# Alt_BRD_PowerModules.net
KiCad netlist of a schematic drawn in Altium Designer
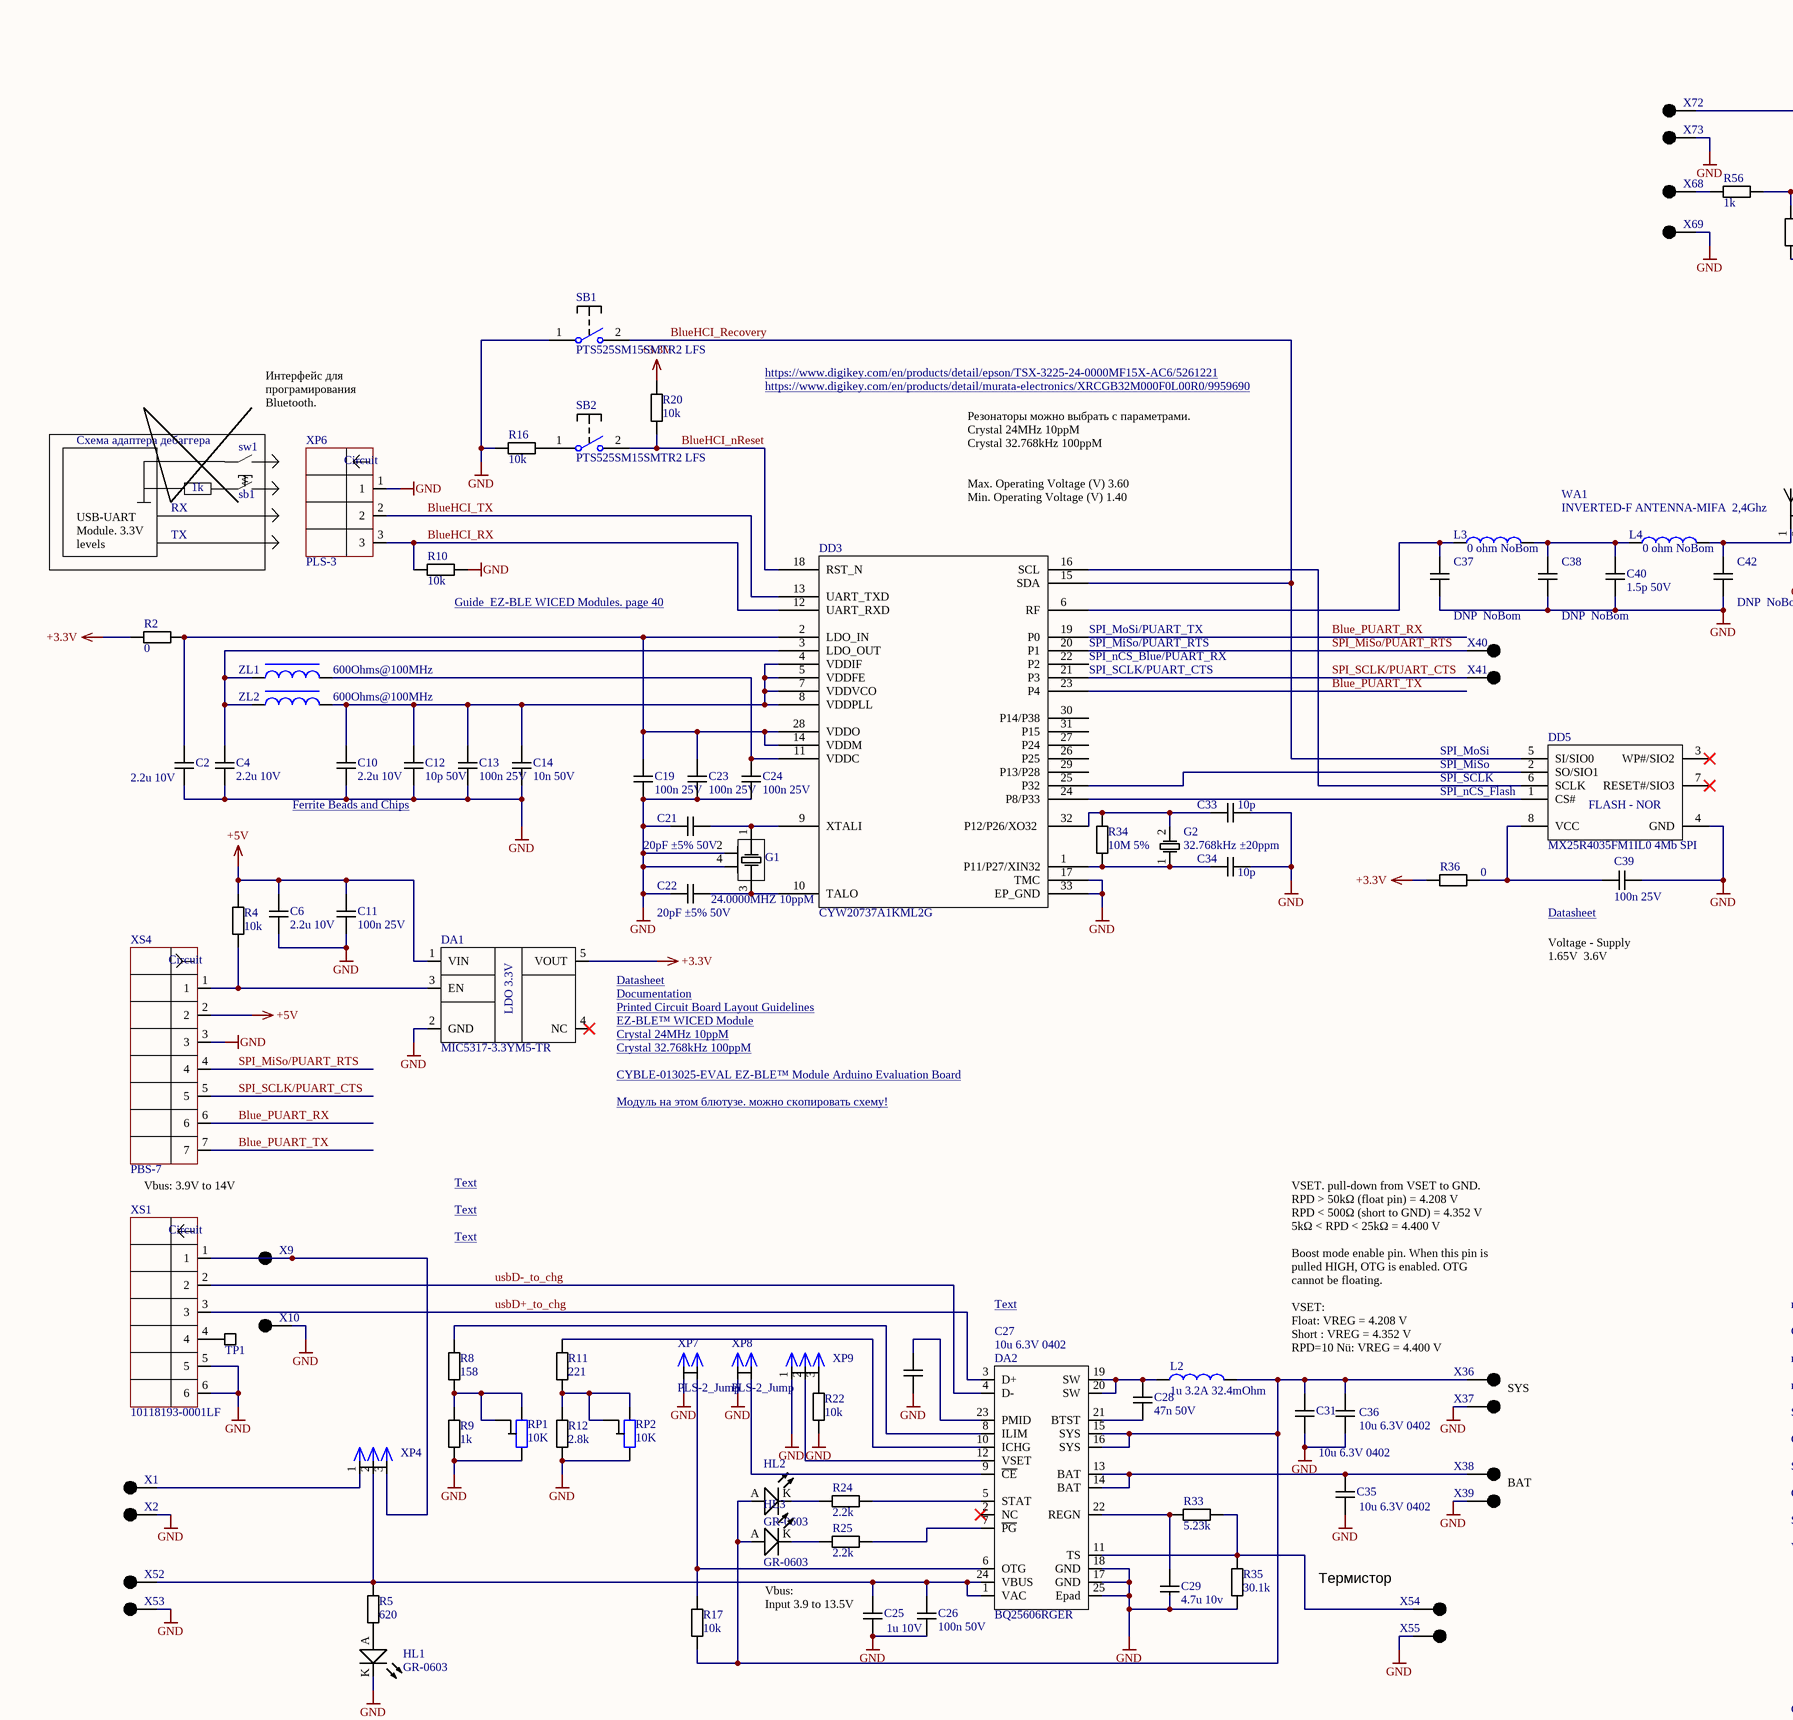
[diagram p0: Alt_BRD_PowerModules.SchDoc, top left]
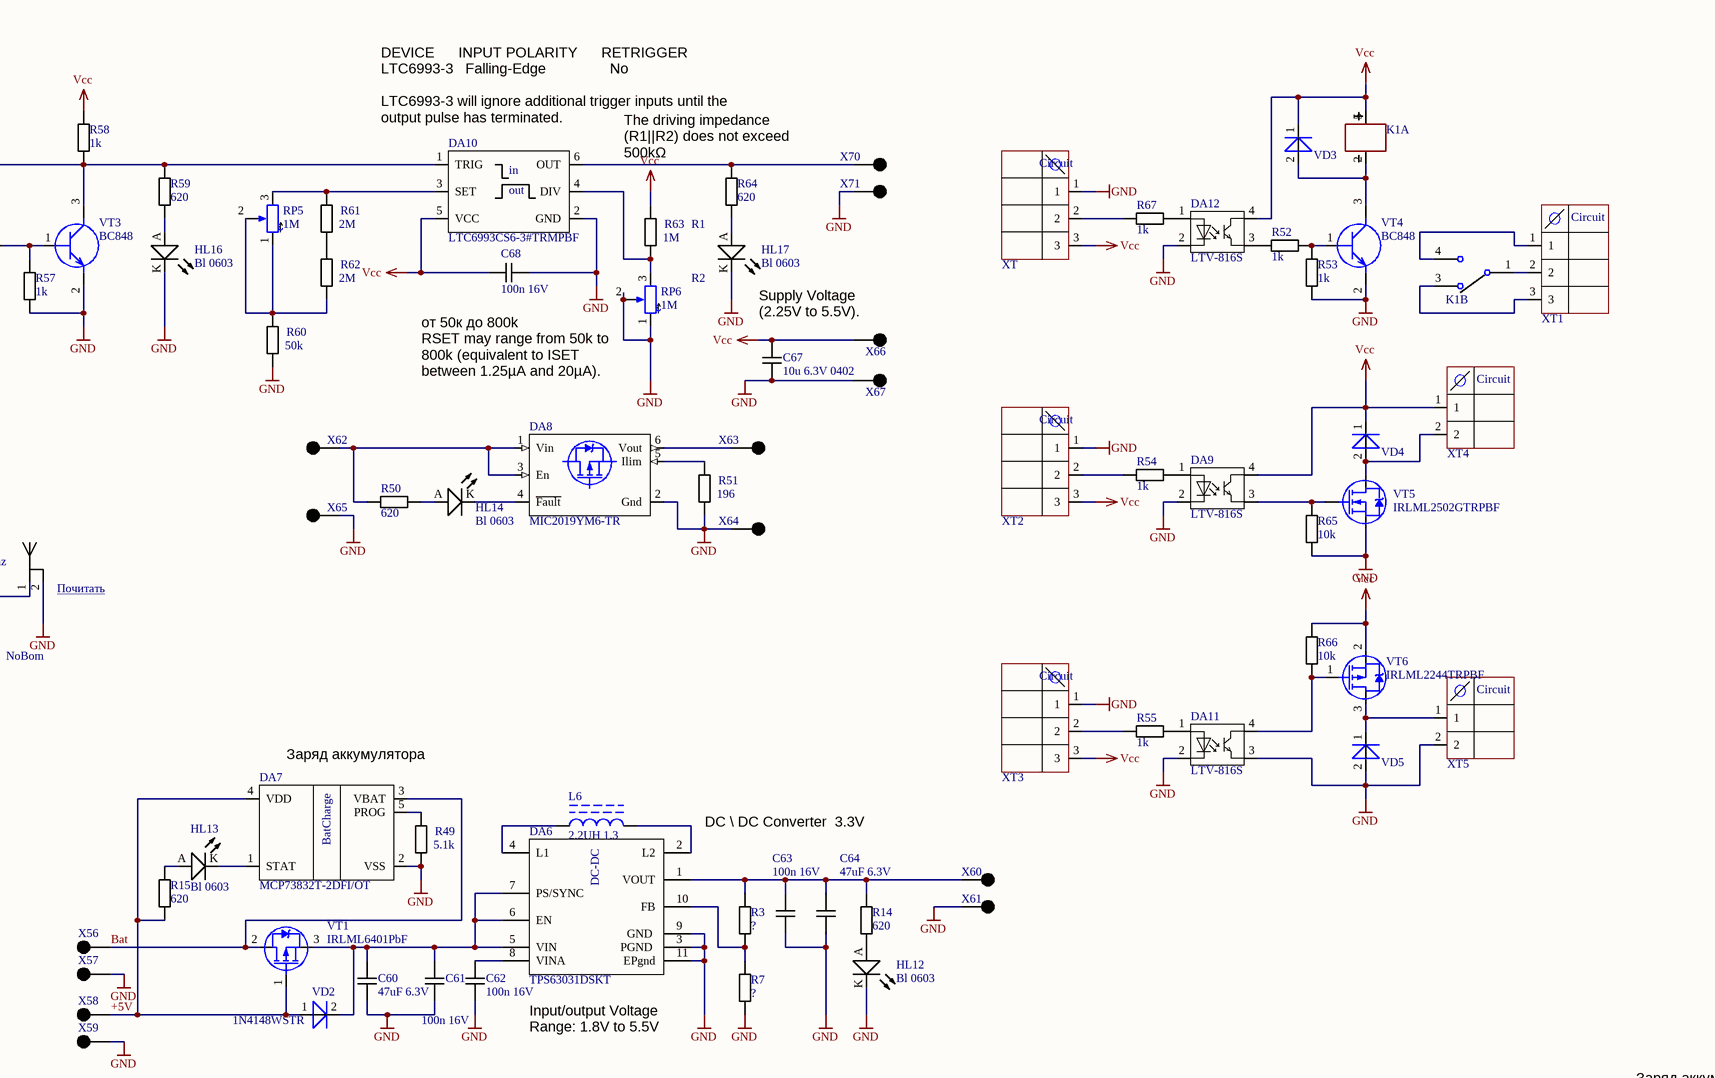
[diagram p1: Alt_BRD_PowerModules.SchDoc, top right]
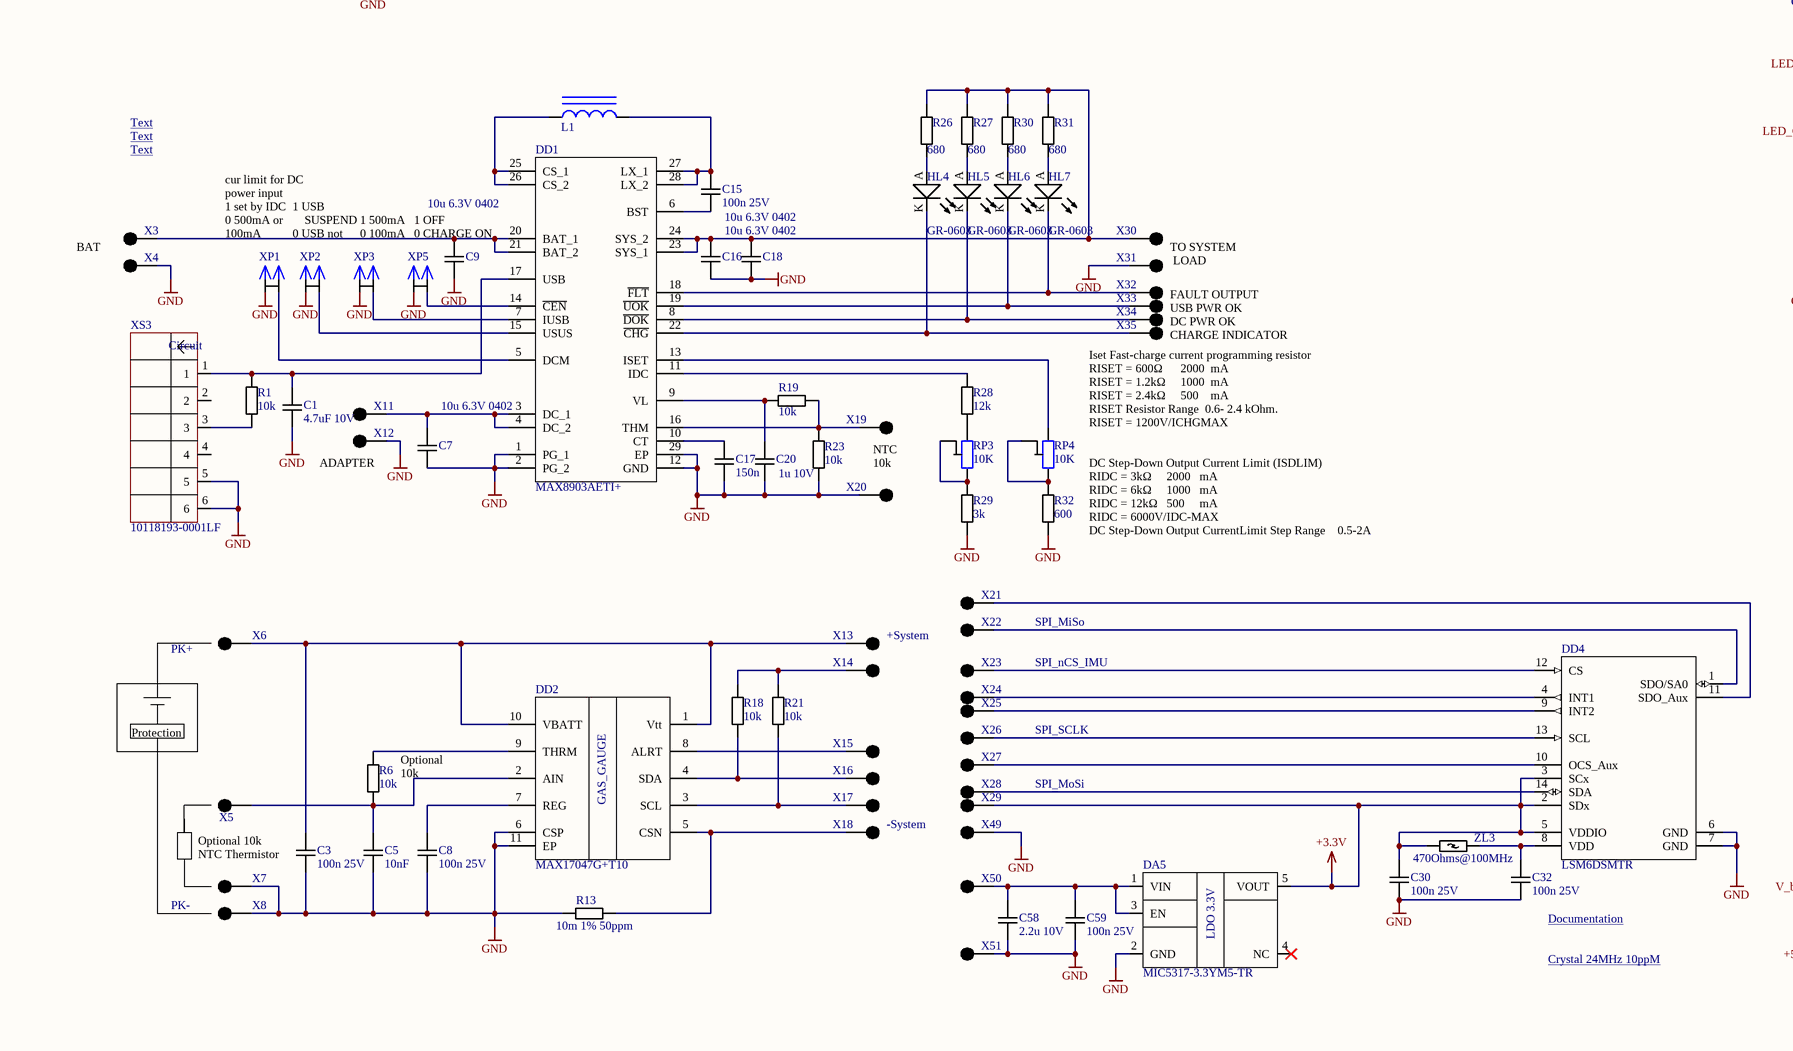
[diagram p2: Alt_BRD_PowerModules.SchDoc, bottom left]
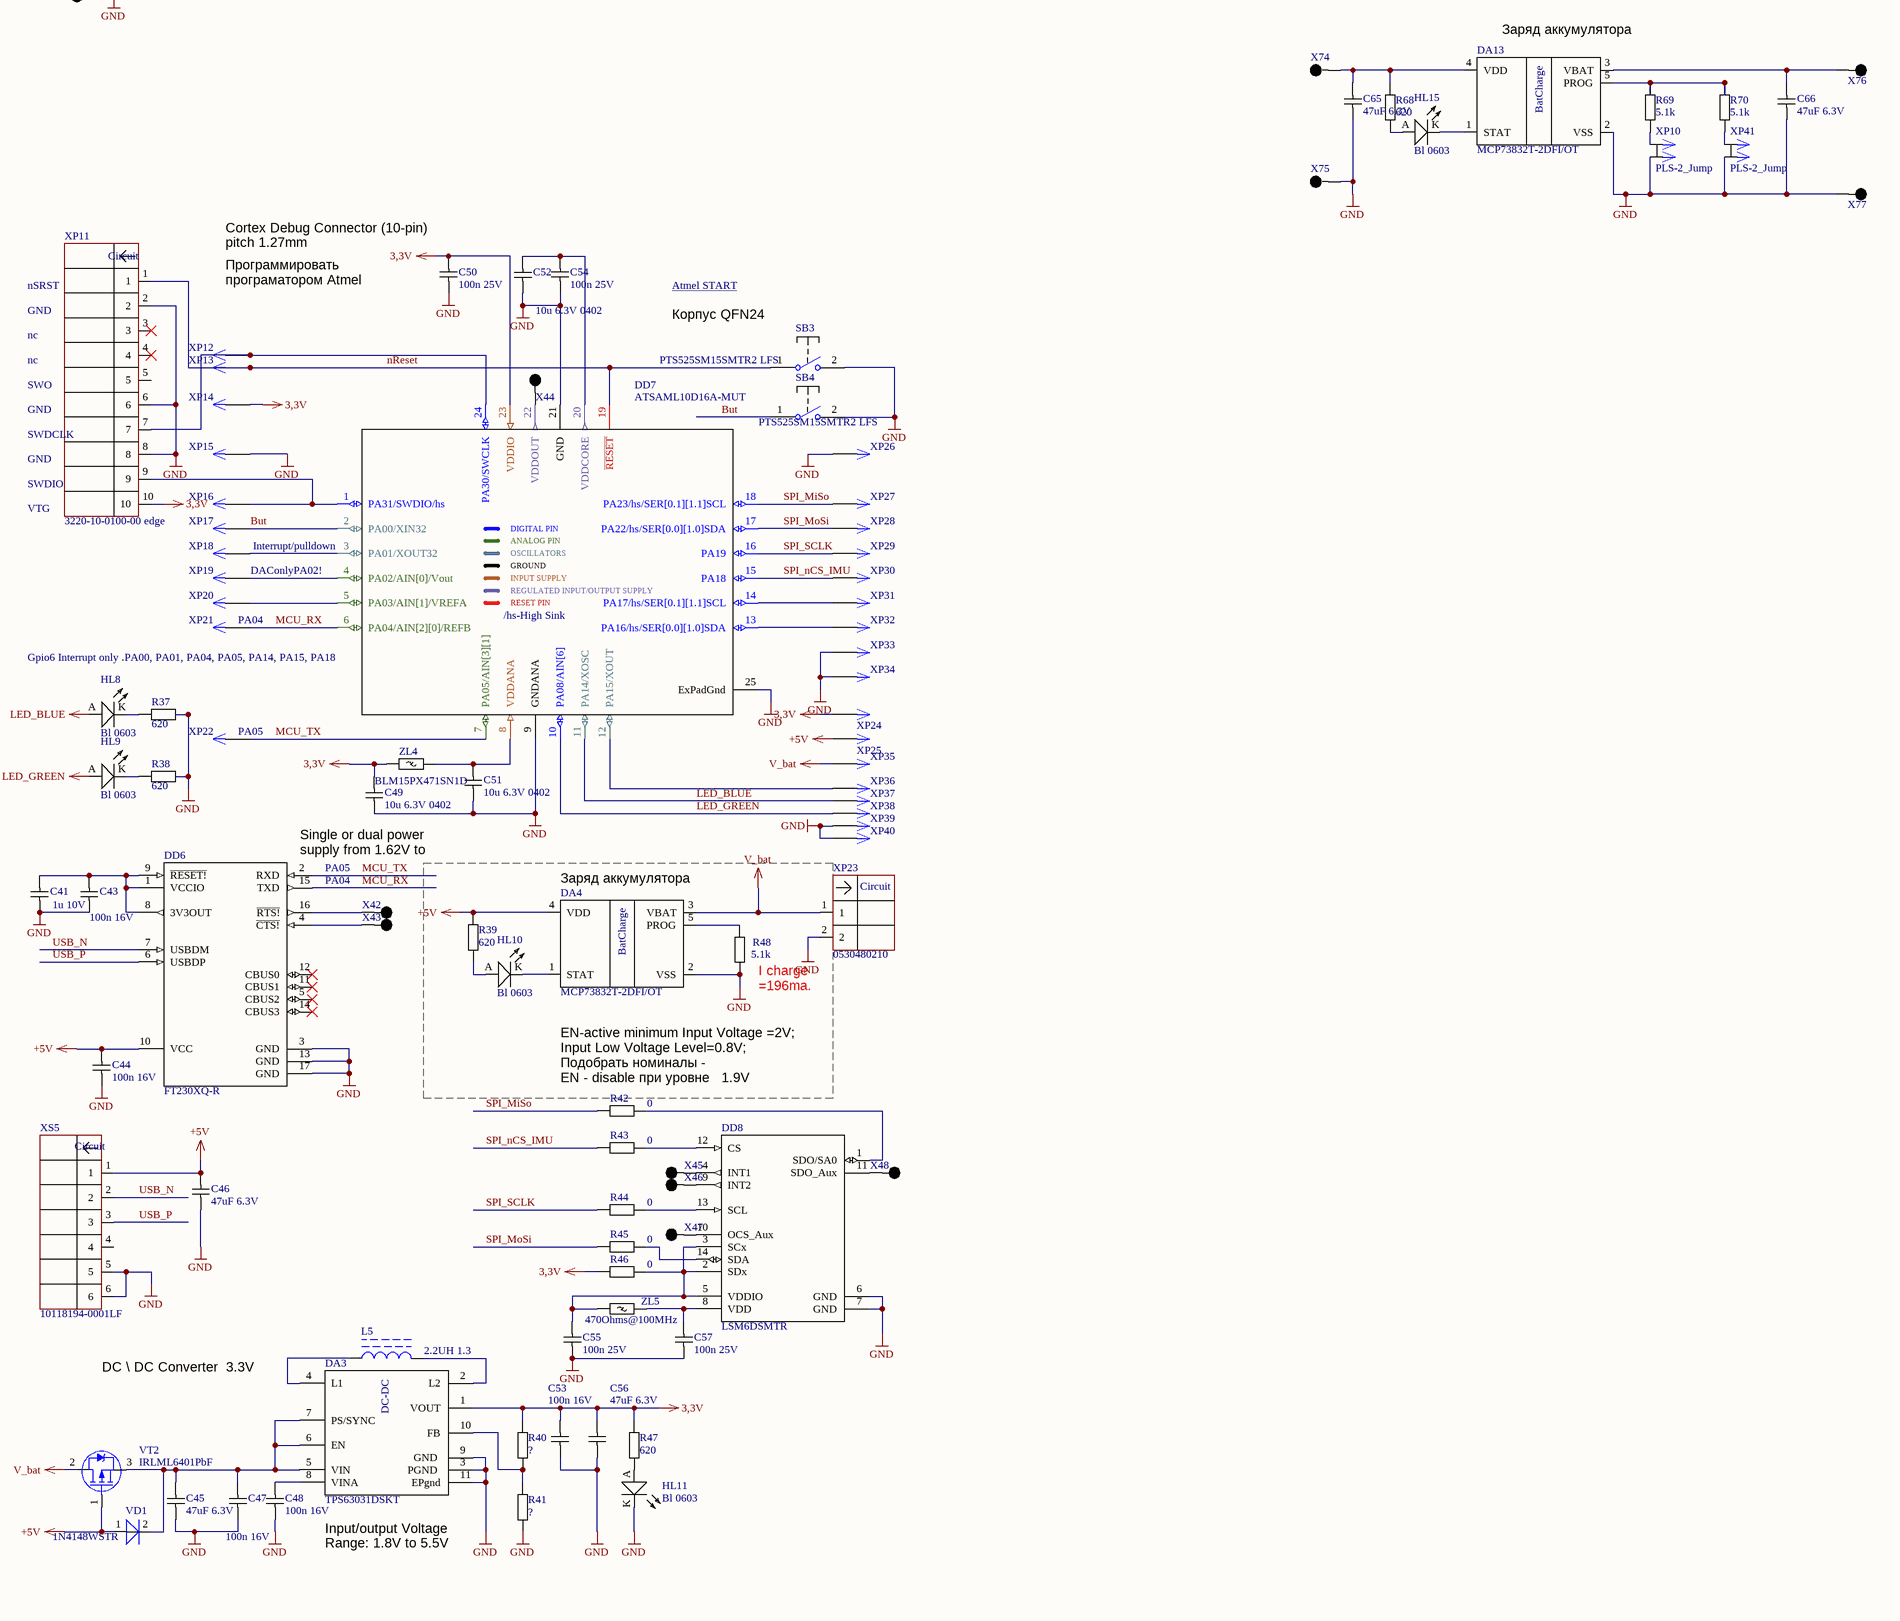
[diagram p3: Alt_BRD_PowerModules.SchDoc, bottom right]

(export (version "E")
  (design (tool "Eeschema 10.0.6"))
  (components
    (comp (ref "C1")
      (value "4.7uF 10V")
      (footprint "CapKemet1005(0402)")
      (description "CAP CER 4.7UF 10V X5R 0402")
      (fields
        (field (name "PART NUMBER") "GRM155R61A475MEAAD")
        (field (name "DIGI-KEY PART NUMBER") "490-14306-1-ND")
      )
      (libsource (lib "SssAccesDatbase") (part "Cap"))
    )
    (comp (ref "C2")
      (value "2.2u 10V")
      (footprint "CapKemet1005(0402)")
      (description "CAP CER 2.2uF 10V X5R 0402")
      (fields
        (field (name "PART NUMBER") "LMK105BJ225MV-F")
        (field (name "DIGI-KEY PART NUMBER") "587-3153-1-ND")
      )
      (libsource (lib "SssAccesDatbase") (part "Cap"))
    )
    (comp (ref "C3")
      (value "100n 25V")
      (footprint "CapKemet1005(0402)")
      (description "0.1µF ±10% 25V Ceramic Capacitor X7R 0402 (1005 Metric)")
      (fields
        (field (name "PART NUMBER") "04023C104KAT2A")
        (field (name "DIGI-KEY PART NUMBER") "478-7868-1-ND")
      )
      (libsource (lib "SssAccesDatbase") (part "Cap"))
    )
    (comp (ref "C4")
      (value "2.2u 10V")
      (footprint "CapKemet1005(0402)")
      (description "CAP CER 2.2uF 10V X5R 0402")
      (fields
        (field (name "PART NUMBER") "LMK105BJ225MV-F")
        (field (name "DIGI-KEY PART NUMBER") "587-3153-1-ND")
      )
      (libsource (lib "SssAccesDatbase") (part "Cap"))
    )
    (comp (ref "C5")
      (value "10nF")
      (footprint "CapKemet1005(0402)")
      (description "10nF 0402 50V X7R  +/-10%")
      (fields
        (field (name "PART NUMBER") "CC0402KRX7R9BB103")
        (field (name "MOUSER PART NUMBER") "603-CC402KRX7R9BB103")
      )
      (libsource (lib "SssAccesDatbase") (part "Cap"))
    )
    (comp (ref "C6")
      (value "2.2u 10V")
      (footprint "CapKemet1005(0402)")
      (description "CAP CER 2.2uF 10V X5R 0402")
      (fields
        (field (name "PART NUMBER") "LMK105BJ225MV-F")
        (field (name "DIGI-KEY PART NUMBER") "587-3153-1-ND")
      )
      (libsource (lib "SssAccesDatbase") (part "Cap"))
    )
    (comp (ref "C7")
      (value "10u 6.3V 0402")
      (footprint "CapKemet1005(0402)")
      (description "CAP CER 10UF 6.3V X5R 0402")
      (fields
        (field (name "PART NUMBER") "CAPC1005(0402)N")
        (field (name "DIGI-KEY PART NUMBER") "490-13211-1-ND")
      )
      (libsource (lib "SssAccesDatbase") (part "Cap"))
    )
    (comp (ref "C8")
      (value "100n 25V")
      (footprint "CapKemet1005(0402)")
      (description "0.1µF ±10% 25V Ceramic Capacitor X7R 0402 (1005 Metric)")
      (fields
        (field (name "PART NUMBER") "04023C104KAT2A")
        (field (name "DIGI-KEY PART NUMBER") "478-7868-1-ND")
      )
      (libsource (lib "SssAccesDatbase") (part "Cap"))
    )
    (comp (ref "C9")
      (value "10u 6.3V 0402")
      (footprint "CapKemet1005(0402)")
      (description "CAP CER 10UF 6.3V X5R 0402")
      (fields
        (field (name "PART NUMBER") "CAPC1005(0402)N")
        (field (name "DIGI-KEY PART NUMBER") "490-13211-1-ND")
      )
      (libsource (lib "SssAccesDatbase") (part "Cap"))
    )
    (comp (ref "C10")
      (value "2.2u 10V")
      (footprint "CapKemet1005(0402)")
      (description "CAP CER 2.2uF 10V X5R 0402")
      (fields
        (field (name "PART NUMBER") "LMK105BJ225MV-F")
        (field (name "DIGI-KEY PART NUMBER") "587-3153-1-ND")
      )
      (libsource (lib "SssAccesDatbase") (part "Cap"))
    )
    (comp (ref "C11")
      (value "100n 25V")
      (footprint "CapKemet1005(0402)")
      (description "CAP CER 0.1UF 25V X7R 0402")
      (fields
        (field (name "PART NUMBER") "CL05B104KA5NNNC")
        (field (name "DIGI-KEY PART NUMBER") "1276-6720-1-ND")
      )
      (libsource (lib "SssAccesDatbase") (part "Cap"))
    )
    (comp (ref "C12")
      (value "10p 50V")
      (footprint "CapKemet1005(0402)")
      (description "CAP CER 10PF 50V C0G/NP0 0402")
      (fields
        (field (name "PART NUMBER") "CL05C100DB5NNNC")
        (field (name "DIGI-KEY PART NUMBER") "1276-1625-1-ND")
      )
      (libsource (lib "SssAccesDatbase") (part "Cap"))
    )
    (comp (ref "C13")
      (value "100n 25V")
      (footprint "CapKemet1005(0402)")
      (description "CAP CER 0.1UF 25V X7R 0402")
      (fields
        (field (name "PART NUMBER") "CL05B104KA5NNNC")
        (field (name "DIGI-KEY PART NUMBER") "1276-6720-1-ND")
      )
      (libsource (lib "SssAccesDatbase") (part "Cap"))
    )
    (comp (ref "C14")
      (value "10n 50V")
      (footprint "CapKemet1005(0402)")
      (description "CAP CER 10000PF 50V X7R 0402")
      (fields
        (field (name "PART NUMBER") "CL05B103KB5NNNC")
        (field (name "DIGI-KEY PART NUMBER") "1276-1028-1-ND")
      )
      (libsource (lib "SssAccesDatbase") (part "Cap"))
    )
    (comp (ref "C15")
      (value "100n 25V")
      (footprint "CapKemet1005(0402)")
      (description "0.1µF ±10% 25V Ceramic Capacitor X7R 0402 (1005 Metric)")
      (fields
        (field (name "PART NUMBER") "04023C104KAT2A")
        (field (name "DIGI-KEY PART NUMBER") "478-7868-1-ND")
      )
      (libsource (lib "SssAccesDatbase") (part "Cap"))
    )
    (comp (ref "C16")
      (value "10u 6.3V 0402")
      (footprint "CapKemet1005(0402)")
      (description "CAP CER 10UF 6.3V X5R 0402")
      (fields
        (field (name "PART NUMBER") "CAPC1005(0402)N")
        (field (name "DIGI-KEY PART NUMBER") "490-13211-1-ND")
      )
      (libsource (lib "SssAccesDatbase") (part "Cap"))
    )
    (comp (ref "C17")
      (value "150n")
      (footprint "CapKemet1005(0402)")
      (fields (field (name "PART NUMBER") "CAPC1005(0402)N"))
      (libsource (lib "SssAccesDatbase") (part "Cap"))
    )
    (comp (ref "C18")
      (value "10u 6.3V 0402")
      (footprint "CapKemet1005(0402)")
      (description "CAP CER 10UF 6.3V X5R 0402")
      (fields
        (field (name "PART NUMBER") "CAPC1005(0402)N")
        (field (name "DIGI-KEY PART NUMBER") "490-13211-1-ND")
      )
      (libsource (lib "SssAccesDatbase") (part "Cap"))
    )
    (comp (ref "C19")
      (value "100n 25V")
      (footprint "CapKemet1005(0402)")
      (description "CAP CER 0.1UF 25V X7R 0402")
      (fields
        (field (name "PART NUMBER") "CL05B104KA5NNNC")
        (field (name "DIGI-KEY PART NUMBER") "1276-6720-1-ND")
      )
      (libsource (lib "SssAccesDatbase") (part "Cap"))
    )
    (comp (ref "C20")
      (value "1u 10V")
      (footprint "CapKemet1005(0402)")
      (description "CAP CER 1UF 10V 10% X6S 0402")
      (fields
        (field (name "PART NUMBER") "CAPC1005(0402)N")
        (field (name "MANUFACTURER PART NUMBER") "LMK105BJ105KPLF")
      )
      (libsource (lib "") (part "Cap_1"))
    )
    (comp (ref "C21")
      (value "20pF ±5% 50V")
      (footprint "CapKemet1005(0402)")
      (description "20pF ±5% 50V Ceramic Capacitor C0G, NP0 0402 (1005 Metric)")
      (fields
        (field (name "PART NUMBER") "CC0402JRNPO9BN200")
        (field (name "DIGI-KEY PART NUMBER") "311-1417-1-ND")
      )
      (libsource (lib "SssAccesDatbase") (part "Cap"))
    )
    (comp (ref "C22")
      (value "20pF ±5% 50V")
      (footprint "CapKemet1005(0402)")
      (description "20pF ±5% 50V Ceramic Capacitor C0G, NP0 0402 (1005 Metric)")
      (fields
        (field (name "PART NUMBER") "CC0402JRNPO9BN200")
        (field (name "DIGI-KEY PART NUMBER") "311-1417-1-ND")
      )
      (libsource (lib "SssAccesDatbase") (part "Cap"))
    )
    (comp (ref "C23")
      (value "100n 25V")
      (footprint "CapKemet1005(0402)")
      (description "CAP CER 0.1UF 25V X7R 0402")
      (fields
        (field (name "PART NUMBER") "CL05B104KA5NNNC")
        (field (name "DIGI-KEY PART NUMBER") "1276-6720-1-ND")
      )
      (libsource (lib "SssAccesDatbase") (part "Cap"))
    )
    (comp (ref "C24")
      (value "100n 25V")
      (footprint "CapKemet1005(0402)")
      (description "CAP CER 0.1UF 25V X7R 0402")
      (fields
        (field (name "PART NUMBER") "CL05B104KA5NNNC")
        (field (name "DIGI-KEY PART NUMBER") "1276-6720-1-ND")
      )
      (libsource (lib "SssAccesDatbase") (part "Cap"))
    )
    (comp (ref "C25")
      (value "1u 10V")
      (footprint "CapKemet1005(0402)")
      (description "CAP CER 1UF 10V 10% X6S 0402")
      (fields
        (field (name "PART NUMBER") "CAPC1005(0402)N")
        (field (name "DIGI-KEY PART NUMBER") "1276-6805-1-ND")
      )
      (libsource (lib "") (part "Cap_1"))
    )
    (comp (ref "C26")
      (value "100n 50V")
      (footprint "CapKemet1005(0402)")
      (description "CAP CER 0.1UF 25V X5R 0402")
      (fields
        (field (name "PART NUMBER") "CAPC1005(0402)N")
        (field (name "DIGI-KEY PART NUMBER") "732-7495-1-ND")
      )
      (libsource (lib "") (part "Cap_1"))
    )
    (comp (ref "C27")
      (value "10u 6.3V 0402")
      (footprint "CapKemet1005(0402)")
      (description "CAP CER 10UF 6.3V X5R 0402")
      (fields
        (field (name "PART NUMBER") "CAPC1005(0402)N")
        (field (name "DIGI-KEY PART NUMBER") "490-13211-1-ND")
      )
      (libsource (lib "SssAccesDatbase") (part "Cap"))
    )
    (comp (ref "C28")
      (value "47n 50V")
      (footprint "CapKemet1005(0402)")
      (description "CAP CER 0.047UF 50V X7R 0402")
      (fields
        (field (name "PART NUMBER") "CAPC1005(0402)N")
        (field (name "DIGI-KEY PART NUMBER") "490-13297-1-ND")
      )
      (libsource (lib "") (part "Cap_1"))
    )
    (comp (ref "C29")
      (value "4.7u 10v")
      (footprint "CapKemet1005(0402)")
      (description "CAP CER 4.7UF ±20% 10V X5R 0402")
      (fields
        (field (name "PART NUMBER") "CAPC1005(0402)N")
        (field (name "DIGI-KEY PART NUMBER") "490-14306-1-ND")
      )
      (libsource (lib "") (part "Cap_1"))
    )
    (comp (ref "C30")
      (value "100n 25V")
      (footprint "CapKemet1005(0402)")
      (description "CAP CER 0.1UF 25V X7R 0402")
      (fields
        (field (name "PART NUMBER") "CL05B104KA5NNNC")
        (field (name "DIGI-KEY PART NUMBER") "1276-6720-1-ND")
      )
      (libsource (lib "SssAccesDatbase") (part "Cap"))
    )
    (comp (ref "C31")
      (value "10u 6.3V 0402")
      (footprint "CapKemet1005(0402)")
      (description "CAP CER 10UF 6.3V X5R 0402")
      (fields
        (field (name "PART NUMBER") "CAPC1005(0402)N")
        (field (name "DIGI-KEY PART NUMBER") "490-13211-1-ND")
      )
      (libsource (lib "SssAccesDatbase") (part "Cap"))
    )
    (comp (ref "C32")
      (value "100n 25V")
      (footprint "CapKemet1005(0402)")
      (description "CAP CER 0.1UF 25V X7R 0402")
      (fields
        (field (name "PART NUMBER") "CL05B104KA5NNNC")
        (field (name "DIGI-KEY PART NUMBER") "1276-6720-1-ND")
      )
      (libsource (lib "SssAccesDatbase") (part "Cap"))
    )
    (comp (ref "C33")
      (value "10p")
      (footprint "CapKemet1005(0402)")
      (description "10pF 0402 50V C0G  +/-0.5pF")
      (fields
        (field (name "PART NUMBER") "CC0402DRNPO9BN100")
        (field (name "MOUSER PART NUMBER") "603-CC402DRNPO9BN100")
      )
      (libsource (lib "SssAccesDatbase") (part "Cap"))
    )
    (comp (ref "C34")
      (value "10p")
      (footprint "CapKemet1005(0402)")
      (description "10pF 0402 50V C0G  +/-0.5pF")
      (fields
        (field (name "PART NUMBER") "CC0402DRNPO9BN100")
        (field (name "MOUSER PART NUMBER") "603-CC402DRNPO9BN100")
      )
      (libsource (lib "SssAccesDatbase") (part "Cap"))
    )
    (comp (ref "C35")
      (value "10u 6.3V 0402")
      (footprint "CapKemet1005(0402)")
      (description "CAP CER 10UF 6.3V X5R 0402")
      (fields
        (field (name "PART NUMBER") "CAPC1005(0402)N")
        (field (name "DIGI-KEY PART NUMBER") "490-13211-1-ND")
      )
      (libsource (lib "SssAccesDatbase") (part "Cap"))
    )
    (comp (ref "C36")
      (value "10u 6.3V 0402")
      (footprint "CapKemet1005(0402)")
      (description "CAP CER 10UF 6.3V X5R 0402")
      (fields
        (field (name "PART NUMBER") "CAPC1005(0402)N")
        (field (name "DIGI-KEY PART NUMBER") "490-13211-1-ND")
      )
      (libsource (lib "SssAccesDatbase") (part "Cap"))
    )
    (comp (ref "C37")
      (value "DNP  NoBom")
      (footprint "CapKemet1005(0402)")
      (description "150pF 0402 50V NP0  +/-5%")
      (fields
        (field (name "PART NUMBER") "GCM1555C1H151JA16D")
        (field (name "MOUSER PART NUMBER") "81-GCM1555C1H151J16D")
      )
      (libsource (lib "SssAccesDatbase") (part "Cap"))
    )
    (comp (ref "C38")
      (value "DNP  NoBom")
      (footprint "CapKemet1005(0402)")
      (description "150pF 0402 50V NP0  +/-5%")
      (fields
        (field (name "PART NUMBER") "GCM1555C1H151JA16D")
        (field (name "MOUSER PART NUMBER") "81-GCM1555C1H151J16D")
      )
      (libsource (lib "SssAccesDatbase") (part "Cap"))
    )
    (comp (ref "C39")
      (value "100n 25V")
      (footprint "CapKemet1005(0402)")
      (description "CAP CER 0.1UF 25V X7R 0402")
      (fields
        (field (name "PART NUMBER") "CL05B104KA5NNNC")
        (field (name "DIGI-KEY PART NUMBER") "1276-6720-1-ND")
      )
      (libsource (lib "SssAccesDatbase") (part "Cap"))
    )
    (comp (ref "C40")
      (value "1.5p 50V")
      (footprint "CapKemet1005(0402)")
      (description "CAP CER 1.5pF 50V COG 0402 ±0.1pF")
      (fields
        (field (name "PART NUMBER") "CL05C1R5BB5NNNC")
        (field (name "DIGI-KEY PART NUMBER") "1276-1656-1-ND")
      )
      (libsource (lib "SssAccesDatbase") (part "Cap"))
    )
    (comp (ref "C41")
      (value "1u 10V")
      (footprint "CapKemet1005(0402)")
      (description "CAP CER 1UF 10V 10% X6S 0402")
      (fields
        (field (name "PART NUMBER") "CAPC1005(0402)N")
        (field (name "MANUFACTURER PART NUMBER") "LMK105BJ105KPLF")
      )
      (libsource (lib "") (part "Cap_1"))
    )
    (comp (ref "C42")
      (value "DNP  NoBom")
      (footprint "CapKemet1005(0402)")
      (description "150pF 0402 50V NP0  +/-5%")
      (fields
        (field (name "PART NUMBER") "GCM1555C1H151JA16D")
        (field (name "MOUSER PART NUMBER") "81-GCM1555C1H151J16D")
      )
      (libsource (lib "SssAccesDatbase") (part "Cap"))
    )
    (comp (ref "C43")
      (value "100n 16V")
      (footprint "CapKemet1005(0402)")
      (description "Cap Cer 0.1uF 16V 1% C0G(NP0) MLCC")
      (fields
        (field (name "PART NUMBER") "CL05F104ZO5NNNC")
        (field (name "DIGI-KEY PART NUMBER") "1276-1004-1-ND")
      )
      (libsource (lib "SssAccesDatbase") (part "Cap"))
    )
    (comp (ref "C44")
      (value "100n 16V")
      (footprint "CapKemet1005(0402)")
      (description "Cap Cer 0.1uF 16V 1% C0G(NP0) MLCC")
      (fields
        (field (name "PART NUMBER") "CL05F104ZO5NNNC")
        (field (name "DIGI-KEY PART NUMBER") "1276-1004-1-ND")
      )
      (libsource (lib "SssAccesDatbase") (part "Cap"))
    )
    (comp (ref "C45")
      (value "47uF 6.3V")
      (footprint "CapKemet1005(0402)")
      (description "CAP CER 47UF 6.3V X5R 0603")
      (fields
        (field (name "PART NUMBER") "GRM188R60J476ME15D")
        (field (name "DIGI-KEY PART NUMBER") "490-13247-1-ND")
      )
      (libsource (lib "SssAccesDatbase") (part "Cap"))
    )
    (comp (ref "C46")
      (value "47uF 6.3V")
      (footprint "CapKemet1005(0402)")
      (description "CAP CER 47UF 6.3V X5R 0603")
      (fields
        (field (name "PART NUMBER") "GRM188R60J476ME15D")
        (field (name "DIGI-KEY PART NUMBER") "490-13247-1-ND")
      )
      (libsource (lib "SssAccesDatbase") (part "Cap"))
    )
    (comp (ref "C47")
      (value "100n 16V")
      (footprint "CapKemet1005(0402)")
      (description "Cap Cer 0.1uF 16V 1% C0G(NP0) MLCC")
      (fields
        (field (name "PART NUMBER") "CL05F104ZO5NNNC")
        (field (name "DIGI-KEY PART NUMBER") "1276-1004-1-ND")
      )
      (libsource (lib "SssAccesDatbase") (part "Cap"))
    )
    (comp (ref "C48")
      (value "100n 16V")
      (footprint "CapKemet1005(0402)")
      (description "Cap Cer 0.1uF 16V 1% C0G(NP0) MLCC")
      (fields
        (field (name "PART NUMBER") "CL05F104ZO5NNNC")
        (field (name "DIGI-KEY PART NUMBER") "1276-1004-1-ND")
      )
      (libsource (lib "SssAccesDatbase") (part "Cap"))
    )
    (comp (ref "C49")
      (value "10u 6.3V 0402")
      (footprint "CapKemet1005(0402)")
      (description "CAP CER 10UF 6.3V X5R 0402")
      (fields
        (field (name "PART NUMBER") "CAPC1608(0603)")
        (field (name "DIGI-KEY PART NUMBER") "GRJ155R60J106ME11D")
      )
      (libsource (lib "SssAccesDatbase") (part "Cap"))
    )
    (comp (ref "C50")
      (value "100n 25V")
      (footprint "CapKemet1005(0402)")
      (description "CAP CER 0.1UF 25V X5R 0402")
      (fields
        (field (name "PART NUMBER") "CAPC1608(0603)")
        (field (name "DIGI-KEY PART NUMBER") "732-7495-1-ND")
      )
      (libsource (lib "") (part "Cap_1"))
    )
    (comp (ref "C51")
      (value "10u 6.3V 0402")
      (footprint "CapKemet1005(0402)")
      (description "CAP CER 10UF 6.3V X5R 0402")
      (fields
        (field (name "PART NUMBER") "CAPC1608(0603)")
        (field (name "DIGI-KEY PART NUMBER") "GRJ155R60J106ME11D")
      )
      (libsource (lib "SssAccesDatbase") (part "Cap"))
    )
    (comp (ref "C52")
      (value "10u 6.3V 0402")
      (footprint "CapKemet1005(0402)")
      (description "CAP CER 10UF 6.3V X5R 0402")
      (fields
        (field (name "PART NUMBER") "CAPC1608(0603)")
        (field (name "DIGI-KEY PART NUMBER") "GRJ155R60J106ME11D")
      )
      (libsource (lib "SssAccesDatbase") (part "Cap"))
    )
    (comp (ref "C53")
      (value "100n 16V")
      (footprint "CapKemet1005(0402)")
      (description "Cap Cer 0.1uF 16V 1% C0G(NP0) MLCC")
      (fields
        (field (name "PART NUMBER") "CL05F104ZO5NNNC")
        (field (name "DIGI-KEY PART NUMBER") "1276-1004-1-ND")
      )
      (libsource (lib "SssAccesDatbase") (part "Cap"))
    )
    (comp (ref "C54")
      (value "100n 25V")
      (footprint "CapKemet1005(0402)")
      (description "CAP CER 0.1UF 25V X5R 0402")
      (fields
        (field (name "PART NUMBER") "CAPC1608(0603)")
        (field (name "DIGI-KEY PART NUMBER") "732-7495-1-ND")
      )
      (libsource (lib "") (part "Cap_1"))
    )
    (comp (ref "C55")
      (value "100n 25V")
      (footprint "CapKemet1005(0402)")
      (description "CAP CER 0.1UF 25V X7R 0402")
      (fields
        (field (name "PART NUMBER") "CL05B104KA5NNNC")
        (field (name "DIGI-KEY PART NUMBER") "1276-6720-1-ND")
      )
      (libsource (lib "SssAccesDatbase") (part "Cap"))
    )
    (comp (ref "C56")
      (value "47uF 6.3V")
      (footprint "CapKemet1005(0402)")
      (description "CAP CER 47UF 6.3V X5R 0603")
      (fields
        (field (name "PART NUMBER") "GRM188R60J476ME15D")
        (field (name "DIGI-KEY PART NUMBER") "490-13247-1-ND")
      )
      (libsource (lib "SssAccesDatbase") (part "Cap"))
    )
    (comp (ref "C57")
      (value "100n 25V")
      (footprint "CapKemet1005(0402)")
      (description "CAP CER 0.1UF 25V X7R 0402")
      (fields
        (field (name "PART NUMBER") "CL05B104KA5NNNC")
        (field (name "DIGI-KEY PART NUMBER") "1276-6720-1-ND")
      )
      (libsource (lib "SssAccesDatbase") (part "Cap"))
    )
    (comp (ref "C58")
      (value "2.2u 10V")
      (footprint "CapKemet1005(0402)")
      (description "CAP CER 2.2uF 10V X5R 0402")
      (fields
        (field (name "PART NUMBER") "LMK105BJ225MV-F")
        (field (name "DIGI-KEY PART NUMBER") "587-3153-1-ND")
      )
      (libsource (lib "SssAccesDatbase") (part "Cap"))
    )
    (comp (ref "C59")
      (value "100n 25V")
      (footprint "CapKemet1005(0402)")
      (description "CAP CER 0.1UF 25V X7R 0402")
      (fields
        (field (name "PART NUMBER") "CL05B104KA5NNNC")
        (field (name "DIGI-KEY PART NUMBER") "1276-6720-1-ND")
      )
      (libsource (lib "SssAccesDatbase") (part "Cap"))
    )
    (comp (ref "C60")
      (value "47uF 6.3V")
      (footprint "CapKemet1005(0402)")
      (description "CAP CER 47UF 6.3V X5R 0603")
      (fields
        (field (name "PART NUMBER") "GRM188R60J476ME15D")
        (field (name "DIGI-KEY PART NUMBER") "490-13247-1-ND")
      )
      (libsource (lib "SssAccesDatbase") (part "Cap"))
    )
    (comp (ref "C61")
      (value "100n 16V")
      (footprint "CapKemet1005(0402)")
      (description "Cap Cer 0.1uF 16V 1% C0G(NP0) MLCC")
      (fields
        (field (name "PART NUMBER") "CL05F104ZO5NNNC")
        (field (name "DIGI-KEY PART NUMBER") "1276-1004-1-ND")
      )
      (libsource (lib "SssAccesDatbase") (part "Cap"))
    )
    (comp (ref "C62")
      (value "100n 16V")
      (footprint "CapKemet1005(0402)")
      (description "Cap Cer 0.1uF 16V 1% C0G(NP0) MLCC")
      (fields
        (field (name "PART NUMBER") "CL05F104ZO5NNNC")
        (field (name "DIGI-KEY PART NUMBER") "1276-1004-1-ND")
      )
      (libsource (lib "SssAccesDatbase") (part "Cap"))
    )
    (comp (ref "C63")
      (value "100n 16V")
      (footprint "CapKemet1005(0402)")
      (description "Cap Cer 0.1uF 16V 1% C0G(NP0) MLCC")
      (fields
        (field (name "PART NUMBER") "CL05F104ZO5NNNC")
        (field (name "DIGI-KEY PART NUMBER") "1276-1004-1-ND")
      )
      (libsource (lib "SssAccesDatbase") (part "Cap"))
    )
    (comp (ref "C64")
      (value "47uF 6.3V")
      (footprint "CapKemet1005(0402)")
      (description "CAP CER 47UF 6.3V X5R 0603")
      (fields
        (field (name "PART NUMBER") "GRM188R60J476ME15D")
        (field (name "DIGI-KEY PART NUMBER") "490-13247-1-ND")
      )
      (libsource (lib "SssAccesDatbase") (part "Cap"))
    )
    (comp (ref "C65")
      (value "47uF 6.3V")
      (footprint "CapKemet1005(0402)")
      (description "CAP CER 47UF 6.3V X5R 0603")
      (fields
        (field (name "PART NUMBER") "GRM188R60J476ME15D")
        (field (name "DIGI-KEY PART NUMBER") "490-13247-1-ND")
      )
      (libsource (lib "SssAccesDatbase") (part "Cap"))
    )
    (comp (ref "C66")
      (value "47uF 6.3V")
      (footprint "CapKemet1005(0402)")
      (description "CAP CER 47UF 6.3V X5R 0603")
      (fields
        (field (name "PART NUMBER") "GRM188R60J476ME15D")
        (field (name "DIGI-KEY PART NUMBER") "490-13247-1-ND")
      )
      (libsource (lib "SssAccesDatbase") (part "Cap"))
    )
    (comp (ref "C67")
      (value "10u 6.3V 0402")
      (footprint "CapKemet1005(0402)")
      (description "CAP CER 10UF 6.3V X5R 0402")
      (fields
        (field (name "PART NUMBER") "CAPC1608(0603)")
        (field (name "DIGI-KEY PART NUMBER") "GRJ155R60J106ME11D")
      )
      (libsource (lib "SssAccesDatbase") (part "Cap"))
    )
    (comp (ref "C68")
      (value "100n 16V")
      (footprint "CapKemet1005(0402)")
      (description "Cap Cer 0.1uF 16V 1% C0G(NP0) MLCC")
      (fields
        (field (name "PART NUMBER") "CL05F104ZO5NNNC")
        (field (name "DIGI-KEY PART NUMBER") "1276-1004-1-ND")
      )
      (libsource (lib "SssAccesDatbase") (part "Cap"))
    )
    (comp (ref "DA1")
      (value "MIC5317-3.3YM5-TR")
      (footprint "SOT-23-OT5_N")
      (description "Linear Voltage Regulator IC 1 Output 150mA SOT-23-5")
      (fields (field (name "DIGI-KEY PART NUMBER") "MIC5317-3.3YM5-CT-ND"))
      (libsource (lib "SssAccesDatbase") (part "MIC5317-3.3YM5-TR"))
    )
    (comp (ref "DA2")
      (value "BQ25606RGER")
      (footprint "VQFN-24")
      (description "IC BATT CHG LI-ION 1 CELL 24VQFN")
      (fields (field (name "DIGI-KEY PART NUMBER") "296-47743-1-ND"))
      (libsource (lib "SssAccesDatbase") (part "BQ25606RGER"))
    )
    (comp (ref "DA3")
      (value "TPS63031DSKT")
      (footprint "WSON-10")
      (description "IC REG BCK BST 3.3V 900MA 10SON")
      (fields (field (name "DIGI-KEY PART NUMBER") "296-23904-1-ND"))
      (libsource (lib "SssAccesDatbase") (part "TPS63031DSKR"))
    )
    (comp (ref "DA4")
      (value "MCP73832T-2DFI/OT")
      (footprint "SOT-23-5")
      (description "IC LI-ION/LI-POLY CTRLR SOT23-5")
      (fields (field (name "DIGI-KEY PART NUMBER") "MCP73832T-2DFI/OTCT-ND"))
      (libsource (lib "SssAccesDatbase") (part "MCP73832T-2DFI/OT"))
    )
    (comp (ref "DA5")
      (value "MIC5317-3.3YM5-TR")
      (footprint "SOT-23-OT5_N")
      (description "Linear Voltage Regulator IC 1 Output 150mA SOT-23-5")
      (fields (field (name "DIGI-KEY PART NUMBER") "MIC5317-3.3YM5-CT-ND"))
      (libsource (lib "SssAccesDatbase") (part "MIC5317-3.3YM5-TR"))
    )
    (comp (ref "DA6")
      (value "TPS63031DSKT")
      (footprint "WSON-10")
      (description "IC REG BCK BST 3.3V 900MA 10SON")
      (fields (field (name "DIGI-KEY PART NUMBER") "296-23904-1-ND"))
      (libsource (lib "SssAccesDatbase") (part "TPS63031DSKR"))
    )
    (comp (ref "DA7")
      (value "MCP73832T-2DFI/OT")
      (footprint "SOT-23-5")
      (description "IC LI-ION/LI-POLY CTRLR SOT23-5")
      (fields (field (name "DIGI-KEY PART NUMBER") "MCP73832T-2DFI/OTCT-ND"))
      (libsource (lib "SssAccesDatbase") (part "MCP73832T-2DFI/OT"))
    )
    (comp (ref "DA8")
      (value "MIC2019YM6-TR")
      (footprint "SOT23-6")
      (description "IC DISTRIBUTION SW ADJ SOT23-6")
      (fields (field (name "DIGI-KEY PART NUMBER") "576-2595-1-ND"))
      (libsource (lib "SssAccesDatbase") (part "MIC2019YM6-TR"))
    )
    (comp (ref "DA9")
      (value "LTV-816S")
      (footprint "LTV-816S")
      (description "OPTOISOLATR 5KV TRANSISTOR 4-SMD")
      (fields (field (name "DIGI-KEY PART NUMBER") "160-1361-5-ND"))
      (libsource (lib "SssAccesDatbase") (part "TCMT1103"))
    )
    (comp (ref "DA10")
      (value "LTC6993CS6-3#TRMPBF")
      (footprint "SOT23-6")
      (description "IC MONO MULTIVIBRATOR TSOT23-6")
      (fields (field (name "DIGI-KEY PART NUMBER") "LTC6993CS6-3#TRMPBFDKR-ND"))
      (libsource (lib "SssAccesDatbase") (part "LTC6993CS6-3#TRMPBF"))
    )
    (comp (ref "DA11")
      (value "LTV-816S")
      (footprint "LTV-816S")
      (description "OPTOISOLATR 5KV TRANSISTOR 4-SMD")
      (fields (field (name "DIGI-KEY PART NUMBER") "160-1361-5-ND"))
      (libsource (lib "SssAccesDatbase") (part "TCMT1103"))
    )
    (comp (ref "DA12")
      (value "LTV-816S")
      (footprint "LTV-816S")
      (description "OPTOISOLATR 5KV TRANSISTOR 4-SMD")
      (fields (field (name "DIGI-KEY PART NUMBER") "160-1361-5-ND"))
      (libsource (lib "SssAccesDatbase") (part "TCMT1103"))
    )
    (comp (ref "DA13")
      (value "MCP73832T-2DFI/OT")
      (footprint "SOT-23-5")
      (description "IC LI-ION/LI-POLY CTRLR SOT23-5")
      (fields (field (name "DIGI-KEY PART NUMBER") "MCP73832T-2DFI/OTCT-ND"))
      (libsource (lib "SssAccesDatbase") (part "MCP73832T-2DFI/OT"))
    )
    (comp (ref "DD1")
      (value "MAX8903AETI+")
      (footprint "QFN40P400X400X80-29N")
      (description "IC BATT CHG LI-ION 1CELL 28TQFN")
      (fields
        (field (name "MOUSER PART NUMBER") "700-MAX8903AETI")
        (field (name "DIGI-KEY PART NUMBER") "MAX8903AETI+-ND")
      )
      (libsource (lib "SssAccesDatbase") (part "MAX8903AETI+"))
    )
    (comp (ref "DD2")
      (value "MAX17047G+T10")
      (footprint "DFN10(3x3)_N")
      (description "IC BATT MONITOR LI-ION 10TDFN")
      (fields (field (name "DIGI-KEY PART NUMBER") "MAX17047G+T10-ND"))
      (libsource (lib "SssAccesDatbase") (part "MAX17047G+T10"))
    )
    (comp (ref "DD3")
      (value "CYW20737A1KML2G")
      (footprint "QFN5X5-32_N")
      (description "IC RF TXRX+MCU BLUETOOTH 32VFQFN")
      (fields (field (name "DIGI-KEY PART NUMBER") "2015-CYW20737A1KML2G-ND"))
      (libsource (lib "SssAccesDatbase") (part "CYW20737A1KML2G"))
    )
    (comp (ref "DD4")
      (value "LSM6DSMTR")
      (footprint "LGA-14L_2P5X3X0P83_STM-M")
      (description "IMU ACCEL/GYRO I2C/SPI 14LGA")
      (fields
        (field (name "DIGI-KEY PART NUMBER") "497-16696-1-ND")
        (field (name "MOUSER PART NUMBER") "511-LSM6DSMTR")
        (field (name "COPYRIGHT") "Copyright (C) 2018 Accelerated Designs. All rights reserved")
      )
      (libsource (lib "SssAccesDatbase") (part "LSM6DSMTR"))
    )
    (comp (ref "DD5")
      (value "MX25R4035FM1IL0 4Mb SPI")
      (footprint "MCHP-SOIC-SN8_M")
      (description "IC FLASH 4M SPI 33MHZ 8SOP")
      (fields (field (name "PART NUMBER") "MX25R4035FM1IL0"))
      (libsource (lib "SssAccesDatbase") (part "MX25R4035FM1IL0"))
    )
    (comp (ref "DD6")
      (value "FT230XQ-R")
      (footprint "QFN-16(4x4)")
      (description "IC USB SERIAL BASIC UART 16QFN")
      (fields (field (name "DIGI-KEY PART NUMBER") "768-1130-1-ND"))
      (libsource (lib "SssAccesDatbase") (part "FT230XQ-R"))
    )
    (comp (ref "DD7")
      (value "ATSAML10D16A-MUT")
      (footprint "VQFN-24")
      (description "IC MCU 32BIT 64KB FLASH 24VQFN,ARM® Cortex®-M23")
      (fields (field (name "DIGI-KEY PART NUMBER") "ATSAML10D16A-MUTCT-ND"))
      (libsource (lib "SssAccesDatbase") (part "ATSAML10D16A-MUT"))
    )
    (comp (ref "DD8")
      (value "LSM6DSMTR")
      (footprint "LGA-14L_2P5X3X0P83_STM-M")
      (description "IMU ACCEL/GYRO I2C/SPI 14LGA")
      (fields
        (field (name "DIGI-KEY PART NUMBER") "497-16696-1-ND")
        (field (name "MOUSER PART NUMBER") "511-LSM6DSMTR")
        (field (name "COPYRIGHT") "Copyright (C) 2018 Accelerated Designs. All rights reserved")
      )
      (libsource (lib "SssAccesDatbase") (part "LSM6DSMTR"))
    )
    (comp (ref "G1")
      (value "24.0000MHZ 10ppM")
      (footprint "TSX-3225")
      (description "24MHz ±10ppm Crystal 9pF 40 Ohms 4-SMD, No Lead")
      (fields
        (field (name "PART NUMBER") "TSX-3225 24.0000MF15X-AC6")
        (field (name "DIGI-KEY PART NUMBER") "SER4180CT-ND")
      )
      (libsource (lib "SssAccesDatbase") (part "CTX957CT"))
    )
    (comp (ref "G2")
      (value "32.768kHz ±20ppm")
      (footprint "VMK3-9005")
      (description "32.768kHz ±20ppm Crystal   2-SMD, No Lead")
      (fields
        (field (name "PART NUMBER") "VMK3-9005-32K7680000")
        (field (name "DIGI-KEY PART NUMBER") "150-VMK3-9005-32K7680000CT-ND")
      )
      (libsource (lib "SssAccesDatbase") (part "Crystal"))
    )
    (comp (ref "HL1")
      (value "GR-0603")
      (footprint "LED-0603-GREEN")
      (description "LED GREEN DIFFUSED 0603 SMD")
      (fields
        (field (name "PART NUMBER") "150060VS55040")
        (field (name "DIGI-KEY PART NUMBER") "732-12017-1-ND")
      )
      (libsource (lib "SssAccesDatbase") (part "LED_AK"))
    )
    (comp (ref "HL2")
      (value "GR-0603")
      (footprint "LED-0603-GREEN")
      (description "LED GREEN DIFFUSED 0603 SMD")
      (fields
        (field (name "PART NUMBER") "150060VS55040")
        (field (name "DIGI-KEY PART NUMBER") "732-12017-1-ND")
      )
      (libsource (lib "SssAccesDatbase") (part "LED_AK"))
    )
    (comp (ref "HL3")
      (value "GR-0603")
      (footprint "LED-0603-GREEN")
      (description "LED GREEN DIFFUSED 0603 SMD")
      (fields
        (field (name "PART NUMBER") "150060VS55040")
        (field (name "DIGI-KEY PART NUMBER") "732-12017-1-ND")
      )
      (libsource (lib "SssAccesDatbase") (part "LED_AK"))
    )
    (comp (ref "HL4")
      (value "GR-0603")
      (footprint "LED-0603-GREEN")
      (description "LED GREEN DIFFUSED 0603 SMD")
      (fields
        (field (name "PART NUMBER") "150060VS55040")
        (field (name "DIGI-KEY PART NUMBER") "732-12017-1-ND")
      )
      (libsource (lib "SssAccesDatbase") (part "LED_AK"))
    )
    (comp (ref "HL5")
      (value "GR-0603")
      (footprint "LED-0603-GREEN")
      (description "LED GREEN DIFFUSED 0603 SMD")
      (fields
        (field (name "PART NUMBER") "150060VS55040")
        (field (name "DIGI-KEY PART NUMBER") "732-12017-1-ND")
      )
      (libsource (lib "SssAccesDatbase") (part "LED_AK"))
    )
    (comp (ref "HL6")
      (value "GR-0603")
      (footprint "LED-0603-GREEN")
      (description "LED GREEN DIFFUSED 0603 SMD")
      (fields
        (field (name "PART NUMBER") "150060VS55040")
        (field (name "DIGI-KEY PART NUMBER") "732-12017-1-ND")
      )
      (libsource (lib "SssAccesDatbase") (part "LED_AK"))
    )
    (comp (ref "HL7")
      (value "GR-0603")
      (footprint "LED-0603-GREEN")
      (description "LED GREEN DIFFUSED 0603 SMD")
      (fields
        (field (name "PART NUMBER") "150060VS55040")
        (field (name "DIGI-KEY PART NUMBER") "732-12017-1-ND")
      )
      (libsource (lib "SssAccesDatbase") (part "LED_AK"))
    )
    (comp (ref "HL8")
      (value "Bl 0603")
      (footprint "LED-0603-BLUE")
      (description "LED BLUE DIFFUSED 0603 SMD")
      (fields
        (field (name "PART NUMBER") "150060BS55040")
        (field (name "DIGI-KEY PART NUMBER") "732-12013-1-ND")
      )
      (libsource (lib "SssAccesDatbase") (part "LED_AK"))
    )
    (comp (ref "HL9")
      (value "Bl 0603")
      (footprint "LED-0603-BLUE")
      (description "LED BLUE DIFFUSED 0603 SMD")
      (fields
        (field (name "PART NUMBER") "150060BS55040")
        (field (name "DIGI-KEY PART NUMBER") "732-12013-1-ND")
      )
      (libsource (lib "SssAccesDatbase") (part "LED_AK"))
    )
    (comp (ref "HL10")
      (value "Bl 0603")
      (footprint "LED-0603-BLUE")
      (description "LED BLUE DIFFUSED 0603 SMD")
      (fields
        (field (name "PART NUMBER") "150060BS55040")
        (field (name "DIGI-KEY PART NUMBER") "732-12013-1-ND")
      )
      (libsource (lib "SssAccesDatbase") (part "LED_AK"))
    )
    (comp (ref "HL11")
      (value "Bl 0603")
      (footprint "LED-0603-BLUE")
      (description "LED BLUE DIFFUSED 0603 SMD")
      (fields
        (field (name "PART NUMBER") "150060BS55040")
        (field (name "DIGI-KEY PART NUMBER") "732-12013-1-ND")
      )
      (libsource (lib "SssAccesDatbase") (part "LED_AK"))
    )
    (comp (ref "HL12")
      (value "Bl 0603")
      (footprint "LED-0603-BLUE")
      (description "LED BLUE DIFFUSED 0603 SMD")
      (fields
        (field (name "PART NUMBER") "150060BS55040")
        (field (name "DIGI-KEY PART NUMBER") "732-12013-1-ND")
      )
      (libsource (lib "SssAccesDatbase") (part "LED_AK"))
    )
    (comp (ref "HL13")
      (value "Bl 0603")
      (footprint "LED-0603-BLUE")
      (description "LED BLUE DIFFUSED 0603 SMD")
      (fields
        (field (name "PART NUMBER") "150060BS55040")
        (field (name "DIGI-KEY PART NUMBER") "732-12013-1-ND")
      )
      (libsource (lib "SssAccesDatbase") (part "LED_AK"))
    )
    (comp (ref "HL14")
      (value "Bl 0603")
      (footprint "LED-0603-BLUE")
      (description "LED BLUE DIFFUSED 0603 SMD")
      (fields
        (field (name "PART NUMBER") "150060BS55040")
        (field (name "DIGI-KEY PART NUMBER") "732-12013-1-ND")
      )
      (libsource (lib "SssAccesDatbase") (part "LED_AK"))
    )
    (comp (ref "HL15")
      (value "Bl 0603")
      (footprint "LED-0603-BLUE")
      (description "LED BLUE DIFFUSED 0603 SMD")
      (fields
        (field (name "PART NUMBER") "150060BS55040")
        (field (name "DIGI-KEY PART NUMBER") "732-12013-1-ND")
      )
      (libsource (lib "SssAccesDatbase") (part "LED_AK"))
    )
    (comp (ref "HL16")
      (value "Bl 0603")
      (footprint "LED-0603-BLUE")
      (description "LED BLUE DIFFUSED 0603 SMD")
      (fields
        (field (name "PART NUMBER") "150060BS55040")
        (field (name "DIGI-KEY PART NUMBER") "732-12013-1-ND")
      )
      (libsource (lib "SssAccesDatbase") (part "LED_AK"))
    )
    (comp (ref "HL17")
      (value "Bl 0603")
      (footprint "LED-0603-BLUE")
      (description "LED BLUE DIFFUSED 0603 SMD")
      (fields
        (field (name "PART NUMBER") "150060BS55040")
        (field (name "DIGI-KEY PART NUMBER") "732-12013-1-ND")
      )
      (libsource (lib "SssAccesDatbase") (part "LED_AK"))
    )
    (comp (ref "K1")
      (value "5V 3A 250VAC")
      (footprint "SRS-05VDC-SL")
      (fields (field (name "PART NUMBER") "SRS-05VDC-SL"))
      (libsource (lib "SssAccesDatbase") (part "HJR-21FF-24VDC-S-Z_1"))
    )
    (comp (ref "L1")
      (value "2.5UH 5A 27 MOHM")
      (footprint "SDE0805A")
      (description "FIXED IND 2.5UH 5A 27 MOHM SMD")
      (fields
        (field (name "PART NUMBER") "SDE0805A-2R5M")
        (field (name "DIGI-KEY PART NUMBER") "SDE0805A-2R5MCT-ND")
        (field (name "PUBLISHER") "Altium Limited")
      )
      (libsource (lib "SssAccesDatbase") (part "Inductor Iron"))
    )
    (comp (ref "L2")
      (value "1u 3.2A 32.4mOhm")
      (footprint "NRS4018")
      (description "FIXED IND 1UH 3.2A 32.4 MOHM SMD")
      (fields
        (field (name "PART NUMBER") "NRS4018T1R0NDGJ")
        (field (name "DIGI-KEY PART NUMBER") "587-2888-1-ND")
      )
      (libsource (lib "SssAccesDatbase") (part "L"))
    )
    (comp (ref "L3")
      (value "0 ohm NoBom")
      (footprint "INDC1608(0603)N")
      (description "Fixed Inductors 270nH 2% -40C +125C")
      (fields
        (field (name "PART NUMBER") "AISC-0603-R27G-T")
        (field (name "MOUSER PART NUMBER") "815-AISC0603R27GT")
      )
      (libsource (lib "SssAccesDatbase") (part "L"))
    )
    (comp (ref "L4")
      (value "0 ohm NoBom")
      (footprint "INDC1608(0603)N")
      (description "Fixed Inductors 270nH 2% -40C +125C")
      (fields
        (field (name "PART NUMBER") "AISC-0603-R27G-T")
        (field (name "MOUSER PART NUMBER") "815-AISC0603R27GT")
      )
      (libsource (lib "SssAccesDatbase") (part "L"))
    )
    (comp (ref "L5")
      (value "2.2UH 1.3")
      (footprint "CDRH2D11")
      (description "FIXED IND 2.2UH 1.3A 120 MOHM")
      (fields
        (field (name "PART NUMBER") "CDRH2D11/HPNP-2R2NC")
        (field (name "DIGI-KEY PART NUMBER") "308-1578-1-ND")
        (field (name "PUBLISHER") "Altium Limited")
      )
      (libsource (lib "SssAccesDatbase") (part "Inductor ferrite"))
    )
    (comp (ref "L6")
      (value "2.2UH 1.3")
      (footprint "CDRH2D11")
      (description "FIXED IND 2.2UH 1.3A 120 MOHM")
      (fields
        (field (name "PART NUMBER") "CDRH2D11/HPNP-2R2NC")
        (field (name "DIGI-KEY PART NUMBER") "308-1578-1-ND")
        (field (name "PUBLISHER") "Altium Limited")
      )
      (libsource (lib "") (part "Inductor ferrite_1"))
    )
    (comp (ref "R1")
      (value "10k")
      (footprint "REZKemet 0402")
      (description "RES 10K OHM 1% 1/16W 0402")
      (fields
        (field (name "PART NUMBER") "RESC1005(0402)")
        (field (name "MANUFACTURER PART NUMBER") "CRCW040210K0FKEDC")
      )
      (libsource (lib "") (part "Resistor general_3"))
    )
    (comp (ref "R2")
      (value "0")
      (footprint "REZKemet 0402")
      (description "RES SMD 0402 0 Ohm")
      (fields
        (field (name "PART NUMBER") "RMCF0402ZT0R00")
        (field (name "MOUSER PART NUMBER") "RMCF0402ZT0R00CT-ND")
      )
      (libsource (lib "") (part "Resistor general_6"))
    )
    (comp (ref "R3")
      (value "?")
      (footprint "REZKemet 0402")
      (fields (field (name "PART NUMBER") "RESC1005(0402)"))
      (libsource (lib "SssAccesDatbase") (part "Resistor general"))
    )
    (comp (ref "R4")
      (value "10k")
      (footprint "REZKemet 0402")
      (description "RES SMD 5.1K OHM 1% 1/10W 0402")
      (fields
        (field (name "PART NUMBER") "RESC1005(0402)")
        (field (name "MANUFACTURER PART NUMBER") "ERJ-2RKF5101X")
      )
      (libsource (lib "") (part "Resistor general_5"))
    )
    (comp (ref "R5")
      (value "620")
      (footprint "REZKemet 0402")
      (description "RES SMD 620 OHM 1% 1/16W 0402")
      (fields
        (field (name "PART NUMBER") "RESC1005(0402)")
        (field (name "DIGI-KEY PART NUMBER") "311-620LRCT-ND")
      )
      (libsource (lib "") (part "Resistor general_1"))
    )
    (comp (ref "R6")
      (value "10k")
      (footprint "REZKemet 0402")
      (description "RES 10K OHM 1% 1/16W 0402")
      (fields
        (field (name "PART NUMBER") "RESC1005(0402)")
        (field (name "MANUFACTURER PART NUMBER") "CRCW040210K0FKEDC")
      )
      (libsource (lib "") (part "Resistor general_4"))
    )
    (comp (ref "R7")
      (value "?")
      (footprint "REZKemet 0402")
      (fields (field (name "PART NUMBER") "RESC1005(0402)"))
      (libsource (lib "SssAccesDatbase") (part "Resistor general"))
    )
    (comp (ref "R8")
      (value "158")
      (footprint "REZKemet 0402")
      (description "RES SMD 158 OHM 1% 1/10W 0402")
      (fields
        (field (name "PART NUMBER") "RESC1005(0402)")
        (field (name "DIGI-KEY PART NUMBER") "P158LCT-ND")
      )
      (libsource (lib "") (part "Resistor general_4"))
    )
    (comp (ref "R9")
      (value "1k")
      (footprint "REZKemet 0402")
      (description "RES SMD 1K OHM 0.5% 1/16W 0402")
      (fields
        (field (name "PART NUMBER") "RESC1005(0402)")
        (field (name "DIGI-KEY PART NUMBER") "RR05P1.0KDCT-ND")
      )
      (libsource (lib "") (part "Resistor general_4"))
    )
    (comp (ref "R10")
      (value "10k")
      (footprint "REZKemet 0402")
      (description "RES SMD 5.1K OHM 1% 1/10W 0402")
      (fields
        (field (name "PART NUMBER") "RESC1005(0402)")
        (field (name "MANUFACTURER PART NUMBER") "ERJ-2RKF5101X")
      )
      (libsource (lib "") (part "Resistor general_3"))
    )
    (comp (ref "R11")
      (value "221")
      (footprint "REZKemet 0402")
      (description "RES 221 OHM 1% 1/16W 0402")
      (fields
        (field (name "PART NUMBER") "RESC1005(0402)")
        (field (name "DIGI-KEY PART NUMBER") "RMCF0402FT221RCT-ND")
      )
      (libsource (lib "") (part "Resistor general_4"))
    )
    (comp (ref "R12")
      (value "2.8k")
      (footprint "REZKemet 0402")
      (description "RES 2.8K OHM 1% 1/10W 0402")
      (fields
        (field (name "PART NUMBER") "RESC1005(0402)")
        (field (name "DIGI-KEY PART NUMBER") "2019-RK73H1ETTP2801FCT-ND")
      )
      (libsource (lib "") (part "Resistor general_4"))
    )
    (comp (ref "R13")
      (value "10m 1% 50ppm")
      (footprint "RESC2012(0805)N")
      (description "RES SMD 0805 10m 1% 50ppm")
      (fields
        (field (name "PART NUMBER") "KRL1220E-M-R010-F-T5")
        (field (name "MOUSER PART NUMBER") "408-1544-1-ND")
      )
      (libsource (lib "") (part "Resistor general_1"))
    )
    (comp (ref "R14")
      (value "620")
      (footprint "REZKemet 0402")
      (fields (field (name "PART NUMBER") "RESC1005(0402)"))
      (libsource (lib "SssAccesDatbase") (part "Resistor general"))
    )
    (comp (ref "R15")
      (value "620")
      (footprint "REZKemet 0402")
      (fields (field (name "PART NUMBER") "RESC1005(0402)"))
      (libsource (lib "") (part "Resistor general_6"))
    )
    (comp (ref "R16")
      (value "10k")
      (footprint "REZKemet 0402")
      (description "RES SMD 5.1K OHM 1% 1/10W 0402")
      (fields
        (field (name "PART NUMBER") "RESC1005(0402)")
        (field (name "MANUFACTURER PART NUMBER") "ERJ-2RKF5101X")
      )
      (libsource (lib "") (part "Resistor general_3"))
    )
    (comp (ref "R17")
      (value "10k")
      (footprint "REZKemet 0402")
      (description "RES 10K OHM 1% 1/16W 0402")
      (fields
        (field (name "PART NUMBER") "RESC1005(0402)")
        (field (name "MANUFACTURER PART NUMBER") "CRCW040210K0FKEDC")
      )
      (libsource (lib "") (part "Resistor general_3"))
    )
    (comp (ref "R18")
      (value "10k")
      (footprint "REZKemet 0402")
      (description "RES 10K OHM 1% 1/16W 0402")
      (fields
        (field (name "PART NUMBER") "RESC1005(0402)")
        (field (name "MANUFACTURER PART NUMBER") "CRCW040210K0FKEDC")
      )
      (libsource (lib "") (part "Resistor general_3"))
    )
    (comp (ref "R19")
      (value "10k")
      (footprint "REZKemet 0402")
      (description "RES 10K OHM 1% 1/16W 0402")
      (fields
        (field (name "PART NUMBER") "RESC1005(0402)")
        (field (name "MANUFACTURER PART NUMBER") "CRCW040210K0FKEDC")
      )
      (libsource (lib "") (part "Resistor general_2"))
    )
    (comp (ref "R20")
      (value "10k")
      (footprint "REZKemet 0402")
      (description "RES SMD 5.1K OHM 1% 1/10W 0402")
      (fields
        (field (name "PART NUMBER") "RESC1005(0402)")
        (field (name "MANUFACTURER PART NUMBER") "ERJ-2RKF5101X")
      )
      (libsource (lib "") (part "Resistor general_5"))
    )
    (comp (ref "R21")
      (value "10k")
      (footprint "REZKemet 0402")
      (description "RES 10K OHM 1% 1/16W 0402")
      (fields
        (field (name "PART NUMBER") "RESC1005(0402)")
        (field (name "MANUFACTURER PART NUMBER") "CRCW040210K0FKEDC")
      )
      (libsource (lib "") (part "Resistor general_3"))
    )
    (comp (ref "R22")
      (value "10k")
      (footprint "REZKemet 0402")
      (description "RES 10K OHM 1% 1/16W 0402")
      (fields
        (field (name "PART NUMBER") "RESC1005(0402)")
        (field (name "MANUFACTURER PART NUMBER") "CRCW040210K0FKEDC")
      )
      (libsource (lib "") (part "Resistor general_3"))
    )
    (comp (ref "R23")
      (value "10k")
      (footprint "REZKemet 0402")
      (description "RES 10K OHM 1% 1/16W 0402")
      (fields
        (field (name "PART NUMBER") "RESC1005(0402)")
        (field (name "MANUFACTURER PART NUMBER") "CRCW040210K0FKEDC")
      )
      (libsource (lib "") (part "Resistor general_3"))
    )
    (comp (ref "R24")
      (value "2.2k")
      (footprint "REZKemet 0402")
      (description "RES SMD 2.2K OHM 1% 1/16W 0402")
      (fields
        (field (name "PART NUMBER") "RESC1005(0402)")
        (field (name "DIGI-KEY PART NUMBER") "311-2.20KLRCT-ND")
      )
      (libsource (lib "") (part "Resistor general_2"))
    )
    (comp (ref "R25")
      (value "2.2k")
      (footprint "REZKemet 0402")
      (description "RES SMD 2.2K OHM 1% 1/16W 0402")
      (fields
        (field (name "PART NUMBER") "RESC1005(0402)")
        (field (name "DIGI-KEY PART NUMBER") "311-2.20KLRCT-ND")
      )
      (libsource (lib "") (part "Resistor general_2"))
    )
    (comp (ref "R26")
      (value "680")
      (footprint "REZKemet 0402")
      (fields (field (name "PART NUMBER") "RESC1005(0402)"))
      (libsource (lib "SssAccesDatbase") (part "Resistor general"))
    )
    (comp (ref "R27")
      (value "680")
      (footprint "REZKemet 0402")
      (fields (field (name "PART NUMBER") "RESC1005(0402)"))
      (libsource (lib "SssAccesDatbase") (part "Resistor general"))
    )
    (comp (ref "R28")
      (value "12k")
      (footprint "REZKemet 0402")
      (fields (field (name "PART NUMBER") "RESC1005(0402)"))
      (libsource (lib "SssAccesDatbase") (part "Resistor general"))
    )
    (comp (ref "R29")
      (value "3k")
      (footprint "REZKemet 0402")
      (fields (field (name "PART NUMBER") "RESC1005(0402)"))
      (libsource (lib "SssAccesDatbase") (part "Resistor general"))
    )
    (comp (ref "R30")
      (value "680")
      (footprint "REZKemet 0402")
      (fields (field (name "PART NUMBER") "RESC1005(0402)"))
      (libsource (lib "SssAccesDatbase") (part "Resistor general"))
    )
    (comp (ref "R31")
      (value "680")
      (footprint "REZKemet 0402")
      (fields (field (name "PART NUMBER") "RESC1005(0402)"))
      (libsource (lib "SssAccesDatbase") (part "Resistor general"))
    )
    (comp (ref "R32")
      (value "600")
      (footprint "REZKemet 0402")
      (fields (field (name "PART NUMBER") "RESC1005(0402)"))
      (libsource (lib "SssAccesDatbase") (part "Resistor general"))
    )
    (comp (ref "R33")
      (value "5.23k")
      (footprint "REZKemet 0402")
      (description "RES 5.23K OHM 1% 1/16W 0402")
      (fields
        (field (name "PART NUMBER") "RESC1005(0402)")
        (field (name "DIGI-KEY PART NUMBER") "RMCF0402FT5K23CT-ND")
      )
      (libsource (lib "") (part "Resistor general_5"))
    )
    (comp (ref "R34")
      (value "10M 5%")
      (footprint "REZKemet 0402")
      (description "RES SMD 0402 10 MOhm 5% 200ppm")
      (fields
        (field (name "PART NUMBER") "RMCF0402JT10M0")
        (field (name "DIGI-KEY PART NUMBER") "RMCF0402JT10M0CT-ND")
      )
      (libsource (lib "SssAccesDatbase") (part "Resistor general"))
    )
    (comp (ref "R35")
      (value "30.1k")
      (footprint "REZKemet 0402")
      (description "RES 30.1K OHM 1% 1/16W 0402")
      (fields
        (field (name "PART NUMBER") "RESC1005(0402)")
        (field (name "DIGI-KEY PART NUMBER") "RMCF0402FT30K1CT-ND")
      )
      (libsource (lib "") (part "Resistor general_3"))
    )
    (comp (ref "R36")
      (value "0")
      (footprint "REZKemet 0402")
      (description "RES SMD 0402 0 Ohm")
      (fields
        (field (name "PART NUMBER") "RMCF0402ZT0R00")
        (field (name "MOUSER PART NUMBER") "RMCF0402ZT0R00CT-ND")
      )
      (libsource (lib "") (part "Resistor general_1"))
    )
    (comp (ref "R37")
      (value "620")
      (footprint "REZKemet 0402")
      (fields (field (name "PART NUMBER") "RESC1005(0402)"))
      (libsource (lib "") (part "Resistor general_1"))
    )
    (comp (ref "R38")
      (value "620")
      (footprint "REZKemet 0402")
      (fields (field (name "PART NUMBER") "RESC1005(0402)"))
      (libsource (lib "") (part "Resistor general_1"))
    )
    (comp (ref "R39")
      (value "620")
      (footprint "REZKemet 0402")
      (fields (field (name "PART NUMBER") "RESC1005(0402)"))
      (libsource (lib "SssAccesDatbase") (part "Resistor general"))
    )
    (comp (ref "R40")
      (value "?")
      (footprint "REZKemet 0402")
      (fields (field (name "PART NUMBER") "RESC1005(0402)"))
      (libsource (lib "SssAccesDatbase") (part "Resistor general"))
    )
    (comp (ref "R41")
      (value "?")
      (footprint "REZKemet 0402")
      (fields (field (name "PART NUMBER") "RESC1005(0402)"))
      (libsource (lib "SssAccesDatbase") (part "Resistor general"))
    )
    (comp (ref "R42")
      (value "0")
      (footprint "REZKemet 0402")
      (description "RES SMD 0402 0 Ohm")
      (fields
        (field (name "PART NUMBER") "RMCF0402ZT0R00")
        (field (name "MOUSER PART NUMBER") "RMCF0402ZT0R00CT-ND")
      )
      (libsource (lib "") (part "Resistor general_1"))
    )
    (comp (ref "R43")
      (value "0")
      (footprint "REZKemet 0402")
      (description "RES SMD 0402 0 Ohm")
      (fields
        (field (name "PART NUMBER") "RMCF0402ZT0R00")
        (field (name "MOUSER PART NUMBER") "RMCF0402ZT0R00CT-ND")
      )
      (libsource (lib "") (part "Resistor general_1"))
    )
    (comp (ref "R44")
      (value "0")
      (footprint "REZKemet 0402")
      (description "RES SMD 0402 0 Ohm")
      (fields
        (field (name "PART NUMBER") "RMCF0402ZT0R00")
        (field (name "MOUSER PART NUMBER") "RMCF0402ZT0R00CT-ND")
      )
      (libsource (lib "") (part "Resistor general_1"))
    )
    (comp (ref "R45")
      (value "0")
      (footprint "REZKemet 0402")
      (description "RES SMD 0402 0 Ohm")
      (fields
        (field (name "PART NUMBER") "RMCF0402ZT0R00")
        (field (name "MOUSER PART NUMBER") "RMCF0402ZT0R00CT-ND")
      )
      (libsource (lib "") (part "Resistor general_1"))
    )
    (comp (ref "R46")
      (value "0")
      (footprint "REZKemet 0402")
      (description "RES SMD 0402 0 Ohm")
      (fields
        (field (name "PART NUMBER") "RMCF0402ZT0R00")
        (field (name "MOUSER PART NUMBER") "RMCF0402ZT0R00CT-ND")
      )
      (libsource (lib "") (part "Resistor general_1"))
    )
    (comp (ref "R47")
      (value "620")
      (footprint "REZKemet 0402")
      (fields (field (name "PART NUMBER") "RESC1005(0402)"))
      (libsource (lib "SssAccesDatbase") (part "Resistor general"))
    )
    (comp (ref "R48")
      (value "5.1k")
      (footprint "REZKemet 0402")
      (description "RES SMD 5.1K OHM 1% 1/10W 0402")
      (fields
        (field (name "PART NUMBER") "RESC1005(0402)")
        (field (name "MANUFACTURER PART NUMBER") "ERJ-2RKF5101X")
      )
      (libsource (lib "") (part "Resistor general_2"))
    )
    (comp (ref "R49")
      (value "5.1k")
      (footprint "REZKemet 0402")
      (description "RES SMD 5.1K OHM 1% 1/10W 0402")
      (fields
        (field (name "PART NUMBER") "RESC1005(0402)")
        (field (name "MANUFACTURER PART NUMBER") "ERJ-2RKF5101X")
      )
      (libsource (lib "") (part "Resistor general_2"))
    )
    (comp (ref "R50")
      (value "620")
      (footprint "REZKemet 0402")
      (fields (field (name "PART NUMBER") "RESC1005(0402)"))
      (libsource (lib "") (part "Resistor general_1"))
    )
    (comp (ref "R51")
      (value "196")
      (footprint "REZKemet 0402")
      (description "RES SMD 5.1K OHM 1% 1/10W 0402")
      (fields
        (field (name "PART NUMBER") "RESC1005(0402)")
        (field (name "MANUFACTURER PART NUMBER") "ERJ-2RKF5101X")
      )
      (libsource (lib "") (part "Resistor general_2"))
    )
    (comp (ref "R52")
      (value "1k")
      (footprint "RESC1608(0603)N")
      (fields (field (name "PART NUMBER") "RESC1608(0603)"))
      (libsource (lib "") (part "Resistor general_1"))
    )
    (comp (ref "R53")
      (value "1k")
      (footprint "RESC1608(0603)N")
      (fields (field (name "PART NUMBER") "RESC1608(0603)"))
      (libsource (lib "SssAccesDatbase") (part "Resistor general"))
    )
    (comp (ref "R54")
      (value "1k")
      (footprint "RESC1608(0603)N")
      (fields (field (name "PART NUMBER") "RESC1608(0603)"))
      (libsource (lib "") (part "Resistor general_1"))
    )
    (comp (ref "R55")
      (value "1k")
      (footprint "RESC1608(0603)N")
      (fields (field (name "PART NUMBER") "RESC1608(0603)"))
      (libsource (lib "") (part "Resistor general_1"))
    )
    (comp (ref "R56")
      (value "1k")
      (footprint "REZKemet 0402")
      (fields (field (name "PART NUMBER") "RESC1005(0402)"))
      (libsource (lib "") (part "Resistor general_7"))
    )
    (comp (ref "R57")
      (value "1k")
      (footprint "REZKemet 0402")
      (fields (field (name "PART NUMBER") "RESC1005(0402)"))
      (libsource (lib "") (part "Resistor general_6"))
    )
    (comp (ref "R58")
      (value "1k")
      (footprint "REZKemet 0402")
      (fields (field (name "PART NUMBER") "RESC1005(0402)"))
      (libsource (lib "") (part "Resistor general_6"))
    )
    (comp (ref "R59")
      (value "620")
      (footprint "REZKemet 0402")
      (fields (field (name "PART NUMBER") "RESC1005(0402)"))
      (libsource (lib "") (part "Resistor general_6"))
    )
    (comp (ref "R60")
      (value "50k")
      (footprint "REZKemet 0402")
      (description "RES SMD 5.1K OHM 1% 1/10W 0402")
      (fields
        (field (name "PART NUMBER") "RESC1005(0402)")
        (field (name "MANUFACTURER PART NUMBER") "ERJ-2RKF5101X")
      )
      (libsource (lib "") (part "Resistor general_2"))
    )
    (comp (ref "R61")
      (value "2M")
      (footprint "REZKemet 0402")
      (description "RES SMD 5.1K OHM 1% 1/10W 0402")
      (fields
        (field (name "PART NUMBER") "RESC1005(0402)")
        (field (name "MANUFACTURER PART NUMBER") "ERJ-2RKF5101X")
      )
      (libsource (lib "") (part "Resistor general_2"))
    )
    (comp (ref "R62")
      (value "2M")
      (footprint "REZKemet 0402")
      (description "RES SMD 5.1K OHM 1% 1/10W 0402")
      (fields
        (field (name "PART NUMBER") "RESC1005(0402)")
        (field (name "MANUFACTURER PART NUMBER") "ERJ-2RKF5101X")
      )
      (libsource (lib "") (part "Resistor general_2"))
    )
    (comp (ref "R63")
      (value "1M")
      (footprint "REZKemet 0402")
      (description "RES SMD 5.1K OHM 1% 1/10W 0402")
      (fields
        (field (name "PART NUMBER") "RESC1005(0402)")
        (field (name "MANUFACTURER PART NUMBER") "ERJ-2RKF5101X")
      )
      (libsource (lib "") (part "Resistor general_2"))
    )
    (comp (ref "R64")
      (value "620")
      (footprint "REZKemet 0402")
      (fields (field (name "PART NUMBER") "RESC1005(0402)"))
      (libsource (lib "") (part "Resistor general_6"))
    )
    (comp (ref "R65")
      (value "10k")
      (footprint "RESC1608(0603)N")
      (fields (field (name "PART NUMBER") "RESC1608(0603)"))
      (libsource (lib "SssAccesDatbase") (part "Resistor general"))
    )
    (comp (ref "R66")
      (value "10k")
      (footprint "RESC1608(0603)N")
      (fields (field (name "PART NUMBER") "RESC1608(0603)"))
      (libsource (lib "SssAccesDatbase") (part "Resistor general"))
    )
    (comp (ref "R67")
      (value "1k")
      (footprint "RESC1608(0603)N")
      (fields (field (name "PART NUMBER") "RESC1608(0603)"))
      (libsource (lib "") (part "Resistor general_1"))
    )
    (comp (ref "R68")
      (value "620")
      (footprint "REZKemet 0402")
      (fields (field (name "PART NUMBER") "RESC1005(0402)"))
      (libsource (lib "SssAccesDatbase") (part "Resistor general"))
    )
    (comp (ref "R69")
      (value "5.1k")
      (footprint "REZKemet 0402")
      (description "RES SMD 5.1K OHM 1% 1/10W 0402")
      (fields
        (field (name "PART NUMBER") "RESC1005(0402)")
        (field (name "MANUFACTURER PART NUMBER") "ERJ-2RKF5101X")
      )
      (libsource (lib "") (part "Resistor general_5"))
    )
    (comp (ref "R70")
      (value "5.1k")
      (footprint "REZKemet 0402")
      (description "RES SMD 5.1K OHM 1% 1/10W 0402")
      (fields
        (field (name "PART NUMBER") "RESC1005(0402)")
        (field (name "MANUFACTURER PART NUMBER") "ERJ-2RKF5101X")
      )
      (libsource (lib "") (part "Resistor general_5"))
    )
    (comp (ref "RP1")
      (value "10K")
      (footprint "3296W_1")
      (description "Trimm Res TH 3/8  10K  0,5W  100ppm Vert Adj")
      (fields
        (field (name "MANUFACTURER PART NUMBER") "3296W-1-103LF")
        (field (name "MOUSER PART NUMBER") "652-3296W-1-103LF")
      )
      (libsource (lib "SssAccesDatbase") (part "Pot_1"))
    )
    (comp (ref "RP2")
      (value "10K")
      (footprint "3296W_1")
      (description "Trimm Res TH 3/8  10K  0,5W  100ppm Vert Adj")
      (fields
        (field (name "MANUFACTURER PART NUMBER") "3296W-1-103LF")
        (field (name "MOUSER PART NUMBER") "652-3296W-1-103LF")
      )
      (libsource (lib "SssAccesDatbase") (part "Pot_1"))
    )
    (comp (ref "RP3")
      (value "10K")
      (footprint "3296W_1")
      (description "Trimm Res TH 3/8  10K  0,5W  100ppm Vert Adj")
      (fields
        (field (name "MANUFACTURER PART NUMBER") "3296W-1-103LF")
        (field (name "MOUSER PART NUMBER") "652-3296W-1-103LF")
      )
      (libsource (lib "SssAccesDatbase") (part "Pot_1"))
    )
    (comp (ref "RP4")
      (value "10K")
      (footprint "3296W_1")
      (description "Trimm Res TH 3/8  10K  0,5W  100ppm Vert Adj")
      (fields
        (field (name "MANUFACTURER PART NUMBER") "3296W-1-103LF")
        (field (name "MOUSER PART NUMBER") "652-3296W-1-103LF")
      )
      (libsource (lib "SssAccesDatbase") (part "Pot_1"))
    )
    (comp (ref "RP5")
      (value "1M")
      (footprint "3296W")
      (fields (field (name "PART NUMBER") "Pot. 3296W") (field (name "MANUFACTURER PART NUMBER") "???"))
      (libsource (lib "SssAccesDatbase") (part "Pot"))
    )
    (comp (ref "RP6")
      (value "1M")
      (footprint "3296W")
      (fields (field (name "PART NUMBER") "Pot. 3296W") (field (name "MANUFACTURER PART NUMBER") "???"))
      (libsource (lib "SssAccesDatbase") (part "Pot"))
    )
    (comp (ref "SB1")
      (value "PTS525SM15SMTR2 LFS")
      (footprint "TACT_SWITCH KPT1187B")
      (description "SWITCH TACTILE SPST-NO 0.02A 15V")
      (fields (field (name "DIGI-KEY PART NUMBER") "CKN9104CT-ND"))
      (libsource (lib "SssAccesDatbase") (part "TACT_SWITCH KPT1187B"))
    )
    (comp (ref "SB2")
      (value "PTS525SM15SMTR2 LFS")
      (footprint "TACT_SWITCH KPT1187B")
      (description "SWITCH TACTILE SPST-NO 0.02A 15V")
      (fields (field (name "DIGI-KEY PART NUMBER") "CKN9104CT-ND"))
      (libsource (lib "SssAccesDatbase") (part "TACT_SWITCH KPT1187B"))
    )
    (comp (ref "SB3")
      (value "PTS525SM15SMTR2 LFS")
      (footprint "TACT_SWITCH KPT1187B")
      (description "SWITCH TACTILE SPST-NO 0.02A 15V")
      (fields (field (name "DIGI-KEY PART NUMBER") "CKN9104CT-ND"))
      (libsource (lib "SssAccesDatbase") (part "TACT_SWITCH KPT1187B"))
    )
    (comp (ref "SB4")
      (value "PTS525SM15SMTR2 LFS")
      (footprint "TACT_SWITCH KPT1187B")
      (description "SWITCH TACTILE SPST-NO 0.02A 15V")
      (fields (field (name "DIGI-KEY PART NUMBER") "CKN9104CT-ND"))
      (libsource (lib "SssAccesDatbase") (part "TACT_SWITCH KPT1187B"))
    )
    (comp (ref "TP1")
      (value "TP(No BOM)")
      (footprint "PLLS1.27-1-R")
      (fields (field (name "PART NUMBER") "TP-PLLS1.27-1-R"))
      (libsource (lib "SssAccesDatbase") (part "TP(No BOM)"))
    )
    (comp (ref "VD1")
      (value "1N4148WSTR")
      (footprint "SOD323")
      (description "DIODE GEN PURP 75V 300MA SOD323")
      (fields
        (field (name "DIGI-KEY PART NUMBER") "1655-1359-1-ND")
        (field (name "MANUFACTURER PART NUMBER") "?")
        (field (name "PUBLISHER") "Altium Limited")
      )
      (libsource (lib "SssAccesDatbase") (part "Diode"))
    )
    (comp (ref "VD2")
      (value "1N4148WSTR")
      (footprint "SOD323")
      (description "DIODE GEN PURP 75V 300MA SOD323")
      (fields
        (field (name "DIGI-KEY PART NUMBER") "1655-1359-1-ND")
        (field (name "MANUFACTURER PART NUMBER") "?")
        (field (name "PUBLISHER") "Altium Limited")
      )
      (libsource (lib "SssAccesDatbase") (part "Diode"))
    )
    (comp (ref "VD3")
      (value "BAT54J")
      (footprint "SOD323")
      (description "Schottky Diode 30V 0,2A  SOD-323-2")
      (fields
        (field (name "MANUFACTURER PART NUMBER") "BAT54J,115")
        (field (name "MOUSER PART NUMBER") "771-BAT54J115")
        (field (name "PUBLISHER") "Altium Limited")
      )
      (libsource (lib "SssAccesDatbase") (part "Diode_C-A"))
    )
    (comp (ref "VD4")
      (value "BAT54J")
      (footprint "SOD323")
      (description "Schottky Diode 30V 0,2A  SOD-323-2")
      (fields
        (field (name "MANUFACTURER PART NUMBER") "BAT54J,115")
        (field (name "MOUSER PART NUMBER") "771-BAT54J115")
        (field (name "PUBLISHER") "Altium Limited")
      )
      (libsource (lib "SssAccesDatbase") (part "Diode_C-A"))
    )
    (comp (ref "VD5")
      (value "BAT54J")
      (footprint "SOD323")
      (description "Schottky Diode 30V 0,2A  SOD-323-2")
      (fields
        (field (name "MANUFACTURER PART NUMBER") "BAT54J,115")
        (field (name "MOUSER PART NUMBER") "771-BAT54J115")
        (field (name "PUBLISHER") "Altium Limited")
      )
      (libsource (lib "SssAccesDatbase") (part "Diode_C-A"))
    )
    (comp (ref "VT1")
      (value "IRLML6401PbF")
      (footprint "SOT23-3N")
      (fields (field (name "DIGI-KEY PART NUMBER") "???"))
      (libsource (lib "SssAccesDatbase") (part "TRANS-P-Channel-GDS"))
    )
    (comp (ref "VT2")
      (value "IRLML6401PbF")
      (footprint "SOT23-3N")
      (fields (field (name "DIGI-KEY PART NUMBER") "???"))
      (libsource (lib "SssAccesDatbase") (part "TRANS-P-Channel-GDS"))
    )
    (comp (ref "VT3")
      (value "BC848")
      (footprint "SOT23-3N")
      (description "TRANS NPN 30V 100MA SC70-3")
      (libsource (lib "SssAccesDatbase") (part "TRANS-NPN-BEC"))
    )
    (comp (ref "VT4")
      (value "BC848")
      (footprint "SOT23-3N")
      (libsource (lib "SssAccesDatbase") (part "TRANS-NPN-BEC"))
    )
    (comp (ref "VT5")
      (value "IRLML2502GTRPBF")
      (footprint "SOT23-3N")
      (description "N-Channel 50V 200mA (Ta) 350mW (Ta) Surface Mount SST3")
      (fields
        (field (name "PART NUMBER") "RUC002N05HZGT116")
        (field (name "DIGI-KEY PART NUMBER") "RUC002N05HZGT116CT-ND")
      )
      (libsource (lib "SssAccesDatbase") (part "TRANS-N-Channel-GSD"))
    )
    (comp (ref "VT6")
      (value "IRLML2244TRPBF")
      (footprint "SOT23-3N")
      (fields (field (name "PART NUMBER") "SI2347DS-T1-GE3"))
      (libsource (lib "SssAccesDatbase") (part "TRANS-P-Channel-GSD"))
    )
    (comp (ref "WA1")
      (value "INVERTED-F ANTENNA-MIFA  2,4Ghz")
      (footprint "INVERTED-F ANTENNA-MIFA")
      (libsource (lib "SssAccesDatbase") (part "WA_2pin_tie"))
    )
    (comp (ref "X1")
      (value "X1-PLS-1")
      (footprint "HoleSolderPLS-1")
      (description "контакт под пайку")
      (libsource (lib "SssAccesDatbase") (part "X1_1"))
    )
    (comp (ref "X2")
      (value "X1-PLS-1")
      (footprint "HoleSolderPLS-1")
      (description "контакт под пайку")
      (libsource (lib "SssAccesDatbase") (part "X1_1"))
    )
    (comp (ref "X3")
      (value "X1-PLS-1")
      (footprint "HoleSolderPLS-1")
      (description "контакт под пайку")
      (libsource (lib "SssAccesDatbase") (part "X1_1"))
    )
    (comp (ref "X4")
      (value "X1-PLS-1")
      (footprint "HoleSolderPLS-1")
      (description "контакт под пайку")
      (libsource (lib "SssAccesDatbase") (part "X1_1"))
    )
    (comp (ref "X5")
      (value "X1-PLS-1")
      (footprint "HoleSolderPLS-1")
      (description "контакт под пайку")
      (libsource (lib "SssAccesDatbase") (part "X1_1"))
    )
    (comp (ref "X6")
      (value "X1-PLS-1")
      (footprint "HoleSolderPLS-1")
      (description "контакт под пайку")
      (libsource (lib "SssAccesDatbase") (part "X1_1"))
    )
    (comp (ref "X7")
      (value "X1-PLS-1")
      (footprint "HoleSolderPLS-1")
      (description "контакт под пайку")
      (libsource (lib "SssAccesDatbase") (part "X1_1"))
    )
    (comp (ref "X8")
      (value "X1-PLS-1")
      (footprint "HoleSolderPLS-1")
      (description "контакт под пайку")
      (libsource (lib "SssAccesDatbase") (part "X1_1"))
    )
    (comp (ref "X9")
      (value "X1-PLS-1")
      (footprint "HoleSolderPLS-1")
      (description "контакт под пайку")
      (libsource (lib "SssAccesDatbase") (part "X1_1"))
    )
    (comp (ref "X10")
      (value "X1-PLS-1")
      (footprint "HoleSolderPLS-1")
      (description "контакт под пайку")
      (libsource (lib "SssAccesDatbase") (part "X1_1"))
    )
    (comp (ref "X11")
      (value "X1-PLS-1")
      (footprint "HoleSolderPLS-1")
      (description "контакт под пайку")
      (libsource (lib "SssAccesDatbase") (part "X1_1"))
    )
    (comp (ref "X12")
      (value "X1-PLS-1")
      (footprint "HoleSolderPLS-1")
      (description "контакт под пайку")
      (libsource (lib "SssAccesDatbase") (part "X1_1"))
    )
    (comp (ref "X13")
      (value "X1-PLS-1")
      (footprint "HoleSolderPLS-1")
      (description "контакт под пайку")
      (libsource (lib "SssAccesDatbase") (part "X1_1"))
    )
    (comp (ref "X14")
      (value "X1-PLS-1")
      (footprint "HoleSolderPLS-1")
      (description "контакт под пайку")
      (libsource (lib "SssAccesDatbase") (part "X1_1"))
    )
    (comp (ref "X15")
      (value "X1-PLS-1")
      (footprint "HoleSolderPLS-1")
      (description "контакт под пайку")
      (libsource (lib "SssAccesDatbase") (part "X1_1"))
    )
    (comp (ref "X16")
      (value "X1-PLS-1")
      (footprint "HoleSolderPLS-1")
      (description "контакт под пайку")
      (libsource (lib "SssAccesDatbase") (part "X1_1"))
    )
    (comp (ref "X17")
      (value "X1-PLS-1")
      (footprint "HoleSolderPLS-1")
      (description "контакт под пайку")
      (libsource (lib "SssAccesDatbase") (part "X1_1"))
    )
    (comp (ref "X18")
      (value "X1-PLS-1")
      (footprint "HoleSolderPLS-1")
      (description "контакт под пайку")
      (libsource (lib "SssAccesDatbase") (part "X1_1"))
    )
    (comp (ref "X19")
      (value "X1-PLS-1")
      (footprint "HoleSolderPLS-1")
      (description "контакт под пайку")
      (libsource (lib "SssAccesDatbase") (part "X1_1"))
    )
    (comp (ref "X20")
      (value "X1-PLS-1")
      (footprint "HoleSolderPLS-1")
      (description "контакт под пайку")
      (libsource (lib "SssAccesDatbase") (part "X1_1"))
    )
    (comp (ref "X21")
      (value "PLLS1.27-1-R")
      (footprint "PLLS1.27-1-R")
      (libsource (lib "SssAccesDatbase") (part "X1_1"))
    )
    (comp (ref "X22")
      (value "PLLS1.27-1-R")
      (footprint "PLLS1.27-1-R")
      (libsource (lib "SssAccesDatbase") (part "X1_1"))
    )
    (comp (ref "X23")
      (value "PLLS1.27-1-R")
      (footprint "PLLS1.27-1-R")
      (libsource (lib "SssAccesDatbase") (part "X1_1"))
    )
    (comp (ref "X24")
      (value "PLLS1.27-1-R")
      (footprint "PLLS1.27-1-R")
      (libsource (lib "SssAccesDatbase") (part "X1_1"))
    )
    (comp (ref "X25")
      (value "PLLS1.27-1-R")
      (footprint "PLLS1.27-1-R")
      (libsource (lib "SssAccesDatbase") (part "X1_1"))
    )
    (comp (ref "X26")
      (value "PLLS1.27-1-R")
      (footprint "PLLS1.27-1-R")
      (libsource (lib "SssAccesDatbase") (part "X1_1"))
    )
    (comp (ref "X27")
      (value "PLLS1.27-1-R")
      (footprint "PLLS1.27-1-R")
      (libsource (lib "SssAccesDatbase") (part "X1_1"))
    )
    (comp (ref "X28")
      (value "PLLS1.27-1-R")
      (footprint "PLLS1.27-1-R")
      (libsource (lib "SssAccesDatbase") (part "X1_1"))
    )
    (comp (ref "X29")
      (value "PLLS1.27-1-R")
      (footprint "PLLS1.27-1-R")
      (libsource (lib "SssAccesDatbase") (part "X1_1"))
    )
    (comp (ref "X30")
      (value "X1-PLS-1")
      (footprint "HoleSolderPLS-1")
      (description "контакт под пайку")
      (libsource (lib "SssAccesDatbase") (part "X1_1"))
    )
    (comp (ref "X31")
      (value "X1-PLS-1")
      (footprint "HoleSolderPLS-1")
      (description "контакт под пайку")
      (libsource (lib "SssAccesDatbase") (part "X1_1"))
    )
    (comp (ref "X32")
      (value "X1-PLS-1")
      (footprint "HoleSolderPLS-1")
      (description "контакт под пайку")
      (libsource (lib "SssAccesDatbase") (part "X1_1"))
    )
    (comp (ref "X33")
      (value "X1-PLS-1")
      (footprint "HoleSolderPLS-1")
      (description "контакт под пайку")
      (libsource (lib "SssAccesDatbase") (part "X1_1"))
    )
    (comp (ref "X34")
      (value "X1-PLS-1")
      (footprint "HoleSolderPLS-1")
      (description "контакт под пайку")
      (libsource (lib "SssAccesDatbase") (part "X1_1"))
    )
    (comp (ref "X35")
      (value "X1-PLS-1")
      (footprint "HoleSolderPLS-1")
      (description "контакт под пайку")
      (libsource (lib "SssAccesDatbase") (part "X1_1"))
    )
    (comp (ref "X36")
      (value "X1-PLS-1")
      (footprint "HoleSolderPLS-1")
      (description "контакт под пайку")
      (libsource (lib "SssAccesDatbase") (part "X1_1"))
    )
    (comp (ref "X37")
      (value "X1-PLS-1")
      (footprint "HoleSolderPLS-1")
      (description "контакт под пайку")
      (libsource (lib "SssAccesDatbase") (part "X1_1"))
    )
    (comp (ref "X38")
      (value "X1-PLS-1")
      (footprint "HoleSolderPLS-1")
      (description "контакт под пайку")
      (libsource (lib "SssAccesDatbase") (part "X1_1"))
    )
    (comp (ref "X39")
      (value "X1-PLS-1")
      (footprint "HoleSolderPLS-1")
      (description "контакт под пайку")
      (libsource (lib "SssAccesDatbase") (part "X1_1"))
    )
    (comp (ref "X40")
      (value "PLLS1.27-1-TOP-R")
      (footprint "PLLS1.27-1-TOP-R")
      (libsource (lib "SssAccesDatbase") (part "X1_1"))
    )
    (comp (ref "X41")
      (value "PLLS1.27-1-TOP-R")
      (footprint "PLLS1.27-1-TOP-R")
      (libsource (lib "SssAccesDatbase") (part "X1_1"))
    )
    (comp (ref "X42")
      (value "PLLS1.27-1-TOP-R")
      (footprint "PLLS1.27-1-TOP-R")
      (libsource (lib "SssAccesDatbase") (part "X1_1"))
    )
    (comp (ref "X43")
      (value "PLLS1.27-1-TOP-R")
      (footprint "PLLS1.27-1-TOP-R")
      (libsource (lib "SssAccesDatbase") (part "X1_1"))
    )
    (comp (ref "X44")
      (value "PLLS1.27-1-TOP-R")
      (footprint "PLLS1.27-1-TOP-R")
      (libsource (lib "SssAccesDatbase") (part "X1_1"))
    )
    (comp (ref "X45")
      (value "PLLS1.27-1-TOP-R")
      (footprint "PLLS1.27-1-TOP-R")
      (libsource (lib "SssAccesDatbase") (part "X1_1"))
    )
    (comp (ref "X46")
      (value "PLLS1.27-1-TOP-R")
      (footprint "PLLS1.27-1-TOP-R")
      (libsource (lib "SssAccesDatbase") (part "X1_1"))
    )
    (comp (ref "X47")
      (value "PLLS1.27-1-TOP-R")
      (footprint "PLLS1.27-1-TOP-R")
      (libsource (lib "SssAccesDatbase") (part "X1_1"))
    )
    (comp (ref "X48")
      (value "PLLS1.27-1-TOP-R")
      (footprint "PLLS1.27-1-TOP-R")
      (libsource (lib "SssAccesDatbase") (part "X1_1"))
    )
    (comp (ref "X49")
      (value "PLLS1.27-1-R")
      (footprint "PLLS1.27-1-R")
      (libsource (lib "SssAccesDatbase") (part "X1_1"))
    )
    (comp (ref "X50")
      (value "PLLS1.27-1-R")
      (footprint "PLLS1.27-1-R")
      (libsource (lib "SssAccesDatbase") (part "X1_1"))
    )
    (comp (ref "X51")
      (value "PLLS1.27-1-R")
      (footprint "PLLS1.27-1-R")
      (libsource (lib "SssAccesDatbase") (part "X1_1"))
    )
    (comp (ref "X52")
      (value "X1-PLS-1")
      (footprint "HoleSolderPLS-1")
      (description "контакт под пайку")
      (libsource (lib "SssAccesDatbase") (part "X1_1"))
    )
    (comp (ref "X53")
      (value "X1-PLS-1")
      (footprint "HoleSolderPLS-1")
      (description "контакт под пайку")
      (libsource (lib "SssAccesDatbase") (part "X1_1"))
    )
    (comp (ref "X54")
      (value "X1-PLS-1")
      (footprint "HoleSolderPLS-1")
      (description "контакт под пайку")
      (libsource (lib "SssAccesDatbase") (part "X1_1"))
    )
    (comp (ref "X55")
      (value "X1-PLS-1")
      (footprint "HoleSolderPLS-1")
      (description "контакт под пайку")
      (libsource (lib "SssAccesDatbase") (part "X1_1"))
    )
    (comp (ref "X56")
      (value "PLLS1.27-1-R")
      (footprint "PLLS1.27-1-R")
      (libsource (lib "SssAccesDatbase") (part "X1_1"))
    )
    (comp (ref "X57")
      (value "PLLS1.27-1-R")
      (footprint "PLLS1.27-1-R")
      (libsource (lib "SssAccesDatbase") (part "X1_1"))
    )
    (comp (ref "X58")
      (value "PLLS1.27-1-R")
      (footprint "PLLS1.27-1-R")
      (libsource (lib "SssAccesDatbase") (part "X1_1"))
    )
    (comp (ref "X59")
      (value "PLLS1.27-1-R")
      (footprint "PLLS1.27-1-R")
      (libsource (lib "SssAccesDatbase") (part "X1_1"))
    )
    (comp (ref "X60")
      (value "PLLS1.27-1-R")
      (footprint "PLLS1.27-1-R")
      (libsource (lib "SssAccesDatbase") (part "X1_1"))
    )
    (comp (ref "X61")
      (value "PLLS1.27-1-R")
      (footprint "PLLS1.27-1-R")
      (libsource (lib "SssAccesDatbase") (part "X1_1"))
    )
    (comp (ref "X62")
      (value "X1-PLS-1")
      (footprint "HoleSolderPLS-1")
      (description "контакт под пайку")
      (libsource (lib "SssAccesDatbase") (part "X1_1"))
    )
    (comp (ref "X63")
      (value "X1-PLS-1")
      (footprint "HoleSolderPLS-1")
      (description "контакт под пайку")
      (libsource (lib "SssAccesDatbase") (part "X1_1"))
    )
    (comp (ref "X64")
      (value "X1-PLS-1")
      (footprint "HoleSolderPLS-1")
      (description "контакт под пайку")
      (libsource (lib "SssAccesDatbase") (part "X1_1"))
    )
    (comp (ref "X65")
      (value "X1-PLS-1")
      (footprint "HoleSolderPLS-1")
      (description "контакт под пайку")
      (libsource (lib "SssAccesDatbase") (part "X1_1"))
    )
    (comp (ref "X66")
      (value "X1-PLS-1")
      (footprint "HoleSolderPLS-1")
      (description "контакт под пайку")
      (libsource (lib "SssAccesDatbase") (part "X1_1"))
    )
    (comp (ref "X67")
      (value "X1-PLS-1")
      (footprint "HoleSolderPLS-1")
      (description "контакт под пайку")
      (libsource (lib "SssAccesDatbase") (part "X1_1"))
    )
    (comp (ref "X68")
      (value "X1-PLS-1")
      (footprint "HoleSolderPLS-1")
      (description "контакт под пайку")
      (libsource (lib "SssAccesDatbase") (part "X1_1"))
    )
    (comp (ref "X69")
      (value "X1-PLS-1")
      (footprint "HoleSolderPLS-1")
      (description "контакт под пайку")
      (libsource (lib "SssAccesDatbase") (part "X1_1"))
    )
    (comp (ref "X70")
      (value "X1-PLS-1")
      (footprint "HoleSolderPLS-1")
      (description "контакт под пайку")
      (libsource (lib "SssAccesDatbase") (part "X1_1"))
    )
    (comp (ref "X71")
      (value "X1-PLS-1")
      (footprint "HoleSolderPLS-1")
      (description "контакт под пайку")
      (libsource (lib "SssAccesDatbase") (part "X1_1"))
    )
    (comp (ref "X72")
      (value "X1-PLS-1")
      (footprint "HoleSolderPLS-1")
      (description "контакт под пайку")
      (libsource (lib "SssAccesDatbase") (part "X1_1"))
    )
    (comp (ref "X73")
      (value "X1-PLS-1")
      (footprint "HoleSolderPLS-1")
      (description "контакт под пайку")
      (libsource (lib "SssAccesDatbase") (part "X1_1"))
    )
    (comp (ref "X74")
      (value "PLLS1.27-1-R")
      (footprint "PLLS1.27-1-R")
      (libsource (lib "SssAccesDatbase") (part "X1_1"))
    )
    (comp (ref "X75")
      (value "PLLS1.27-1-R")
      (footprint "PLLS1.27-1-R")
      (libsource (lib "SssAccesDatbase") (part "X1_1"))
    )
    (comp (ref "X76")
      (value "PLLS1.27-1-R")
      (footprint "PLLS1.27-1-R")
      (libsource (lib "SssAccesDatbase") (part "X1_1"))
    )
    (comp (ref "X77")
      (value "PLLS1.27-1-R")
      (footprint "PLLS1.27-1-R")
      (libsource (lib "SssAccesDatbase") (part "X1_1"))
    )
    (comp (ref "XP1")
      (value "PLS-2_Jump")
      (footprint "PLS-2-3D")
      (description "CONN HEADER VERT 2POS 2.54MM")
      (fields
        (field (name "DIGI-KEY PART NUMBER") "S1011EC-02-ND")
        (field (name "MANUFACTURER PART NUMBER") "PRPC002SAAN-RC")
      )
      (libsource (lib "SssAccesDatbase") (part "XP-2_Jump"))
    )
    (comp (ref "XP2")
      (value "PLS-2_Jump")
      (footprint "PLS-2-3D")
      (description "CONN HEADER VERT 2POS 2.54MM")
      (fields
        (field (name "DIGI-KEY PART NUMBER") "S1011EC-02-ND")
        (field (name "MANUFACTURER PART NUMBER") "PRPC002SAAN-RC")
      )
      (libsource (lib "SssAccesDatbase") (part "XP-2_Jump"))
    )
    (comp (ref "XP3")
      (value "PLS-2_Jump")
      (footprint "PLS-2-3D")
      (description "CONN HEADER VERT 2POS 2.54MM")
      (fields
        (field (name "DIGI-KEY PART NUMBER") "S1011EC-02-ND")
        (field (name "MANUFACTURER PART NUMBER") "PRPC002SAAN-RC")
      )
      (libsource (lib "SssAccesDatbase") (part "XP-2_Jump"))
    )
    (comp (ref "XP4")
      (value "PLS-3")
      (footprint "PLS-3-3D")
      (description "CONN HEADER VERT 3POS 2.54MM")
      (fields (field (name "PART NUMBER") "PR20203VBNN") (field (name "DIGI-KEY PART NUMBER") "1849-1003-ND"))
      (libsource (lib "SssAccesDatbase") (part "XP-3_Jump"))
    )
    (comp (ref "XP5")
      (value "PLS-2_Jump")
      (footprint "PLS-2-3D")
      (description "CONN HEADER VERT 2POS 2.54MM")
      (fields
        (field (name "DIGI-KEY PART NUMBER") "S1011EC-02-ND")
        (field (name "MANUFACTURER PART NUMBER") "PRPC002SAAN-RC")
      )
      (libsource (lib "SssAccesDatbase") (part "XP-2_Jump"))
    )
    (comp (ref "XP6")
      (value "PLS-3")
      (footprint "PLS-3-3D")
      (description "CONN HEADER VERT 3POS 2.54MM")
      (fields
        (field (name "DIGI-KEY PART NUMBER") "1849-1003-ND")
        (field (name "MANUFACTURER PART NUMBER") "PR20203VBNN")
      )
      (libsource (lib "SssAccesDatbase") (part "XP-3"))
    )
    (comp (ref "XP7")
      (value "PLS-2_Jump")
      (footprint "PLS-2-3D")
      (description "CONN HEADER VERT 2POS 2.54MM")
      (fields
        (field (name "DIGI-KEY PART NUMBER") "S1011EC-02-ND")
        (field (name "MANUFACTURER PART NUMBER") "PRPC002SAAN-RC")
      )
      (libsource (lib "SssAccesDatbase") (part "XP-2_Jump"))
    )
    (comp (ref "XP8")
      (value "PLS-2_Jump")
      (footprint "PLS-2-3D")
      (description "CONN HEADER VERT 2POS 2.54MM")
      (fields
        (field (name "DIGI-KEY PART NUMBER") "S1011EC-02-ND")
        (field (name "MANUFACTURER PART NUMBER") "PRPC002SAAN-RC")
      )
      (libsource (lib "SssAccesDatbase") (part "XP-2_Jump"))
    )
    (comp (ref "XP9")
      (value "PLS-3")
      (footprint "PLS-3-3D")
      (description "CONN HEADER VERT 3POS 2.54MM")
      (fields (field (name "PART NUMBER") "PR20203VBNN") (field (name "DIGI-KEY PART NUMBER") "1849-1003-ND"))
      (libsource (lib "SssAccesDatbase") (part "XP-3_Jump"))
    )
    (comp (ref "XP10")
      (value "PLS-2_Jump")
      (footprint "PLS-2-3D")
      (description "CONN HEADER VERT 2POS 2.54MM")
      (fields
        (field (name "DIGI-KEY PART NUMBER") "S1011EC-02-ND")
        (field (name "MANUFACTURER PART NUMBER") "PRPC002SAAN-RC")
      )
      (libsource (lib "SssAccesDatbase") (part "XP-2_Jump"))
    )
    (comp (ref "XP11")
      (value "3220-10-0100-00 edge")
      (footprint "IPS 10(1.27)edge")
      (description "3220-10-0100-00")
      (fields (field (name "DIGI-KEY PART NUMBER") "1175-1627-ND"))
      (libsource (lib "SssAccesDatbase") (part "XP-10"))
    )
    (comp (ref "XP12")
      (value "PLS-1")
      (footprint "PLS-1-3D")
      (description "CONN HEADER VERT 1POS")
      (fields
        (field (name "DIGI-KEY PART NUMBER") "S1011EC-01-ND")
        (field (name "MANUFACTURER PART NUMBER") "PRPC001SAAN-RC")
      )
      (libsource (lib "SssAccesDatbase") (part "XP-1_1"))
    )
    (comp (ref "XP13")
      (value "PLS-1")
      (footprint "PLS-1-3D")
      (description "CONN HEADER VERT 1POS")
      (fields
        (field (name "DIGI-KEY PART NUMBER") "S1011EC-01-ND")
        (field (name "MANUFACTURER PART NUMBER") "PRPC001SAAN-RC")
      )
      (libsource (lib "SssAccesDatbase") (part "XP-1_1"))
    )
    (comp (ref "XP14")
      (value "PLS-1")
      (footprint "PLS-1-3D")
      (description "CONN HEADER VERT 1POS")
      (fields
        (field (name "DIGI-KEY PART NUMBER") "S1011EC-01-ND")
        (field (name "MANUFACTURER PART NUMBER") "PRPC001SAAN-RC")
      )
      (libsource (lib "SssAccesDatbase") (part "XP-1_1"))
    )
    (comp (ref "XP15")
      (value "PLS-1")
      (footprint "PLS-1-3D")
      (description "CONN HEADER VERT 1POS")
      (fields
        (field (name "DIGI-KEY PART NUMBER") "S1011EC-01-ND")
        (field (name "MANUFACTURER PART NUMBER") "PRPC001SAAN-RC")
      )
      (libsource (lib "SssAccesDatbase") (part "XP-1_1"))
    )
    (comp (ref "XP16")
      (value "PLS-1")
      (footprint "PLS-1-3D")
      (description "CONN HEADER VERT 1POS")
      (fields
        (field (name "DIGI-KEY PART NUMBER") "S1011EC-01-ND")
        (field (name "MANUFACTURER PART NUMBER") "PRPC001SAAN-RC")
      )
      (libsource (lib "SssAccesDatbase") (part "XP-1_1"))
    )
    (comp (ref "XP17")
      (value "PLS-1")
      (footprint "PLS-1-3D")
      (description "CONN HEADER VERT 1POS")
      (fields
        (field (name "DIGI-KEY PART NUMBER") "S1011EC-01-ND")
        (field (name "MANUFACTURER PART NUMBER") "PRPC001SAAN-RC")
      )
      (libsource (lib "SssAccesDatbase") (part "XP-1_1"))
    )
    (comp (ref "XP18")
      (value "PLS-1")
      (footprint "PLS-1-3D")
      (description "CONN HEADER VERT 1POS")
      (fields
        (field (name "DIGI-KEY PART NUMBER") "S1011EC-01-ND")
        (field (name "MANUFACTURER PART NUMBER") "PRPC001SAAN-RC")
      )
      (libsource (lib "SssAccesDatbase") (part "XP-1_1"))
    )
    (comp (ref "XP19")
      (value "PLS-1")
      (footprint "PLS-1-3D")
      (description "CONN HEADER VERT 1POS")
      (fields
        (field (name "DIGI-KEY PART NUMBER") "S1011EC-01-ND")
        (field (name "MANUFACTURER PART NUMBER") "PRPC001SAAN-RC")
      )
      (libsource (lib "SssAccesDatbase") (part "XP-1_1"))
    )
    (comp (ref "XP20")
      (value "PLS-1")
      (footprint "PLS-1-3D")
      (description "CONN HEADER VERT 1POS")
      (fields
        (field (name "DIGI-KEY PART NUMBER") "S1011EC-01-ND")
        (field (name "MANUFACTURER PART NUMBER") "PRPC001SAAN-RC")
      )
      (libsource (lib "SssAccesDatbase") (part "XP-1_1"))
    )
    (comp (ref "XP21")
      (value "PLS-1")
      (footprint "PLS-1-3D")
      (description "CONN HEADER VERT 1POS")
      (fields
        (field (name "DIGI-KEY PART NUMBER") "S1011EC-01-ND")
        (field (name "MANUFACTURER PART NUMBER") "PRPC001SAAN-RC")
      )
      (libsource (lib "SssAccesDatbase") (part "XP-1_1"))
    )
    (comp (ref "XP22")
      (value "PLS-1")
      (footprint "PLS-1-3D")
      (description "CONN HEADER VERT 1POS")
      (fields
        (field (name "DIGI-KEY PART NUMBER") "S1011EC-01-ND")
        (field (name "MANUFACTURER PART NUMBER") "PRPC001SAAN-RC")
      )
      (libsource (lib "SssAccesDatbase") (part "XP-1_1"))
    )
    (comp (ref "XP23")
      (value "0530480210")
      (footprint "0530480210")
      (description "CONN HEADER R/A 2POS 1.25MM")
      (fields (field (name "DIGI-KEY PART NUMBER") "WM1742-ND"))
      (libsource (lib "SssAccesDatbase") (part "XP-2"))
    )
    (comp (ref "XP24")
      (value "PLS-1")
      (footprint "PLS-1-3D")
      (description "CONN HEADER VERT 1POS")
      (fields
        (field (name "DIGI-KEY PART NUMBER") "S1011EC-01-ND")
        (field (name "MANUFACTURER PART NUMBER") "PRPC001SAAN-RC")
      )
      (libsource (lib "SssAccesDatbase") (part "XP-1_1"))
    )
    (comp (ref "XP25")
      (value "PLS-1")
      (footprint "PLS-1-3D")
      (description "CONN HEADER VERT 1POS")
      (fields
        (field (name "DIGI-KEY PART NUMBER") "S1011EC-01-ND")
        (field (name "MANUFACTURER PART NUMBER") "PRPC001SAAN-RC")
      )
      (libsource (lib "SssAccesDatbase") (part "XP-1_1"))
    )
    (comp (ref "XP26")
      (value "PLS-1")
      (footprint "PLS-1-3D")
      (description "CONN HEADER VERT 1POS")
      (fields
        (field (name "DIGI-KEY PART NUMBER") "S1011EC-01-ND")
        (field (name "MANUFACTURER PART NUMBER") "PRPC001SAAN-RC")
      )
      (libsource (lib "SssAccesDatbase") (part "XP-1_1"))
    )
    (comp (ref "XP27")
      (value "PLS-1")
      (footprint "PLS-1-3D")
      (description "CONN HEADER VERT 1POS")
      (fields
        (field (name "DIGI-KEY PART NUMBER") "S1011EC-01-ND")
        (field (name "MANUFACTURER PART NUMBER") "PRPC001SAAN-RC")
      )
      (libsource (lib "SssAccesDatbase") (part "XP-1_1"))
    )
    (comp (ref "XP28")
      (value "PLS-1")
      (footprint "PLS-1-3D")
      (description "CONN HEADER VERT 1POS")
      (fields
        (field (name "DIGI-KEY PART NUMBER") "S1011EC-01-ND")
        (field (name "MANUFACTURER PART NUMBER") "PRPC001SAAN-RC")
      )
      (libsource (lib "SssAccesDatbase") (part "XP-1_1"))
    )
    (comp (ref "XP29")
      (value "PLS-1")
      (footprint "PLS-1-3D")
      (description "CONN HEADER VERT 1POS")
      (fields
        (field (name "DIGI-KEY PART NUMBER") "S1011EC-01-ND")
        (field (name "MANUFACTURER PART NUMBER") "PRPC001SAAN-RC")
      )
      (libsource (lib "SssAccesDatbase") (part "XP-1_1"))
    )
    (comp (ref "XP30")
      (value "PLS-1")
      (footprint "PLS-1-3D")
      (description "CONN HEADER VERT 1POS")
      (fields
        (field (name "DIGI-KEY PART NUMBER") "S1011EC-01-ND")
        (field (name "MANUFACTURER PART NUMBER") "PRPC001SAAN-RC")
      )
      (libsource (lib "SssAccesDatbase") (part "XP-1_1"))
    )
    (comp (ref "XP31")
      (value "PLS-1")
      (footprint "PLS-1-3D")
      (description "CONN HEADER VERT 1POS")
      (fields
        (field (name "DIGI-KEY PART NUMBER") "S1011EC-01-ND")
        (field (name "MANUFACTURER PART NUMBER") "PRPC001SAAN-RC")
      )
      (libsource (lib "SssAccesDatbase") (part "XP-1_1"))
    )
    (comp (ref "XP32")
      (value "PLS-1")
      (footprint "PLS-1-3D")
      (description "CONN HEADER VERT 1POS")
      (fields
        (field (name "DIGI-KEY PART NUMBER") "S1011EC-01-ND")
        (field (name "MANUFACTURER PART NUMBER") "PRPC001SAAN-RC")
      )
      (libsource (lib "SssAccesDatbase") (part "XP-1_1"))
    )
    (comp (ref "XP33")
      (value "PLS-1")
      (footprint "PLS-1-3D")
      (description "CONN HEADER VERT 1POS")
      (fields
        (field (name "DIGI-KEY PART NUMBER") "S1011EC-01-ND")
        (field (name "MANUFACTURER PART NUMBER") "PRPC001SAAN-RC")
      )
      (libsource (lib "SssAccesDatbase") (part "XP-1_1"))
    )
    (comp (ref "XP34")
      (value "PLS-1")
      (footprint "PLS-1-3D")
      (description "CONN HEADER VERT 1POS")
      (fields
        (field (name "DIGI-KEY PART NUMBER") "S1011EC-01-ND")
        (field (name "MANUFACTURER PART NUMBER") "PRPC001SAAN-RC")
      )
      (libsource (lib "SssAccesDatbase") (part "XP-1_1"))
    )
    (comp (ref "XP35")
      (value "PLS-1")
      (footprint "PLS-1-3D")
      (description "CONN HEADER VERT 1POS")
      (fields
        (field (name "DIGI-KEY PART NUMBER") "S1011EC-01-ND")
        (field (name "MANUFACTURER PART NUMBER") "PRPC001SAAN-RC")
      )
      (libsource (lib "SssAccesDatbase") (part "XP-1_1"))
    )
    (comp (ref "XP36")
      (value "PLS-1")
      (footprint "PLS-1-3D")
      (description "CONN HEADER VERT 1POS")
      (fields
        (field (name "DIGI-KEY PART NUMBER") "S1011EC-01-ND")
        (field (name "MANUFACTURER PART NUMBER") "PRPC001SAAN-RC")
      )
      (libsource (lib "SssAccesDatbase") (part "XP-1_1"))
    )
    (comp (ref "XP37")
      (value "PLS-1")
      (footprint "PLS-1-3D")
      (description "CONN HEADER VERT 1POS")
      (fields
        (field (name "DIGI-KEY PART NUMBER") "S1011EC-01-ND")
        (field (name "MANUFACTURER PART NUMBER") "PRPC001SAAN-RC")
      )
      (libsource (lib "SssAccesDatbase") (part "XP-1_1"))
    )
    (comp (ref "XP38")
      (value "PLS-1")
      (footprint "PLS-1-3D")
      (description "CONN HEADER VERT 1POS")
      (fields
        (field (name "DIGI-KEY PART NUMBER") "S1011EC-01-ND")
        (field (name "MANUFACTURER PART NUMBER") "PRPC001SAAN-RC")
      )
      (libsource (lib "SssAccesDatbase") (part "XP-1_1"))
    )
    (comp (ref "XP39")
      (value "PLS-1")
      (footprint "PLS-1-3D")
      (description "CONN HEADER VERT 1POS")
      (fields
        (field (name "DIGI-KEY PART NUMBER") "S1011EC-01-ND")
        (field (name "MANUFACTURER PART NUMBER") "PRPC001SAAN-RC")
      )
      (libsource (lib "SssAccesDatbase") (part "XP-1_1"))
    )
    (comp (ref "XP40")
      (value "PLS-1")
      (footprint "PLS-1-3D")
      (description "CONN HEADER VERT 1POS")
      (fields
        (field (name "DIGI-KEY PART NUMBER") "S1011EC-01-ND")
        (field (name "MANUFACTURER PART NUMBER") "PRPC001SAAN-RC")
      )
      (libsource (lib "SssAccesDatbase") (part "XP-1_1"))
    )
    (comp (ref "XP41")
      (value "PLS-2_Jump")
      (footprint "PLS-2-3D")
      (description "CONN HEADER VERT 2POS 2.54MM")
      (fields
        (field (name "DIGI-KEY PART NUMBER") "S1011EC-02-ND")
        (field (name "MANUFACTURER PART NUMBER") "PRPC002SAAN-RC")
      )
      (libsource (lib "SssAccesDatbase") (part "XP-2_Jump"))
    )
    (comp (ref "XS1")
      (value "10118193-0001LF")
      (footprint "10118193-0001LF")
      (description "CONN RCPT USB2.0 MICRO B SMD R/A")
      (fields (field (name "DIGI-KEY PART NUMBER") "609-4616-1-ND"))
      (libsource (lib "SssAccesDatbase") (part "Micro USB"))
    )
    (comp (ref "XS3")
      (value "10118193-0001LF")
      (footprint "10118193-0001LF")
      (description "CONN RCPT USB2.0 MICRO B SMD R/A")
      (fields (field (name "DIGI-KEY PART NUMBER") "609-4616-1-ND"))
      (libsource (lib "SssAccesDatbase") (part "Micro USB"))
    )
    (comp (ref "XS4")
      (value "PBS-7")
      (footprint "PBS-7-3D")
      (libsource (lib "SssAccesDatbase") (part "XS-7"))
    )
    (comp (ref "XS5")
      (value "10118194-0001LF")
      (footprint "MICRO_USB _B")
      (description "USB Connectors 5P MICRO USB TYPE B RCPT W/ REAR PEGS")
      (fields
        (field (name "DIGI-KEY PART NUMBER") "609-4618-1-ND")
        (field (name "MOUSER PART NUMBER") "649-10118194-0001LF")
      )
      (libsource (lib "SssAccesDatbase") (part "Micro USB"))
    )
    (comp (ref "XT")
      (value "3pin 3,5mm")
      (footprint "1984620")
      (description "TERM BLK 3POS SIDE ENT 3.5MM PCB")
      (fields (field (name "PART NUMBER") "1984620") (field (name "DIGI-KEY PART NUMBER") "277-1722-ND"))
      (libsource (lib "") (part "XT-3_1"))
    )
    (comp (ref "XT1")
      (value "3pin 3,5mm")
      (footprint "1984620")
      (description "TERM BLK 3POS SIDE ENT 3.5MM PCB")
      (fields (field (name "PART NUMBER") "1984620") (field (name "DIGI-KEY PART NUMBER") "277-1722-ND"))
      (libsource (lib "SssAccesDatbase") (part "XT-3"))
    )
    (comp (ref "XT2")
      (value "3pin 3,5mm")
      (footprint "1984620")
      (description "TERM BLK 3POS SIDE ENT 3.5MM PCB")
      (fields (field (name "PART NUMBER") "1984620") (field (name "DIGI-KEY PART NUMBER") "277-1722-ND"))
      (libsource (lib "") (part "XT-3_1"))
    )
    (comp (ref "XT3")
      (value "3pin 3,5mm")
      (footprint "1984620")
      (description "TERM BLK 3POS SIDE ENT 3.5MM PCB")
      (fields (field (name "PART NUMBER") "1984620") (field (name "DIGI-KEY PART NUMBER") "277-1722-ND"))
      (libsource (lib "") (part "XT-3_1"))
    )
    (comp (ref "XT4")
      (value "2pos5mm")
      (footprint "691137710002")
      (description "TERM BLK 2POS SIDE ENTRY 5MM PCB")
      (fields
        (field (name "PART NUMBER") "691137710002")
        (field (name "DIGI-KEY PART NUMBER") "732-10955-ND")
      )
      (libsource (lib "SssAccesDatbase") (part "XT-2"))
    )
    (comp (ref "XT5")
      (value "2pos5mm")
      (footprint "691137710002")
      (description "TERM BLK 2POS SIDE ENTRY 5MM PCB")
      (fields
        (field (name "PART NUMBER") "691137710002")
        (field (name "DIGI-KEY PART NUMBER") "732-10955-ND")
      )
      (libsource (lib "SssAccesDatbase") (part "XT-2"))
    )
    (comp (ref "ZL1")
      (value "600Ohms@100MHz")
      (footprint "Ferrite1005(0402)")
      (description "FERRITE BEAD 600 OHM 0402 1LN")
      (fields
        (field (name "PART NUMBER") "MMZ1005S601CT000")
        (field (name "DIGI-KEY PART NUMBER") "445-2162-1-ND")
      )
      (libsource (lib "") (part "ZL_1"))
    )
    (comp (ref "ZL2")
      (value "600Ohms@100MHz")
      (footprint "Ferrite1005(0402)")
      (description "FERRITE BEAD 600 OHM 0402 1LN")
      (fields
        (field (name "PART NUMBER") "MMZ1005S601CT000")
        (field (name "DIGI-KEY PART NUMBER") "445-2162-1-ND")
      )
      (libsource (lib "") (part "ZL_1"))
    )
    (comp (ref "ZL3")
      (value "470Ohms@100MHz")
      (footprint "Ferrite1005(0402)")
      (description "FERRITE BEAD 470 OHM 0402 1LN")
      (fields
        (field (name "PART NUMBER") "Ferrite1005(0402)")
        (field (name "MANUFACTURER PART NUMBER") "BLM15PX471SN1D")
      )
      (libsource (lib "SssAccesDatbase") (part "ZL"))
    )
    (comp (ref "ZL4")
      (value "BLM15PX471SN1D")
      (footprint "Ferrite1005(0402)")
      (description "FERRITE BEAD 470 OHM 0402 1LN")
      (fields
        (field (name "PART NUMBER") "Ferrite1005(0402)")
        (field (name "DIGI-KEY PART NUMBER") "490-10662-1-ND")
      )
      (libsource (lib "SssAccesDatbase") (part "ZL"))
    )
    (comp (ref "ZL5")
      (value "470Ohms@100MHz")
      (footprint "Ferrite1005(0402)")
      (description "FERRITE BEAD 470 OHM 0402 1LN")
      (fields
        (field (name "PART NUMBER") "Ferrite1005(0402)")
        (field (name "MANUFACTURER PART NUMBER") "BLM15PX471SN1D")
      )
      (libsource (lib "SssAccesDatbase") (part "ZL"))
    )
  )
  (nets
    (net (code "1") (name "+3.3V") (class "Default")
      (node (ref "C30") (pin "1") (pinfunction "1_1") (pintype "passive"))
      (node (ref "DA1") (pin "5") (pinfunction "VOUT_5") (pintype "passive"))
      (node (ref "DA5") (pin "5") (pinfunction "VOUT_5") (pintype "passive"))
      (node (ref "DD4") (pin "2") (pinfunction "SDx_2") (pintype "passive"))
      (node (ref "DD4") (pin "3") (pinfunction "SCx_3") (pintype "passive"))
      (node (ref "DD4") (pin "5") (pinfunction "VDDIO_5") (pintype "power_in"))
      (node (ref "R2") (pin "2") (pinfunction "2_2") (pintype "passive"))
      (node (ref "R20") (pin "2") (pinfunction "2_2") (pintype "passive"))
      (node (ref "R36") (pin "1") (pinfunction "1_1") (pintype "passive"))
      (node (ref "X29") (pin "1") (pinfunction "1_1") (pintype "passive"))
      (node (ref "ZL3") (pin "1") (pinfunction "1_1") (pintype "passive"))
    )
    (net (code "2") (name "+5V") (class "Default")
      (node (ref "C11") (pin "2") (pinfunction "2_2") (pintype "passive"))
      (node (ref "C44") (pin "2") (pinfunction "2_2") (pintype "passive"))
      (node (ref "C46") (pin "2") (pinfunction "2_2") (pintype "passive"))
      (node (ref "C6") (pin "2") (pinfunction "2_2") (pintype "passive"))
      (node (ref "DA1") (pin "1") (pinfunction "VIN_1") (pintype "passive"))
      (node (ref "DA4") (pin "4") (pinfunction "VDD_4") (pintype "passive"))
      (node (ref "DA7") (pin "4") (pinfunction "VDD_4") (pintype "passive"))
      (node (ref "DD6") (pin "10") (pinfunction "VCC_10") (pintype "power_in"))
      (node (ref "R15") (pin "2") (pinfunction "2_2") (pintype "passive"))
      (node (ref "R39") (pin "2") (pinfunction "2_2") (pintype "passive"))
      (node (ref "R4") (pin "2") (pinfunction "2_2") (pintype "passive"))
      (node (ref "VD1") (pin "1") (pintype "passive"))
      (node (ref "VD2") (pin "1") (pintype "passive"))
      (node (ref "VT1") (pin "1") (pinfunction "G_1") (pintype "passive"))
      (node (ref "VT2") (pin "1") (pinfunction "G_1") (pintype "passive"))
      (node (ref "X58") (pin "1") (pinfunction "1_1") (pintype "passive"))
      (node (ref "XP25") (pin "1") (pinfunction "1_1") (pintype "passive"))
      (node (ref "XS4") (pin "2") (pinfunction "2_2") (pintype "passive"))
      (node (ref "XS5") (pin "1") (pinfunction "1_1") (pintype "passive"))
    )
    (net (code "3") (name "/Bat") (class "Default")
      (node (ref "DA7") (pin "3") (pinfunction "VBAT_3") (pintype "passive"))
      (node (ref "VT1") (pin "2") (pinfunction "D_2") (pintype "passive"))
      (node (ref "X56") (pin "1") (pinfunction "1_1") (pintype "passive"))
    )
    (net (code "4") (name "/BlueHCI_RX") (class "Default")
      (node (ref "DD3") (pin "12") (pinfunction "UART_RXD_12") (pintype "passive"))
      (node (ref "R10") (pin "2") (pinfunction "2_2") (pintype "passive"))
      (node (ref "XP6") (pin "3") (pinfunction "3_3") (pintype "passive"))
    )
    (net (code "5") (name "/BlueHCI_Recovery") (class "Default")
      (node (ref "DD3") (pin "15") (pinfunction "SDA_15") (pintype "passive"))
      (node (ref "DD5") (pin "5") (pinfunction "SI/SIO0_5") (pintype "passive"))
      (node (ref "SB1") (pin "2") (pinfunction "NO_2") (pintype "passive"))
    )
    (net (code "6") (name "/BlueHCI_TX") (class "Default")
      (node (ref "DD3") (pin "13") (pinfunction "UART_TXD_13") (pintype "passive"))
      (node (ref "XP6") (pin "2") (pinfunction "2_2") (pintype "passive"))
    )
    (net (code "7") (name "/BlueHCI_nReset") (class "Default")
      (node (ref "DD3") (pin "18") (pinfunction "RST_N_18") (pintype "passive"))
      (node (ref "R20") (pin "1") (pinfunction "1_1") (pintype "passive"))
      (node (ref "SB2") (pin "2") (pinfunction "NO_2") (pintype "passive"))
    )
    (net (code "8") (name "/Blue_PUART_RX") (class "Default")
      (node (ref "DD3") (pin "19") (pinfunction "P0_19") (pintype "passive"))
      (node (ref "XS4") (pin "6") (pinfunction "6_6") (pintype "passive"))
    )
    (net (code "9") (name "/Blue_PUART_TX") (class "Default")
      (node (ref "DD3") (pin "23") (pinfunction "P4_23") (pintype "passive"))
      (node (ref "XS4") (pin "7") (pinfunction "7_7") (pintype "passive"))
    )
    (net (code "10") (name "/But") (class "Default")
      (node (ref "DD7") (pin "2") (pinfunction "PA00/XIN32_2") (pintype "bidirectional"))
      (node (ref "SB4") (pin "1") (pinfunction "COMMON_1") (pintype "passive"))
      (node (ref "XP17") (pin "1") (pinfunction "1_1") (pintype "passive"))
    )
    (net (code "11") (name "/MCU_RX") (class "Default")
      (node (ref "DD6") (pin "15") (pinfunction "TXD_15") (pintype "output"))
      (node (ref "DD7") (pin "6") (pinfunction "PA04/AIN[2][0]/REFB_6") (pintype "bidirectional"))
      (node (ref "XP21") (pin "1") (pinfunction "1_1") (pintype "passive"))
    )
    (net (code "12") (name "/MCU_TX") (class "Default")
      (node (ref "DD6") (pin "2") (pinfunction "RXD_2") (pintype "input"))
      (node (ref "DD7") (pin "7") (pinfunction "PA05/AIN[3][1]_7") (pintype "bidirectional"))
      (node (ref "XP22") (pin "1") (pinfunction "1_1") (pintype "passive"))
    )
    (net (code "13") (name "/SPI_MiSo") (class "Default")
      (node (ref "DD7") (pin "18") (pinfunction "PA23/hs/SER[0.1][1.1]SCL_18") (pintype "bidirectional"))
      (node (ref "R42") (pin "1") (pinfunction "1_1") (pintype "passive"))
      (node (ref "XP27") (pin "1") (pinfunction "1_1") (pintype "passive"))
    )
    (net (code "14") (name "/SPI_MiSo{slash}PUART_RTS") (class "Default")
      (node (ref "DD3") (pin "20") (pinfunction "P1_20") (pintype "passive"))
      (node (ref "X40") (pin "1") (pinfunction "1_1") (pintype "passive"))
      (node (ref "XS4") (pin "4") (pinfunction "4_4") (pintype "passive"))
    )
    (net (code "15") (name "/SPI_MoSi") (class "Default")
      (node (ref "DD7") (pin "17") (pinfunction "PA22/hs/SER[0.0][1.0]SDA_17") (pintype "bidirectional"))
      (node (ref "R45") (pin "1") (pinfunction "1_1") (pintype "passive"))
      (node (ref "XP28") (pin "1") (pinfunction "1_1") (pintype "passive"))
    )
    (net (code "16") (name "/SPI_SCLK") (class "Default")
      (node (ref "DD7") (pin "16") (pinfunction "PA19_16") (pintype "bidirectional"))
      (node (ref "R44") (pin "1") (pinfunction "1_1") (pintype "passive"))
      (node (ref "XP29") (pin "1") (pinfunction "1_1") (pintype "passive"))
    )
    (net (code "17") (name "/SPI_SCLK{slash}PUART_CTS") (class "Default")
      (node (ref "DD3") (pin "21") (pinfunction "P3_21") (pintype "passive"))
      (node (ref "X41") (pin "1") (pinfunction "1_1") (pintype "passive"))
      (node (ref "XS4") (pin "5") (pinfunction "5_5") (pintype "passive"))
    )
    (net (code "18") (name "/SPI_nCS_IMU") (class "Default")
      (node (ref "DD7") (pin "15") (pinfunction "PA18_15") (pintype "bidirectional"))
      (node (ref "R43") (pin "1") (pinfunction "1_1") (pintype "passive"))
      (node (ref "XP30") (pin "1") (pinfunction "1_1") (pintype "passive"))
    )
    (net (code "19") (name "/USB_N") (class "Default")
      (node (ref "DD6") (pin "7") (pinfunction "USBDM_7") (pintype "input"))
      (node (ref "XS5") (pin "2") (pinfunction "2_2") (pintype "passive"))
    )
    (net (code "20") (name "/USB_P") (class "Default")
      (node (ref "DD6") (pin "6") (pinfunction "USBDP_6") (pintype "input"))
      (node (ref "XS5") (pin "3") (pinfunction "3_3") (pintype "passive"))
    )
    (net (code "21") (name "/nReset") (class "Default")
      (node (ref "DD7") (pin "19") (pinfunction "~{RESET}_19") (pintype "passive"))
      (node (ref "SB3") (pin "1") (pinfunction "COMMON_1") (pintype "passive"))
      (node (ref "XP11") (pin "1") (pinfunction "1_1") (pintype "passive"))
      (node (ref "XP13") (pin "1") (pinfunction "1_1") (pintype "passive"))
    )
    (net (code "22") (name "/usbD+_to_chg") (class "Default")
      (node (ref "DA2") (pin "3") (pinfunction "D+_3") (pintype "passive"))
      (node (ref "XS1") (pin "3") (pinfunction "3_3") (pintype "passive"))
    )
    (net (code "23") (name "/usbD-_to_chg") (class "Default")
      (node (ref "DA2") (pin "4") (pinfunction "D-_4") (pintype "passive"))
      (node (ref "XS1") (pin "2") (pinfunction "2_2") (pintype "passive"))
    )
    (net (code "24") (name "3,3V") (class "Default")
      (node (ref "C49") (pin "2") (pinfunction "2_2") (pintype "passive"))
      (node (ref "C50") (pin "1") (pinfunction "1_1") (pintype "passive"))
      (node (ref "C53") (pin "2") (pinfunction "2_2") (pintype "passive"))
      (node (ref "C56") (pin "2") (pinfunction "2_2") (pintype "passive"))
      (node (ref "DA3") (pin "1") (pinfunction "VOUT_1") (pintype "passive"))
      (node (ref "DD7") (pin "23") (pinfunction "VDDIO_23") (pintype "input"))
      (node (ref "R40") (pin "2") (pinfunction "2_2") (pintype "passive"))
      (node (ref "R46") (pin "1") (pinfunction "1_1") (pintype "passive"))
      (node (ref "R47") (pin "2") (pinfunction "2_2") (pintype "passive"))
      (node (ref "XP11") (pin "10") (pinfunction "10_10") (pintype "passive"))
      (node (ref "XP14") (pin "1") (pinfunction "1_1") (pintype "passive"))
      (node (ref "XP24") (pin "1") (pinfunction "1_1") (pintype "passive"))
      (node (ref "ZL4") (pin "1") (pinfunction "1_1") (pintype "passive"))
    )
    (net (code "25") (name "GND") (class "Default")
      (node (ref "C1") (pin "1") (pinfunction "1_1") (pintype "passive"))
      (node (ref "C10") (pin "1") (pinfunction "1_1") (pintype "passive"))
      (node (ref "C11") (pin "1") (pinfunction "1_1") (pintype "passive"))
      (node (ref "C12") (pin "1") (pinfunction "1_1") (pintype "passive"))
      (node (ref "C13") (pin "1") (pinfunction "1_1") (pintype "passive"))
      (node (ref "C14") (pin "1") (pinfunction "1_1") (pintype "passive"))
      (node (ref "C16") (pin "1") (pinfunction "1_1") (pintype "passive"))
      (node (ref "C17") (pin "1") (pinfunction "1_1") (pintype "passive"))
      (node (ref "C18") (pin "1") (pinfunction "1_1") (pintype "passive"))
      (node (ref "C19") (pin "1") (pinfunction "1_1") (pintype "passive"))
      (node (ref "C2") (pin "1") (pinfunction "1_1") (pintype "passive"))
      (node (ref "C20") (pin "1") (pinfunction "1_1") (pintype "passive"))
      (node (ref "C21") (pin "1") (pinfunction "1_1") (pintype "passive"))
      (node (ref "C22") (pin "1") (pinfunction "1_1") (pintype "passive"))
      (node (ref "C23") (pin "1") (pinfunction "1_1") (pintype "passive"))
      (node (ref "C24") (pin "1") (pinfunction "1_1") (pintype "passive"))
      (node (ref "C25") (pin "1") (pinfunction "1_1") (pintype "passive"))
      (node (ref "C26") (pin "2") (pinfunction "2_2") (pintype "passive"))
      (node (ref "C27") (pin "1") (pinfunction "1_1") (pintype "passive"))
      (node (ref "C29") (pin "1") (pinfunction "1_1") (pintype "passive"))
      (node (ref "C3") (pin "1") (pinfunction "1_1") (pintype "passive"))
      (node (ref "C30") (pin "2") (pinfunction "2_2") (pintype "passive"))
      (node (ref "C31") (pin "1") (pinfunction "1_1") (pintype "passive"))
      (node (ref "C32") (pin "2") (pinfunction "2_2") (pintype "passive"))
      (node (ref "C33") (pin "1") (pinfunction "1_1") (pintype "passive"))
      (node (ref "C34") (pin "1") (pinfunction "1_1") (pintype "passive"))
      (node (ref "C35") (pin "1") (pinfunction "1_1") (pintype "passive"))
      (node (ref "C36") (pin "1") (pinfunction "1_1") (pintype "passive"))
      (node (ref "C37") (pin "1") (pinfunction "1_1") (pintype "passive"))
      (node (ref "C38") (pin "1") (pinfunction "1_1") (pintype "passive"))
      (node (ref "C39") (pin "1") (pinfunction "1_1") (pintype "passive"))
      (node (ref "C4") (pin "1") (pinfunction "1_1") (pintype "passive"))
      (node (ref "C40") (pin "1") (pinfunction "1_1") (pintype "passive"))
      (node (ref "C41") (pin "1") (pinfunction "1_1") (pintype "passive"))
      (node (ref "C42") (pin "1") (pinfunction "1_1") (pintype "passive"))
      (node (ref "C43") (pin "1") (pinfunction "1_1") (pintype "passive"))
      (node (ref "C44") (pin "1") (pinfunction "1_1") (pintype "passive"))
      (node (ref "C45") (pin "1") (pinfunction "1_1") (pintype "passive"))
      (node (ref "C46") (pin "1") (pinfunction "1_1") (pintype "passive"))
      (node (ref "C47") (pin "1") (pinfunction "1_1") (pintype "passive"))
      (node (ref "C48") (pin "1") (pinfunction "1_1") (pintype "passive"))
      (node (ref "C49") (pin "1") (pinfunction "1_1") (pintype "passive"))
      (node (ref "C5") (pin "1") (pinfunction "1_1") (pintype "passive"))
      (node (ref "C50") (pin "2") (pinfunction "2_2") (pintype "passive"))
      (node (ref "C51") (pin "1") (pinfunction "1_1") (pintype "passive"))
      (node (ref "C52") (pin "1") (pinfunction "1_1") (pintype "passive"))
      (node (ref "C53") (pin "1") (pinfunction "1_1") (pintype "passive"))
      (node (ref "C54") (pin "2") (pinfunction "2_2") (pintype "passive"))
      (node (ref "C55") (pin "2") (pinfunction "2_2") (pintype "passive"))
      (node (ref "C56") (pin "1") (pinfunction "1_1") (pintype "passive"))
      (node (ref "C57") (pin "2") (pinfunction "2_2") (pintype "passive"))
      (node (ref "C58") (pin "1") (pinfunction "1_1") (pintype "passive"))
      (node (ref "C59") (pin "1") (pinfunction "1_1") (pintype "passive"))
      (node (ref "C6") (pin "1") (pinfunction "1_1") (pintype "passive"))
      (node (ref "C60") (pin "1") (pinfunction "1_1") (pintype "passive"))
      (node (ref "C61") (pin "1") (pinfunction "1_1") (pintype "passive"))
      (node (ref "C62") (pin "1") (pinfunction "1_1") (pintype "passive"))
      (node (ref "C63") (pin "1") (pinfunction "1_1") (pintype "passive"))
      (node (ref "C64") (pin "1") (pinfunction "1_1") (pintype "passive"))
      (node (ref "C65") (pin "1") (pinfunction "1_1") (pintype "passive"))
      (node (ref "C66") (pin "1") (pinfunction "1_1") (pintype "passive"))
      (node (ref "C67") (pin "1") (pinfunction "1_1") (pintype "passive"))
      (node (ref "C68") (pin "1") (pinfunction "1_1") (pintype "passive"))
      (node (ref "C7") (pin "1") (pinfunction "1_1") (pintype "passive"))
      (node (ref "C8") (pin "1") (pinfunction "1_1") (pintype "passive"))
      (node (ref "C9") (pin "1") (pinfunction "1_1") (pintype "passive"))
      (node (ref "DA1") (pin "2") (pinfunction "GND_2") (pintype "passive"))
      (node (ref "DA10") (pin "2") (pinfunction "GND_2") (pintype "passive"))
      (node (ref "DA11") (pin "2") (pinfunction "2_2") (pintype "passive"))
      (node (ref "DA11") (pin "3") (pinfunction "3_3") (pintype "passive"))
      (node (ref "DA12") (pin "2") (pinfunction "2_2") (pintype "passive"))
      (node (ref "DA13") (pin "2") (pinfunction "VSS_2") (pintype "passive"))
      (node (ref "DA2") (pin "17") (pinfunction "GND_17") (pintype "passive"))
      (node (ref "DA2") (pin "18") (pinfunction "GND_18") (pintype "passive"))
      (node (ref "DA2") (pin "25") (pinfunction "Epad_25") (pintype "passive"))
      (node (ref "DA3") (pin "11") (pinfunction "EPgnd_11") (pintype "passive"))
      (node (ref "DA3") (pin "3") (pinfunction "PGND_3") (pintype "passive"))
      (node (ref "DA3") (pin "9") (pinfunction "GND_9") (pintype "passive"))
      (node (ref "DA4") (pin "2") (pinfunction "VSS_2") (pintype "passive"))
      (node (ref "DA5") (pin "2") (pinfunction "GND_2") (pintype "passive"))
      (node (ref "DA6") (pin "11") (pinfunction "EPgnd_11") (pintype "passive"))
      (node (ref "DA6") (pin "3") (pinfunction "PGND_3") (pintype "passive"))
      (node (ref "DA6") (pin "9") (pinfunction "GND_9") (pintype "passive"))
      (node (ref "DA7") (pin "2") (pinfunction "VSS_2") (pintype "passive"))
      (node (ref "DA8") (pin "2") (pinfunction "Gnd_2") (pintype "power_in"))
      (node (ref "DA9") (pin "2") (pinfunction "2_2") (pintype "passive"))
      (node (ref "DD1") (pin "1") (pinfunction "PG_1_1") (pintype "passive"))
      (node (ref "DD1") (pin "12") (pinfunction "GND_12") (pintype "passive"))
      (node (ref "DD1") (pin "2") (pinfunction "PG_2_2") (pintype "passive"))
      (node (ref "DD1") (pin "29") (pinfunction "EP_29") (pintype "passive"))
      (node (ref "DD2") (pin "11") (pinfunction "EP_11") (pintype "passive"))
      (node (ref "DD2") (pin "6") (pinfunction "CSP_6") (pintype "passive"))
      (node (ref "DD3") (pin "17") (pinfunction "TMC_17") (pintype "passive"))
      (node (ref "DD3") (pin "33") (pinfunction "EP_GND_33") (pintype "passive"))
      (node (ref "DD4") (pin "6") (pinfunction "GND_6") (pintype "passive"))
      (node (ref "DD4") (pin "7") (pinfunction "GND_7") (pintype "passive"))
      (node (ref "DD5") (pin "4") (pinfunction "GND_4") (pintype "passive"))
      (node (ref "DD6") (pin "13") (pinfunction "GND_13") (pintype "power_in"))
      (node (ref "DD6") (pin "17") (pinfunction "GND_17") (pintype "power_in"))
      (node (ref "DD6") (pin "3") (pinfunction "GND_3") (pintype "power_in"))
      (node (ref "DD7") (pin "21") (pinfunction "GND_21") (pintype "passive"))
      (node (ref "DD7") (pin "25") (pinfunction "ExPadGnd_25") (pintype "passive"))
      (node (ref "DD7") (pin "9") (pinfunction "GNDANA_9") (pintype "passive"))
      (node (ref "DD8") (pin "6") (pinfunction "GND_6") (pintype "passive"))
      (node (ref "DD8") (pin "7") (pinfunction "GND_7") (pintype "passive"))
      (node (ref "G1") (pin "2") (pinfunction "2_2") (pintype "passive"))
      (node (ref "G1") (pin "4") (pinfunction "4_4") (pintype "passive"))
      (node (ref "HL1") (pin "K") (pinfunction "K_K") (pintype "passive"))
      (node (ref "HL11") (pin "K") (pinfunction "K_K") (pintype "passive"))
      (node (ref "HL12") (pin "K") (pinfunction "K_K") (pintype "passive"))
      (node (ref "HL16") (pin "K") (pinfunction "K_K") (pintype "passive"))
      (node (ref "HL17") (pin "K") (pinfunction "K_K") (pintype "passive"))
      (node (ref "R10") (pin "1") (pinfunction "1_1") (pintype "passive"))
      (node (ref "R12") (pin "1") (pinfunction "1_1") (pintype "passive"))
      (node (ref "R13") (pin "1") (pinfunction "1_1") (pintype "passive"))
      (node (ref "R16") (pin "2") (pinfunction "2_2") (pintype "passive"))
      (node (ref "R22") (pin "2") (pinfunction "2_2") (pintype "passive"))
      (node (ref "R23") (pin "2") (pinfunction "2_2") (pintype "passive"))
      (node (ref "R29") (pin "1") (pinfunction "1_1") (pintype "passive"))
      (node (ref "R32") (pin "1") (pinfunction "1_1") (pintype "passive"))
      (node (ref "R35") (pin "2") (pinfunction "2_2") (pintype "passive"))
      (node (ref "R37") (pin "2") (pinfunction "2_2") (pintype "passive"))
      (node (ref "R38") (pin "2") (pinfunction "2_2") (pintype "passive"))
      (node (ref "R41") (pin "1") (pinfunction "1_1") (pintype "passive"))
      (node (ref "R48") (pin "2") (pinfunction "2_2") (pintype "passive"))
      (node (ref "R49") (pin "2") (pinfunction "2_2") (pintype "passive"))
      (node (ref "R51") (pin "2") (pinfunction "2_2") (pintype "passive"))
      (node (ref "R53") (pin "1") (pinfunction "1_1") (pintype "passive"))
      (node (ref "R57") (pin "2") (pinfunction "2_2") (pintype "passive"))
      (node (ref "R60") (pin "2") (pinfunction "2_2") (pintype "passive"))
      (node (ref "R65") (pin "1") (pinfunction "1_1") (pintype "passive"))
      (node (ref "R7") (pin "1") (pinfunction "1_1") (pintype "passive"))
      (node (ref "R9") (pin "1") (pinfunction "1_1") (pintype "passive"))
      (node (ref "RP1") (pin "3") (pinfunction "TAP_3") (pintype "passive"))
      (node (ref "RP2") (pin "3") (pinfunction "TAP_3") (pintype "passive"))
      (node (ref "RP6") (pin "1") (pinfunction "TOP_1") (pintype "passive"))
      (node (ref "RP6") (pin "2") (pinfunction "BOT_2") (pintype "passive"))
      (node (ref "SB1") (pin "1") (pinfunction "COMMON_1") (pintype "passive"))
      (node (ref "SB3") (pin "2") (pinfunction "NO_2") (pintype "passive"))
      (node (ref "SB4") (pin "2") (pinfunction "NO_2") (pintype "passive"))
      (node (ref "VD5") (pin "2") (pinfunction "A_2") (pintype "passive"))
      (node (ref "VT3") (pin "2") (pinfunction "E_2") (pintype "passive"))
      (node (ref "VT4") (pin "2") (pinfunction "E_2") (pintype "passive"))
      (node (ref "VT5") (pin "2") (pinfunction "S_2") (pintype "passive"))
      (node (ref "WA1") (pin "2") (pinfunction "2_2") (pintype "passive"))
      (node (ref "X10") (pin "1") (pinfunction "1_1") (pintype "passive"))
      (node (ref "X12") (pin "1") (pinfunction "1_1") (pintype "passive"))
      (node (ref "X2") (pin "1") (pinfunction "1_1") (pintype "passive"))
      (node (ref "X20") (pin "1") (pinfunction "1_1") (pintype "passive"))
      (node (ref "X31") (pin "1") (pinfunction "1_1") (pintype "passive"))
      (node (ref "X37") (pin "1") (pinfunction "1_1") (pintype "passive"))
      (node (ref "X39") (pin "1") (pinfunction "1_1") (pintype "passive"))
      (node (ref "X4") (pin "1") (pinfunction "1_1") (pintype "passive"))
      (node (ref "X49") (pin "1") (pinfunction "1_1") (pintype "passive"))
      (node (ref "X51") (pin "1") (pinfunction "1_1") (pintype "passive"))
      (node (ref "X53") (pin "1") (pinfunction "1_1") (pintype "passive"))
      (node (ref "X55") (pin "1") (pinfunction "1_1") (pintype "passive"))
      (node (ref "X57") (pin "1") (pinfunction "1_1") (pintype "passive"))
      (node (ref "X59") (pin "1") (pinfunction "1_1") (pintype "passive"))
      (node (ref "X61") (pin "1") (pinfunction "1_1") (pintype "passive"))
      (node (ref "X64") (pin "1") (pinfunction "1_1") (pintype "passive"))
      (node (ref "X65") (pin "1") (pinfunction "1_1") (pintype "passive"))
      (node (ref "X67") (pin "1") (pinfunction "1_1") (pintype "passive"))
      (node (ref "X69") (pin "1") (pinfunction "1_1") (pintype "passive"))
      (node (ref "X7") (pin "1") (pinfunction "1_1") (pintype "passive"))
      (node (ref "X71") (pin "1") (pinfunction "1_1") (pintype "passive"))
      (node (ref "X73") (pin "1") (pinfunction "1_1") (pintype "passive"))
      (node (ref "X75") (pin "1") (pinfunction "1_1") (pintype "passive"))
      (node (ref "X77") (pin "1") (pinfunction "1_1") (pintype "passive"))
      (node (ref "X8") (pin "1") (pinfunction "1_1") (pintype "passive"))
      (node (ref "XP1") (pin "1") (pinfunction "1_1") (pintype "passive"))
      (node (ref "XP10") (pin "2") (pinfunction "2_2") (pintype "passive"))
      (node (ref "XP11") (pin "2") (pinfunction "2_2") (pintype "passive"))
      (node (ref "XP11") (pin "6") (pinfunction "6_6") (pintype "passive"))
      (node (ref "XP11") (pin "8") (pinfunction "8_8") (pintype "passive"))
      (node (ref "XP15") (pin "1") (pinfunction "1_1") (pintype "passive"))
      (node (ref "XP2") (pin "1") (pinfunction "1_1") (pintype "passive"))
      (node (ref "XP23") (pin "2") (pinfunction "2_2") (pintype "passive"))
      (node (ref "XP26") (pin "1") (pinfunction "1_1") (pintype "passive"))
      (node (ref "XP3") (pin "1") (pinfunction "1_1") (pintype "passive"))
      (node (ref "XP33") (pin "1") (pinfunction "1_1") (pintype "passive"))
      (node (ref "XP34") (pin "1") (pinfunction "1_1") (pintype "passive"))
      (node (ref "XP39") (pin "1") (pinfunction "1_1") (pintype "passive"))
      (node (ref "XP40") (pin "1") (pinfunction "1_1") (pintype "passive"))
      (node (ref "XP41") (pin "2") (pinfunction "2_2") (pintype "passive"))
      (node (ref "XP5") (pin "1") (pinfunction "1_1") (pintype "passive"))
      (node (ref "XP6") (pin "1") (pinfunction "1_1") (pintype "passive"))
      (node (ref "XP7") (pin "1") (pinfunction "1_1") (pintype "passive"))
      (node (ref "XP8") (pin "1") (pinfunction "1_1") (pintype "passive"))
      (node (ref "XP9") (pin "1") (pinfunction "1_1") (pintype "passive"))
      (node (ref "XS1") (pin "5") (pinfunction "5_5") (pintype "passive"))
      (node (ref "XS1") (pin "6") (pinfunction "6_6") (pintype "passive"))
      (node (ref "XS3") (pin "5") (pinfunction "5_5") (pintype "passive"))
      (node (ref "XS3") (pin "6") (pinfunction "6_6") (pintype "passive"))
      (node (ref "XS4") (pin "3") (pinfunction "3_3") (pintype "passive"))
      (node (ref "XS5") (pin "5") (pinfunction "5_5") (pintype "passive"))
      (node (ref "XS5") (pin "6") (pinfunction "6_6") (pintype "passive"))
      (node (ref "XT") (pin "1") (pinfunction "1_1") (pintype "passive"))
      (node (ref "XT2") (pin "1") (pinfunction "1_1") (pintype "passive"))
      (node (ref "XT3") (pin "1") (pinfunction "1_1") (pintype "passive"))
      (node (ref "XT5") (pin "2") (pinfunction "2_2") (pintype "passive"))
    )
    (net (code "26") (name "LED_BLUE") (class "Default")
      (node (ref "DD7") (pin "11") (pinfunction "PA14/XOSC_11") (pintype "bidirectional"))
      (node (ref "HL8") (pin "A") (pinfunction "A_A") (pintype "passive"))
      (node (ref "XP37") (pin "1") (pinfunction "1_1") (pintype "passive"))
    )
    (net (code "27") (name "LED_GREEN") (class "Default")
      (node (ref "DD7") (pin "10") (pinfunction "PA08/AIN[6]_10") (pintype "bidirectional"))
      (node (ref "HL9") (pin "A") (pinfunction "A_A") (pintype "passive"))
      (node (ref "XP38") (pin "1") (pinfunction "1_1") (pintype "passive"))
    )
    (net (code "28") (name "Net-(C28-Pad1)") (class "Default")
      (node (ref "C28") (pin "1") (pinfunction "1_1") (pintype "passive"))
      (node (ref "DA2") (pin "19") (pinfunction "SW_19") (pintype "passive"))
      (node (ref "DA2") (pin "20") (pinfunction "SW_20") (pintype "passive"))
      (node (ref "L2") (pin "1") (pinfunction "1_1") (pintype "passive"))
    )
    (net (code "29") (name "Net-(C31-Pad2)") (class "Default")
      (node (ref "C31") (pin "2") (pinfunction "2_2") (pintype "passive"))
      (node (ref "C36") (pin "2") (pinfunction "2_2") (pintype "passive"))
      (node (ref "DA2") (pin "15") (pinfunction "SYS_15") (pintype "passive"))
      (node (ref "DA2") (pin "16") (pinfunction "SYS_16") (pintype "passive"))
      (node (ref "HL2") (pin "A") (pinfunction "A_A") (pintype "passive"))
      (node (ref "HL3") (pin "A") (pinfunction "A_A") (pintype "passive"))
      (node (ref "L2") (pin "2") (pinfunction "2_2") (pintype "passive"))
      (node (ref "R17") (pin "2") (pinfunction "2_2") (pintype "passive"))
      (node (ref "X36") (pin "1") (pinfunction "1_1") (pintype "passive"))
    )
    (net (code "30") (name "Net-(C35-Pad2)") (class "Default")
      (node (ref "C35") (pin "2") (pinfunction "2_2") (pintype "passive"))
      (node (ref "DA2") (pin "13") (pinfunction "BAT_13") (pintype "passive"))
      (node (ref "DA2") (pin "14") (pinfunction "BAT_14") (pintype "passive"))
      (node (ref "X38") (pin "1") (pinfunction "1_1") (pintype "passive"))
    )
    (net (code "31") (name "Net-(C38-Pad2)") (class "Default")
      (node (ref "C38") (pin "2") (pinfunction "2_2") (pintype "passive"))
      (node (ref "C40") (pin "2") (pinfunction "2_2") (pintype "passive"))
      (node (ref "L3") (pin "2") (pinfunction "2_2") (pintype "passive"))
      (node (ref "L4") (pin "1") (pinfunction "1_1") (pintype "passive"))
    )
    (net (code "32") (name "Net-(C42-Pad2)") (class "Default")
      (node (ref "C42") (pin "2") (pinfunction "2_2") (pintype "passive"))
      (node (ref "L4") (pin "2") (pinfunction "2_2") (pintype "passive"))
      (node (ref "WA1") (pin "1") (pinfunction "1_1") (pintype "passive"))
    )
    (net (code "33") (name "Net-(DA1-EN)") (class "Default")
      (node (ref "DA1") (pin "3") (pinfunction "EN_3") (pintype "passive"))
      (node (ref "R4") (pin "1") (pinfunction "1_1") (pintype "passive"))
      (node (ref "XS4") (pin "1") (pinfunction "1_1") (pintype "passive"))
    )
    (net (code "34") (name "Net-(DA2-BTST)") (class "Default")
      (node (ref "C28") (pin "2") (pinfunction "2_2") (pintype "passive"))
      (node (ref "DA2") (pin "21") (pinfunction "BTST_21") (pintype "passive"))
    )
    (net (code "35") (name "Net-(DA2-ICHG)") (class "Default")
      (node (ref "DA2") (pin "10") (pinfunction "ICHG_10") (pintype "passive"))
      (node (ref "R11") (pin "2") (pinfunction "2_2") (pintype "passive"))
    )
    (net (code "36") (name "Net-(DA2-ILIM)") (class "Default")
      (node (ref "DA2") (pin "8") (pinfunction "ILIM_8") (pintype "passive"))
      (node (ref "R8") (pin "2") (pinfunction "2_2") (pintype "passive"))
    )
    (net (code "37") (name "Net-(DA2-OTG)") (class "Default")
      (node (ref "DA2") (pin "6") (pinfunction "OTG_6") (pintype "passive"))
      (node (ref "R17") (pin "1") (pinfunction "1_1") (pintype "passive"))
      (node (ref "XP7") (pin "2") (pinfunction "2_2") (pintype "passive"))
    )
    (net (code "38") (name "Net-(DA2-PMID)") (class "Default")
      (node (ref "C27") (pin "2") (pinfunction "2_2") (pintype "passive"))
      (node (ref "DA2") (pin "23") (pinfunction "PMID_23") (pintype "passive"))
    )
    (net (code "39") (name "Net-(DA2-REGN)") (class "Default")
      (node (ref "C29") (pin "2") (pinfunction "2_2") (pintype "passive"))
      (node (ref "DA2") (pin "22") (pinfunction "REGN_22") (pintype "passive"))
      (node (ref "R33") (pin "1") (pinfunction "1_1") (pintype "passive"))
    )
    (net (code "40") (name "Net-(DA2-STAT)") (class "Default")
      (node (ref "DA2") (pin "5") (pinfunction "STAT_5") (pintype "passive"))
      (node (ref "R24") (pin "1") (pinfunction "1_1") (pintype "passive"))
    )
    (net (code "41") (name "Net-(DA2-TS)") (class "Default")
      (node (ref "DA2") (pin "11") (pinfunction "TS_11") (pintype "passive"))
      (node (ref "R33") (pin "2") (pinfunction "2_2") (pintype "passive"))
      (node (ref "R35") (pin "1") (pinfunction "1_1") (pintype "passive"))
      (node (ref "X54") (pin "1") (pinfunction "1_1") (pintype "passive"))
    )
    (net (code "42") (name "Net-(DA2-VAC)") (class "Default")
      (node (ref "C25") (pin "2") (pinfunction "2_2") (pintype "passive"))
      (node (ref "C26") (pin "1") (pinfunction "1_1") (pintype "passive"))
      (node (ref "DA2") (pin "1") (pinfunction "VAC_1") (pintype "passive"))
      (node (ref "DA2") (pin "24") (pinfunction "VBUS_24") (pintype "passive"))
      (node (ref "R5") (pin "2") (pinfunction "2_2") (pintype "passive"))
      (node (ref "X52") (pin "1") (pinfunction "1_1") (pintype "passive"))
      (node (ref "XP4") (pin "2") (pinfunction "2_2") (pintype "passive"))
    )
    (net (code "43") (name "Net-(DA2-VSET)") (class "Default")
      (node (ref "DA2") (pin "12") (pinfunction "VSET_12") (pintype "passive"))
      (node (ref "XP9") (pin "2") (pinfunction "2_2") (pintype "passive"))
    )
    (net (code "44") (name "Net-(DA2-~{CE})") (class "Default")
      (node (ref "DA2") (pin "9") (pinfunction "~{CE}_9") (pintype "passive"))
      (node (ref "XP8") (pin "2") (pinfunction "2_2") (pintype "passive"))
    )
    (net (code "45") (name "Net-(DA2-~{PG})") (class "Default")
      (node (ref "DA2") (pin "7") (pinfunction "~{PG}_7") (pintype "passive"))
      (node (ref "R25") (pin "1") (pinfunction "1_1") (pintype "passive"))
    )
    (net (code "46") (name "Net-(DA3-EN)") (class "Default")
      (node (ref "C45") (pin "2") (pinfunction "2_2") (pintype "passive"))
      (node (ref "C47") (pin "2") (pinfunction "2_2") (pintype "passive"))
      (node (ref "DA3") (pin "5") (pinfunction "VIN_5") (pintype "passive"))
      (node (ref "DA3") (pin "6") (pinfunction "EN_6") (pintype "passive"))
      (node (ref "DA3") (pin "7") (pinfunction "PS/SYNC_7") (pintype "passive"))
      (node (ref "VD1") (pin "2") (pintype "passive"))
      (node (ref "VT2") (pin "3") (pinfunction "S_3") (pintype "passive"))
    )
    (net (code "47") (name "Net-(DA3-FB)") (class "Default")
      (node (ref "DA3") (pin "10") (pinfunction "FB_10") (pintype "passive"))
      (node (ref "R40") (pin "1") (pinfunction "1_1") (pintype "passive"))
      (node (ref "R41") (pin "2") (pinfunction "2_2") (pintype "passive"))
    )
    (net (code "48") (name "Net-(DA3-L1)") (class "Default")
      (node (ref "DA3") (pin "4") (pinfunction "L1_4") (pintype "passive"))
      (node (ref "L5") (pin "1") (pinfunction "1_1") (pintype "passive"))
    )
    (net (code "49") (name "Net-(DA3-L2)") (class "Default")
      (node (ref "DA3") (pin "2") (pinfunction "L2_2") (pintype "passive"))
      (node (ref "L5") (pin "2") (pinfunction "2_2") (pintype "passive"))
    )
    (net (code "50") (name "Net-(DA3-VINA)") (class "Default")
      (node (ref "C48") (pin "2") (pinfunction "2_2") (pintype "passive"))
      (node (ref "DA3") (pin "8") (pinfunction "VINA_8") (pintype "passive"))
    )
    (net (code "51") (name "Net-(DA4-PROG)") (class "Default")
      (node (ref "DA4") (pin "5") (pinfunction "PROG_5") (pintype "passive"))
      (node (ref "R48") (pin "1") (pinfunction "1_1") (pintype "passive"))
    )
    (net (code "52") (name "Net-(DA4-STAT)") (class "Default")
      (node (ref "DA4") (pin "1") (pinfunction "STAT_1") (pintype "passive"))
      (node (ref "HL10") (pin "K") (pinfunction "K_K") (pintype "passive"))
    )
    (net (code "53") (name "Net-(DA5-EN)") (class "Default")
      (node (ref "C58") (pin "2") (pinfunction "2_2") (pintype "passive"))
      (node (ref "C59") (pin "2") (pinfunction "2_2") (pintype "passive"))
      (node (ref "DA5") (pin "1") (pinfunction "VIN_1") (pintype "passive"))
      (node (ref "DA5") (pin "3") (pinfunction "EN_3") (pintype "passive"))
      (node (ref "X50") (pin "1") (pinfunction "1_1") (pintype "passive"))
    )
    (net (code "54") (name "Net-(DA6-EN)") (class "Default")
      (node (ref "C60") (pin "2") (pinfunction "2_2") (pintype "passive"))
      (node (ref "C61") (pin "2") (pinfunction "2_2") (pintype "passive"))
      (node (ref "DA6") (pin "5") (pinfunction "VIN_5") (pintype "passive"))
      (node (ref "DA6") (pin "6") (pinfunction "EN_6") (pintype "passive"))
      (node (ref "DA6") (pin "7") (pinfunction "PS/SYNC_7") (pintype "passive"))
      (node (ref "VD2") (pin "2") (pintype "passive"))
      (node (ref "VT1") (pin "3") (pinfunction "S_3") (pintype "passive"))
    )
    (net (code "55") (name "Net-(DA6-FB)") (class "Default")
      (node (ref "DA6") (pin "10") (pinfunction "FB_10") (pintype "passive"))
      (node (ref "R3") (pin "1") (pinfunction "1_1") (pintype "passive"))
      (node (ref "R7") (pin "2") (pinfunction "2_2") (pintype "passive"))
    )
    (net (code "56") (name "Net-(DA6-L1)") (class "Default")
      (node (ref "DA6") (pin "4") (pinfunction "L1_4") (pintype "passive"))
      (node (ref "L6") (pin "2") (pinfunction "2_2") (pintype "passive"))
    )
    (net (code "57") (name "Net-(DA6-L2)") (class "Default")
      (node (ref "DA6") (pin "2") (pinfunction "L2_2") (pintype "passive"))
      (node (ref "L6") (pin "1") (pinfunction "1_1") (pintype "passive"))
    )
    (net (code "58") (name "Net-(DA6-VINA)") (class "Default")
      (node (ref "C62") (pin "2") (pinfunction "2_2") (pintype "passive"))
      (node (ref "DA6") (pin "8") (pinfunction "VINA_8") (pintype "passive"))
    )
    (net (code "59") (name "Net-(DA6-VOUT)") (class "Default")
      (node (ref "C63") (pin "2") (pinfunction "2_2") (pintype "passive"))
      (node (ref "C64") (pin "2") (pinfunction "2_2") (pintype "passive"))
      (node (ref "DA6") (pin "1") (pinfunction "VOUT_1") (pintype "passive"))
      (node (ref "R14") (pin "2") (pinfunction "2_2") (pintype "passive"))
      (node (ref "R3") (pin "2") (pinfunction "2_2") (pintype "passive"))
      (node (ref "X60") (pin "1") (pinfunction "1_1") (pintype "passive"))
    )
    (net (code "60") (name "Net-(DA7-PROG)") (class "Default")
      (node (ref "DA7") (pin "5") (pinfunction "PROG_5") (pintype "passive"))
      (node (ref "R49") (pin "1") (pinfunction "1_1") (pintype "passive"))
    )
    (net (code "61") (name "Net-(DA7-STAT)") (class "Default")
      (node (ref "DA7") (pin "1") (pinfunction "STAT_1") (pintype "passive"))
      (node (ref "HL13") (pin "K") (pinfunction "K_K") (pintype "passive"))
    )
    (net (code "62") (name "Net-(DA8-En)") (class "Default")
      (node (ref "DA8") (pin "1") (pinfunction "Vin_1") (pintype "input"))
      (node (ref "DA8") (pin "3") (pinfunction "En_3") (pintype "input"))
      (node (ref "R50") (pin "1") (pinfunction "1_1") (pintype "passive"))
      (node (ref "X62") (pin "1") (pinfunction "1_1") (pintype "passive"))
    )
    (net (code "63") (name "Net-(DA8-Ilim)") (class "Default")
      (node (ref "DA8") (pin "5") (pinfunction "Ilim_5") (pintype "input"))
      (node (ref "R51") (pin "1") (pinfunction "1_1") (pintype "passive"))
    )
    (net (code "64") (name "Net-(DA8-Vout)") (class "Default")
      (node (ref "DA8") (pin "6") (pinfunction "Vout_6") (pintype "output"))
      (node (ref "X63") (pin "1") (pinfunction "1_1") (pintype "passive"))
    )
    (net (code "65") (name "Net-(DA8-~{Fault})") (class "Default")
      (node (ref "DA8") (pin "4") (pinfunction "~{Fault}_4") (pintype "open_collector"))
      (node (ref "HL14") (pin "K") (pinfunction "K_K") (pintype "passive"))
    )
    (net (code "66") (name "Net-(DA9-Pad1)") (class "Default")
      (node (ref "DA9") (pin "1") (pinfunction "1_1") (pintype "passive"))
      (node (ref "R54") (pin "2") (pinfunction "2_2") (pintype "passive"))
    )
    (net (code "67") (name "Net-(DA10-DIV)") (class "Default")
      (node (ref "DA10") (pin "4") (pinfunction "DIV_4") (pintype "passive"))
      (node (ref "R63") (pin "2") (pinfunction "2_2") (pintype "passive"))
      (node (ref "RP6") (pin "3") (pinfunction "TAP_3") (pintype "passive"))
    )
    (net (code "68") (name "Net-(DA10-OUT)") (class "Default")
      (node (ref "DA10") (pin "6") (pinfunction "OUT_6") (pintype "passive"))
      (node (ref "R64") (pin "1") (pinfunction "1_1") (pintype "passive"))
      (node (ref "X70") (pin "1") (pinfunction "1_1") (pintype "passive"))
    )
    (net (code "69") (name "Net-(DA10-SET)") (class "Default")
      (node (ref "DA10") (pin "3") (pinfunction "SET_3") (pintype "passive"))
      (node (ref "R61") (pin "1") (pinfunction "1_1") (pintype "passive"))
      (node (ref "RP5") (pin "3") (pinfunction "TAP_3") (pintype "passive"))
    )
    (net (code "70") (name "Net-(DA10-TRIG)") (class "Default")
      (node (ref "DA10") (pin "1") (pinfunction "TRIG_1") (pintype "passive"))
      (node (ref "R58") (pin "2") (pinfunction "2_2") (pintype "passive"))
      (node (ref "R59") (pin "1") (pinfunction "1_1") (pintype "passive"))
      (node (ref "VT3") (pin "3") (pinfunction "C_3") (pintype "passive"))
      (node (ref "X72") (pin "1") (pinfunction "1_1") (pintype "passive"))
    )
    (net (code "71") (name "Net-(DA11-Pad1)") (class "Default")
      (node (ref "DA11") (pin "1") (pinfunction "1_1") (pintype "passive"))
      (node (ref "R55") (pin "2") (pinfunction "2_2") (pintype "passive"))
    )
    (net (code "72") (name "Net-(DA12-Pad1)") (class "Default")
      (node (ref "DA12") (pin "1") (pinfunction "1_1") (pintype "passive"))
      (node (ref "R67") (pin "2") (pinfunction "2_2") (pintype "passive"))
    )
    (net (code "73") (name "Net-(DA12-Pad3)") (class "Default")
      (node (ref "DA12") (pin "3") (pinfunction "3_3") (pintype "passive"))
      (node (ref "R52") (pin "1") (pinfunction "1_1") (pintype "passive"))
    )
    (net (code "74") (name "Net-(DA13-PROG)") (class "Default")
      (node (ref "DA13") (pin "5") (pinfunction "PROG_5") (pintype "passive"))
      (node (ref "R69") (pin "2") (pinfunction "2_2") (pintype "passive"))
      (node (ref "R70") (pin "2") (pinfunction "2_2") (pintype "passive"))
    )
    (net (code "75") (name "Net-(DA13-STAT)") (class "Default")
      (node (ref "DA13") (pin "1") (pinfunction "STAT_1") (pintype "passive"))
      (node (ref "HL15") (pin "K") (pinfunction "K_K") (pintype "passive"))
    )
    (net (code "76") (name "Net-(DA13-VBAT)") (class "Default")
      (node (ref "C66") (pin "2") (pinfunction "2_2") (pintype "passive"))
      (node (ref "DA13") (pin "3") (pinfunction "VBAT_3") (pintype "passive"))
      (node (ref "X76") (pin "1") (pinfunction "1_1") (pintype "passive"))
    )
    (net (code "77") (name "Net-(DA13-VDD)") (class "Default")
      (node (ref "C65") (pin "2") (pinfunction "2_2") (pintype "passive"))
      (node (ref "DA13") (pin "4") (pinfunction "VDD_4") (pintype "passive"))
      (node (ref "R68") (pin "2") (pinfunction "2_2") (pintype "passive"))
      (node (ref "X74") (pin "1") (pinfunction "1_1") (pintype "passive"))
    )
    (net (code "78") (name "Net-(DD1-BAT_1)") (class "Default")
      (node (ref "C9") (pin "2") (pinfunction "2_2") (pintype "passive"))
      (node (ref "DD1") (pin "20") (pinfunction "BAT_1_20") (pintype "passive"))
      (node (ref "DD1") (pin "21") (pinfunction "BAT_2_21") (pintype "passive"))
      (node (ref "X3") (pin "1") (pinfunction "1_1") (pintype "passive"))
    )
    (net (code "79") (name "Net-(DD1-BST)") (class "Default")
      (node (ref "C15") (pin "1") (pinfunction "1_1") (pintype "passive"))
      (node (ref "DD1") (pin "6") (pinfunction "BST_6") (pintype "passive"))
    )
    (net (code "80") (name "Net-(DD1-CS_1)") (class "Default")
      (node (ref "DD1") (pin "25") (pinfunction "CS_1_25") (pintype "passive"))
      (node (ref "DD1") (pin "26") (pinfunction "CS_2_26") (pintype "passive"))
      (node (ref "L1") (pin "1") (pinfunction "1_1") (pintype "passive"))
    )
    (net (code "81") (name "Net-(DD1-CT)") (class "Default")
      (node (ref "C17") (pin "2") (pinfunction "2_2") (pintype "passive"))
      (node (ref "DD1") (pin "10") (pinfunction "CT_10") (pintype "passive"))
    )
    (net (code "82") (name "Net-(DD1-DCM)") (class "Default")
      (node (ref "DD1") (pin "5") (pinfunction "DCM_5") (pintype "passive"))
      (node (ref "XP1") (pin "2") (pinfunction "2_2") (pintype "passive"))
    )
    (net (code "83") (name "Net-(DD1-DC_1)") (class "Default")
      (node (ref "C7") (pin "2") (pinfunction "2_2") (pintype "passive"))
      (node (ref "DD1") (pin "3") (pinfunction "DC_1_3") (pintype "passive"))
      (node (ref "DD1") (pin "4") (pinfunction "DC_2_4") (pintype "passive"))
      (node (ref "X11") (pin "1") (pinfunction "1_1") (pintype "passive"))
    )
    (net (code "84") (name "Net-(DD1-IDC)") (class "Default")
      (node (ref "DD1") (pin "11") (pinfunction "IDC_11") (pintype "passive"))
      (node (ref "R28") (pin "2") (pinfunction "2_2") (pintype "passive"))
    )
    (net (code "85") (name "Net-(DD1-ISET)") (class "Default")
      (node (ref "DD1") (pin "13") (pinfunction "ISET_13") (pintype "passive"))
      (node (ref "RP4") (pin "1") (pinfunction "TOP_1") (pintype "passive"))
    )
    (net (code "86") (name "Net-(DD1-IUSB)") (class "Default")
      (node (ref "DD1") (pin "7") (pinfunction "IUSB_7") (pintype "passive"))
      (node (ref "XP3") (pin "2") (pinfunction "2_2") (pintype "passive"))
    )
    (net (code "87") (name "Net-(DD1-LX_1)") (class "Default")
      (node (ref "C15") (pin "2") (pinfunction "2_2") (pintype "passive"))
      (node (ref "DD1") (pin "27") (pinfunction "LX_1_27") (pintype "passive"))
      (node (ref "DD1") (pin "28") (pinfunction "LX_2_28") (pintype "passive"))
      (node (ref "L1") (pin "2") (pinfunction "2_2") (pintype "passive"))
    )
    (net (code "88") (name "Net-(DD1-SYS_1)") (class "Default")
      (node (ref "C16") (pin "2") (pinfunction "2_2") (pintype "passive"))
      (node (ref "C18") (pin "2") (pinfunction "2_2") (pintype "passive"))
      (node (ref "DD1") (pin "23") (pinfunction "SYS_1_23") (pintype "passive"))
      (node (ref "DD1") (pin "24") (pinfunction "SYS_2_24") (pintype "passive"))
      (node (ref "R26") (pin "2") (pinfunction "2_2") (pintype "passive"))
      (node (ref "R27") (pin "2") (pinfunction "2_2") (pintype "passive"))
      (node (ref "R30") (pin "2") (pinfunction "2_2") (pintype "passive"))
      (node (ref "R31") (pin "2") (pinfunction "2_2") (pintype "passive"))
      (node (ref "X30") (pin "1") (pinfunction "1_1") (pintype "passive"))
    )
    (net (code "89") (name "Net-(DD1-THM)") (class "Default")
      (node (ref "DD1") (pin "16") (pinfunction "THM_16") (pintype "passive"))
      (node (ref "R19") (pin "1") (pinfunction "1_1") (pintype "passive"))
      (node (ref "R23") (pin "1") (pinfunction "1_1") (pintype "passive"))
      (node (ref "X19") (pin "1") (pinfunction "1_1") (pintype "passive"))
    )
    (net (code "90") (name "Net-(DD1-USB)") (class "Default")
      (node (ref "C1") (pin "2") (pinfunction "2_2") (pintype "passive"))
      (node (ref "DD1") (pin "17") (pinfunction "USB_17") (pintype "passive"))
      (node (ref "R1") (pin "1") (pinfunction "1_1") (pintype "passive"))
      (node (ref "XS3") (pin "1") (pinfunction "1_1") (pintype "passive"))
    )
    (net (code "91") (name "Net-(DD1-USUS)") (class "Default")
      (node (ref "DD1") (pin "15") (pinfunction "USUS_15") (pintype "passive"))
      (node (ref "XP2") (pin "2") (pinfunction "2_2") (pintype "passive"))
    )
    (net (code "92") (name "Net-(DD1-VL)") (class "Default")
      (node (ref "C20") (pin "2") (pinfunction "2_2") (pintype "passive"))
      (node (ref "DD1") (pin "9") (pinfunction "VL_9") (pintype "passive"))
      (node (ref "R19") (pin "2") (pinfunction "2_2") (pintype "passive"))
    )
    (net (code "93") (name "Net-(DD1-~{CEN})") (class "Default")
      (node (ref "DD1") (pin "14") (pinfunction "~{CEN}_14") (pintype "passive"))
      (node (ref "XP5") (pin "2") (pinfunction "2_2") (pintype "passive"))
    )
    (net (code "94") (name "Net-(DD1-~{CHG})") (class "Default")
      (node (ref "DD1") (pin "22") (pinfunction "~{CHG}_22") (pintype "passive"))
      (node (ref "HL4") (pin "K") (pinfunction "K_K") (pintype "passive"))
      (node (ref "X35") (pin "1") (pinfunction "1_1") (pintype "passive"))
    )
    (net (code "95") (name "Net-(DD1-~{DOK})") (class "Default")
      (node (ref "DD1") (pin "8") (pinfunction "~{DOK}_8") (pintype "passive"))
      (node (ref "HL5") (pin "K") (pinfunction "K_K") (pintype "passive"))
      (node (ref "X34") (pin "1") (pinfunction "1_1") (pintype "passive"))
    )
    (net (code "96") (name "Net-(DD1-~{FLT})") (class "Default")
      (node (ref "DD1") (pin "18") (pinfunction "~{FLT}_18") (pintype "passive"))
      (node (ref "HL7") (pin "K") (pinfunction "K_K") (pintype "passive"))
      (node (ref "X32") (pin "1") (pinfunction "1_1") (pintype "passive"))
    )
    (net (code "97") (name "Net-(DD1-~{UOK})") (class "Default")
      (node (ref "DD1") (pin "19") (pinfunction "~{UOK}_19") (pintype "passive"))
      (node (ref "HL6") (pin "K") (pinfunction "K_K") (pintype "passive"))
      (node (ref "X33") (pin "1") (pinfunction "1_1") (pintype "passive"))
    )
    (net (code "98") (name "Net-(DD2-AIN)") (class "Default")
      (node (ref "C5") (pin "2") (pinfunction "2_2") (pintype "passive"))
      (node (ref "DD2") (pin "2") (pinfunction "AIN_2") (pintype "passive"))
      (node (ref "R6") (pin "1") (pinfunction "1_1") (pintype "passive"))
      (node (ref "X5") (pin "1") (pinfunction "1_1") (pintype "passive"))
    )
    (net (code "99") (name "Net-(DD2-ALRT)") (class "Default")
      (node (ref "DD2") (pin "8") (pinfunction "ALRT_8") (pintype "passive"))
      (node (ref "X15") (pin "1") (pinfunction "1_1") (pintype "passive"))
    )
    (net (code "100") (name "Net-(DD2-CSN)") (class "Default")
      (node (ref "DD2") (pin "5") (pinfunction "CSN_5") (pintype "passive"))
      (node (ref "R13") (pin "2") (pinfunction "2_2") (pintype "passive"))
      (node (ref "X18") (pin "1") (pinfunction "1_1") (pintype "passive"))
    )
    (net (code "101") (name "Net-(DD2-REG)") (class "Default")
      (node (ref "C8") (pin "2") (pinfunction "2_2") (pintype "passive"))
      (node (ref "DD2") (pin "7") (pinfunction "REG_7") (pintype "passive"))
    )
    (net (code "102") (name "Net-(DD2-SCL)") (class "Default")
      (node (ref "DD2") (pin "3") (pinfunction "SCL_3") (pintype "passive"))
      (node (ref "R21") (pin "2") (pinfunction "2_2") (pintype "passive"))
      (node (ref "X17") (pin "1") (pinfunction "1_1") (pintype "passive"))
    )
    (net (code "103") (name "Net-(DD2-SDA)") (class "Default")
      (node (ref "DD2") (pin "4") (pinfunction "SDA_4") (pintype "passive"))
      (node (ref "R18") (pin "2") (pinfunction "2_2") (pintype "passive"))
      (node (ref "X16") (pin "1") (pinfunction "1_1") (pintype "passive"))
    )
    (net (code "104") (name "Net-(DD2-THRM)") (class "Default")
      (node (ref "DD2") (pin "9") (pinfunction "THRM_9") (pintype "passive"))
      (node (ref "R6") (pin "2") (pinfunction "2_2") (pintype "passive"))
    )
    (net (code "105") (name "Net-(DD2-VBATT)") (class "Default")
      (node (ref "C3") (pin "2") (pinfunction "2_2") (pintype "passive"))
      (node (ref "DD2") (pin "1") (pinfunction "Vtt_1") (pintype "passive"))
      (node (ref "DD2") (pin "10") (pinfunction "VBATT_10") (pintype "passive"))
      (node (ref "X13") (pin "1") (pinfunction "1_1") (pintype "passive"))
      (node (ref "X6") (pin "1") (pinfunction "1_1") (pintype "passive"))
    )
    (net (code "106") (name "Net-(DD3-LDO_IN)") (class "Default")
      (node (ref "C19") (pin "2") (pinfunction "2_2") (pintype "passive"))
      (node (ref "C2") (pin "2") (pinfunction "2_2") (pintype "passive"))
      (node (ref "C23") (pin "2") (pinfunction "2_2") (pintype "passive"))
      (node (ref "DD3") (pin "14") (pinfunction "VDDM_14") (pintype "passive"))
      (node (ref "DD3") (pin "2") (pinfunction "LDO_IN_2") (pintype "passive"))
      (node (ref "DD3") (pin "28") (pinfunction "VDDO_28") (pintype "passive"))
      (node (ref "R2") (pin "1") (pinfunction "1_1") (pintype "passive"))
    )
    (net (code "107") (name "Net-(DD3-LDO_OUT)") (class "Default")
      (node (ref "C4") (pin "2") (pinfunction "2_2") (pintype "passive"))
      (node (ref "DD3") (pin "3") (pinfunction "LDO_OUT_3") (pintype "passive"))
      (node (ref "ZL1") (pin "1") (pinfunction "1_1") (pintype "passive"))
      (node (ref "ZL2") (pin "1") (pinfunction "1_1") (pintype "passive"))
    )
    (net (code "108") (name "Net-(DD3-P8{slash}P33)") (class "Default")
      (node (ref "DD3") (pin "24") (pinfunction "P8/P33_24") (pintype "passive"))
      (node (ref "DD5") (pin "1") (pinfunction "CS#_1") (pintype "passive"))
    )
    (net (code "109") (name "Net-(DD3-P11{slash}P27{slash}XIN32)") (class "Default")
      (node (ref "C34") (pin "2") (pinfunction "2_2") (pintype "passive"))
      (node (ref "DD3") (pin "1") (pinfunction "P11/P27/XIN32_1") (pintype "passive"))
      (node (ref "G2") (pin "1") (pinfunction "1_1") (pintype "passive"))
      (node (ref "R34") (pin "1") (pinfunction "1_1") (pintype "passive"))
    )
    (net (code "110") (name "Net-(DD3-P12{slash}P26{slash}XO32)") (class "Default")
      (node (ref "C33") (pin "2") (pinfunction "2_2") (pintype "passive"))
      (node (ref "DD3") (pin "32") (pinfunction "P12/P26/XO32_32") (pintype "passive"))
      (node (ref "G2") (pin "2") (pinfunction "2_2") (pintype "passive"))
      (node (ref "R34") (pin "2") (pinfunction "2_2") (pintype "passive"))
    )
    (net (code "111") (name "Net-(DD3-P32)") (class "Default")
      (node (ref "DD3") (pin "25") (pinfunction "P32_25") (pintype "passive"))
      (node (ref "DD5") (pin "2") (pinfunction "SO/SIO1_2") (pintype "passive"))
    )
    (net (code "112") (name "Net-(DD3-RF)") (class "Default")
      (node (ref "C37") (pin "2") (pinfunction "2_2") (pintype "passive"))
      (node (ref "DD3") (pin "6") (pinfunction "RF_6") (pintype "passive"))
      (node (ref "L3") (pin "1") (pinfunction "1_1") (pintype "passive"))
    )
    (net (code "113") (name "Net-(DD3-SCL)") (class "Default")
      (node (ref "DD3") (pin "16") (pinfunction "SCL_16") (pintype "passive"))
      (node (ref "DD5") (pin "6") (pinfunction "SCLK_6") (pintype "passive"))
    )
    (net (code "114") (name "Net-(DD3-TALO)") (class "Default")
      (node (ref "C22") (pin "2") (pinfunction "2_2") (pintype "passive"))
      (node (ref "DD3") (pin "10") (pinfunction "TALO_10") (pintype "passive"))
      (node (ref "G1") (pin "3") (pinfunction "3_3") (pintype "passive"))
    )
    (net (code "115") (name "Net-(DD3-VDDC)") (class "Default")
      (node (ref "C24") (pin "2") (pinfunction "2_2") (pintype "passive"))
      (node (ref "DD3") (pin "11") (pinfunction "VDDC_11") (pintype "passive"))
      (node (ref "ZL1") (pin "2") (pinfunction "2_2") (pintype "passive"))
    )
    (net (code "116") (name "Net-(DD3-VDDFE)") (class "Default")
      (node (ref "C10") (pin "2") (pinfunction "2_2") (pintype "passive"))
      (node (ref "C12") (pin "2") (pinfunction "2_2") (pintype "passive"))
      (node (ref "C13") (pin "2") (pinfunction "2_2") (pintype "passive"))
      (node (ref "C14") (pin "2") (pinfunction "2_2") (pintype "passive"))
      (node (ref "DD3") (pin "4") (pinfunction "VDDIF_4") (pintype "passive"))
      (node (ref "DD3") (pin "5") (pinfunction "VDDFE_5") (pintype "passive"))
      (node (ref "DD3") (pin "7") (pinfunction "VDDVCO_7") (pintype "passive"))
      (node (ref "DD3") (pin "8") (pinfunction "VDDPLL_8") (pintype "passive"))
      (node (ref "ZL2") (pin "2") (pinfunction "2_2") (pintype "passive"))
    )
    (net (code "117") (name "Net-(DD3-XTALI)") (class "Default")
      (node (ref "C21") (pin "2") (pinfunction "2_2") (pintype "passive"))
      (node (ref "DD3") (pin "9") (pinfunction "XTALI_9") (pintype "passive"))
      (node (ref "G1") (pin "1") (pinfunction "1_1") (pintype "passive"))
    )
    (net (code "118") (name "Net-(DD4-CS)") (class "Default")
      (node (ref "DD4") (pin "12") (pinfunction "CS_12") (pintype "input"))
      (node (ref "X23") (pin "1") (pinfunction "1_1") (pintype "passive"))
    )
    (net (code "119") (name "Net-(DD4-INT1)") (class "Default")
      (node (ref "DD4") (pin "4") (pinfunction "INT1_4") (pintype "output"))
      (node (ref "X24") (pin "1") (pinfunction "1_1") (pintype "passive"))
    )
    (net (code "120") (name "Net-(DD4-INT2)") (class "Default")
      (node (ref "DD4") (pin "9") (pinfunction "INT2_9") (pintype "output"))
      (node (ref "X25") (pin "1") (pinfunction "1_1") (pintype "passive"))
    )
    (net (code "121") (name "Net-(DD4-OCS_Aux)") (class "Default")
      (node (ref "DD4") (pin "10") (pinfunction "OCS_Aux_10") (pintype "passive"))
      (node (ref "X27") (pin "1") (pinfunction "1_1") (pintype "passive"))
    )
    (net (code "122") (name "Net-(DD4-SCL)") (class "Default")
      (node (ref "DD4") (pin "13") (pinfunction "SCL_13") (pintype "input"))
      (node (ref "X26") (pin "1") (pinfunction "1_1") (pintype "passive"))
    )
    (net (code "123") (name "Net-(DD4-SDA)") (class "Default")
      (node (ref "DD4") (pin "14") (pinfunction "SDA_14") (pintype "bidirectional"))
      (node (ref "X28") (pin "1") (pinfunction "1_1") (pintype "passive"))
    )
    (net (code "124") (name "Net-(DD4-SDO_Aux)") (class "Default")
      (node (ref "DD4") (pin "11") (pinfunction "SDO_Aux_11") (pintype "passive"))
      (node (ref "X21") (pin "1") (pinfunction "1_1") (pintype "passive"))
    )
    (net (code "125") (name "Net-(DD4-SDO{slash}SA0)") (class "Default")
      (node (ref "DD4") (pin "1") (pinfunction "SDO/SA0_1") (pintype "bidirectional"))
      (node (ref "X22") (pin "1") (pinfunction "1_1") (pintype "passive"))
    )
    (net (code "126") (name "Net-(DD4-VDD)") (class "Default")
      (node (ref "C32") (pin "1") (pinfunction "1_1") (pintype "passive"))
      (node (ref "DD4") (pin "8") (pinfunction "VDD_8") (pintype "power_in"))
      (node (ref "ZL3") (pin "2") (pinfunction "2_2") (pintype "passive"))
    )
    (net (code "127") (name "Net-(DD5-VCC)") (class "Default")
      (node (ref "C39") (pin "2") (pinfunction "2_2") (pintype "passive"))
      (node (ref "DD5") (pin "8") (pinfunction "VCC_8") (pintype "passive"))
      (node (ref "R36") (pin "2") (pinfunction "2_2") (pintype "passive"))
    )
    (net (code "128") (name "Net-(DD6-3V3OUT)") (class "Default")
      (node (ref "C41") (pin "2") (pinfunction "2_2") (pintype "passive"))
      (node (ref "C43") (pin "2") (pinfunction "2_2") (pintype "passive"))
      (node (ref "DD6") (pin "1") (pinfunction "VCCIO_1") (pintype "power_in"))
      (node (ref "DD6") (pin "8") (pinfunction "3V3OUT_8") (pintype "output"))
      (node (ref "DD6") (pin "9") (pinfunction "~{RESET!}_9") (pintype "input"))
    )
    (net (code "129") (name "Net-(DD6-~{CTS!})") (class "Default")
      (node (ref "DD6") (pin "4") (pinfunction "~{CTS!}_4") (pintype "input"))
      (node (ref "X43") (pin "1") (pinfunction "1_1") (pintype "passive"))
    )
    (net (code "130") (name "Net-(DD6-~{RTS!})") (class "Default")
      (node (ref "DD6") (pin "16") (pinfunction "~{RTS!}_16") (pintype "output"))
      (node (ref "X42") (pin "1") (pinfunction "1_1") (pintype "passive"))
    )
    (net (code "131") (name "Net-(DD7-PA01{slash}XOUT32)") (class "Default")
      (node (ref "DD7") (pin "3") (pinfunction "PA01/XOUT32_3") (pintype "bidirectional"))
      (node (ref "XP18") (pin "1") (pinfunction "1_1") (pintype "passive"))
    )
    (net (code "132") (name "Net-(DD7-PA02{slash}AIN[0]{slash}Vout)") (class "Default")
      (node (ref "DD7") (pin "4") (pinfunction "PA02/AIN[0]/Vout_4") (pintype "bidirectional"))
      (node (ref "XP19") (pin "1") (pinfunction "1_1") (pintype "passive"))
    )
    (net (code "133") (name "Net-(DD7-PA03{slash}AIN[1]{slash}VREFA)") (class "Default")
      (node (ref "DD7") (pin "5") (pinfunction "PA03/AIN[1]/VREFA_5") (pintype "bidirectional"))
      (node (ref "XP20") (pin "1") (pinfunction "1_1") (pintype "passive"))
    )
    (net (code "134") (name "Net-(DD7-PA15{slash}XOUT)") (class "Default")
      (node (ref "DD7") (pin "12") (pinfunction "PA15/XOUT_12") (pintype "bidirectional"))
      (node (ref "XP36") (pin "1") (pinfunction "1_1") (pintype "passive"))
    )
    (net (code "135") (name "Net-(DD7-PA16{slash}hs{slash}SER[0.0][1.0]SDA)") (class "Default")
      (node (ref "DD7") (pin "13") (pinfunction "PA16/hs/SER[0.0][1.0]SDA_13") (pintype "bidirectional"))
      (node (ref "XP32") (pin "1") (pinfunction "1_1") (pintype "passive"))
    )
    (net (code "136") (name "Net-(DD7-PA17{slash}hs{slash}SER[0.1][1.1]SCL)") (class "Default")
      (node (ref "DD7") (pin "14") (pinfunction "PA17/hs/SER[0.1][1.1]SCL_14") (pintype "bidirectional"))
      (node (ref "XP31") (pin "1") (pinfunction "1_1") (pintype "passive"))
    )
    (net (code "137") (name "Net-(DD7-PA30{slash}SWCLK)") (class "Default")
      (node (ref "DD7") (pin "24") (pinfunction "PA30/SWCLK_24") (pintype "bidirectional"))
      (node (ref "XP11") (pin "7") (pinfunction "7_7") (pintype "passive"))
      (node (ref "XP12") (pin "1") (pinfunction "1_1") (pintype "passive"))
    )
    (net (code "138") (name "Net-(DD7-PA31{slash}SWDIO{slash}hs)") (class "Default")
      (node (ref "DD7") (pin "1") (pinfunction "PA31/SWDIO/hs_1") (pintype "bidirectional"))
      (node (ref "XP11") (pin "9") (pinfunction "9_9") (pintype "passive"))
      (node (ref "XP16") (pin "1") (pinfunction "1_1") (pintype "passive"))
    )
    (net (code "139") (name "Net-(DD7-VDDANA)") (class "Default")
      (node (ref "C51") (pin "2") (pinfunction "2_2") (pintype "passive"))
      (node (ref "DD7") (pin "8") (pinfunction "VDDANA_8") (pintype "input"))
      (node (ref "ZL4") (pin "2") (pinfunction "2_2") (pintype "passive"))
    )
    (net (code "140") (name "Net-(DD7-VDDCORE)") (class "Default")
      (node (ref "C52") (pin "2") (pinfunction "2_2") (pintype "passive"))
      (node (ref "C54") (pin "1") (pinfunction "1_1") (pintype "passive"))
      (node (ref "DD7") (pin "20") (pinfunction "VDDCORE_20") (pintype "output"))
    )
    (net (code "141") (name "Net-(DD7-VDDOUT)") (class "Default")
      (node (ref "DD7") (pin "22") (pinfunction "VDDOUT_22") (pintype "output"))
      (node (ref "X44") (pin "1") (pinfunction "1_1") (pintype "passive"))
    )
    (net (code "142") (name "Net-(DD8-CS)") (class "Default")
      (node (ref "DD8") (pin "12") (pinfunction "CS_12") (pintype "input"))
      (node (ref "R43") (pin "2") (pinfunction "2_2") (pintype "passive"))
    )
    (net (code "143") (name "Net-(DD8-INT1)") (class "Default")
      (node (ref "DD8") (pin "4") (pinfunction "INT1_4") (pintype "output"))
      (node (ref "X45") (pin "1") (pinfunction "1_1") (pintype "passive"))
    )
    (net (code "144") (name "Net-(DD8-INT2)") (class "Default")
      (node (ref "DD8") (pin "9") (pinfunction "INT2_9") (pintype "output"))
      (node (ref "X46") (pin "1") (pinfunction "1_1") (pintype "passive"))
    )
    (net (code "145") (name "Net-(DD8-OCS_Aux)") (class "Default")
      (node (ref "DD8") (pin "10") (pinfunction "OCS_Aux_10") (pintype "passive"))
      (node (ref "X47") (pin "1") (pinfunction "1_1") (pintype "passive"))
    )
    (net (code "146") (name "Net-(DD8-SCL)") (class "Default")
      (node (ref "DD8") (pin "13") (pinfunction "SCL_13") (pintype "input"))
      (node (ref "R44") (pin "2") (pinfunction "2_2") (pintype "passive"))
    )
    (net (code "147") (name "Net-(DD8-SCx)") (class "Default")
      (node (ref "C55") (pin "1") (pinfunction "1_1") (pintype "passive"))
      (node (ref "DD8") (pin "2") (pinfunction "SDx_2") (pintype "passive"))
      (node (ref "DD8") (pin "3") (pinfunction "SCx_3") (pintype "passive"))
      (node (ref "DD8") (pin "5") (pinfunction "VDDIO_5") (pintype "power_in"))
      (node (ref "R46") (pin "2") (pinfunction "2_2") (pintype "passive"))
      (node (ref "ZL5") (pin "1") (pinfunction "1_1") (pintype "passive"))
    )
    (net (code "148") (name "Net-(DD8-SDA)") (class "Default")
      (node (ref "DD8") (pin "14") (pinfunction "SDA_14") (pintype "bidirectional"))
      (node (ref "R45") (pin "2") (pinfunction "2_2") (pintype "passive"))
    )
    (net (code "149") (name "Net-(DD8-SDO_Aux)") (class "Default")
      (node (ref "DD8") (pin "11") (pinfunction "SDO_Aux_11") (pintype "passive"))
      (node (ref "X48") (pin "1") (pinfunction "1_1") (pintype "passive"))
    )
    (net (code "150") (name "Net-(DD8-SDO{slash}SA0)") (class "Default")
      (node (ref "DD8") (pin "1") (pinfunction "SDO/SA0_1") (pintype "bidirectional"))
      (node (ref "R42") (pin "2") (pinfunction "2_2") (pintype "passive"))
    )
    (net (code "151") (name "Net-(DD8-VDD)") (class "Default")
      (node (ref "C57") (pin "1") (pinfunction "1_1") (pintype "passive"))
      (node (ref "DD8") (pin "8") (pinfunction "VDD_8") (pintype "power_in"))
      (node (ref "ZL5") (pin "2") (pinfunction "2_2") (pintype "passive"))
    )
    (net (code "152") (name "Net-(HL1-PadA)") (class "Default")
      (node (ref "HL1") (pin "A") (pinfunction "A_A") (pintype "passive"))
      (node (ref "R5") (pin "1") (pinfunction "1_1") (pintype "passive"))
    )
    (net (code "153") (name "Net-(HL2-PadK)") (class "Default")
      (node (ref "HL2") (pin "K") (pinfunction "K_K") (pintype "passive"))
      (node (ref "R24") (pin "2") (pinfunction "2_2") (pintype "passive"))
    )
    (net (code "154") (name "Net-(HL3-PadK)") (class "Default")
      (node (ref "HL3") (pin "K") (pinfunction "K_K") (pintype "passive"))
      (node (ref "R25") (pin "2") (pinfunction "2_2") (pintype "passive"))
    )
    (net (code "155") (name "Net-(HL4-PadA)") (class "Default")
      (node (ref "HL4") (pin "A") (pinfunction "A_A") (pintype "passive"))
      (node (ref "R26") (pin "1") (pinfunction "1_1") (pintype "passive"))
    )
    (net (code "156") (name "Net-(HL5-PadA)") (class "Default")
      (node (ref "HL5") (pin "A") (pinfunction "A_A") (pintype "passive"))
      (node (ref "R27") (pin "1") (pinfunction "1_1") (pintype "passive"))
    )
    (net (code "157") (name "Net-(HL6-PadA)") (class "Default")
      (node (ref "HL6") (pin "A") (pinfunction "A_A") (pintype "passive"))
      (node (ref "R30") (pin "1") (pinfunction "1_1") (pintype "passive"))
    )
    (net (code "158") (name "Net-(HL7-PadA)") (class "Default")
      (node (ref "HL7") (pin "A") (pinfunction "A_A") (pintype "passive"))
      (node (ref "R31") (pin "1") (pinfunction "1_1") (pintype "passive"))
    )
    (net (code "159") (name "Net-(HL8-PadK)") (class "Default")
      (node (ref "HL8") (pin "K") (pinfunction "K_K") (pintype "passive"))
      (node (ref "R37") (pin "1") (pinfunction "1_1") (pintype "passive"))
    )
    (net (code "160") (name "Net-(HL9-PadK)") (class "Default")
      (node (ref "HL9") (pin "K") (pinfunction "K_K") (pintype "passive"))
      (node (ref "R38") (pin "1") (pinfunction "1_1") (pintype "passive"))
    )
    (net (code "161") (name "Net-(HL10-PadA)") (class "Default")
      (node (ref "HL10") (pin "A") (pinfunction "A_A") (pintype "passive"))
      (node (ref "R39") (pin "1") (pinfunction "1_1") (pintype "passive"))
    )
    (net (code "162") (name "Net-(HL11-PadA)") (class "Default")
      (node (ref "HL11") (pin "A") (pinfunction "A_A") (pintype "passive"))
      (node (ref "R47") (pin "1") (pinfunction "1_1") (pintype "passive"))
    )
    (net (code "163") (name "Net-(HL12-PadA)") (class "Default")
      (node (ref "HL12") (pin "A") (pinfunction "A_A") (pintype "passive"))
      (node (ref "R14") (pin "1") (pinfunction "1_1") (pintype "passive"))
    )
    (net (code "164") (name "Net-(HL13-PadA)") (class "Default")
      (node (ref "HL13") (pin "A") (pinfunction "A_A") (pintype "passive"))
      (node (ref "R15") (pin "1") (pinfunction "1_1") (pintype "passive"))
    )
    (net (code "165") (name "Net-(HL14-PadA)") (class "Default")
      (node (ref "HL14") (pin "A") (pinfunction "A_A") (pintype "passive"))
      (node (ref "R50") (pin "2") (pinfunction "2_2") (pintype "passive"))
    )
    (net (code "166") (name "Net-(HL15-PadA)") (class "Default")
      (node (ref "HL15") (pin "A") (pinfunction "A_A") (pintype "passive"))
      (node (ref "R68") (pin "1") (pinfunction "1_1") (pintype "passive"))
    )
    (net (code "167") (name "Net-(HL16-PadA)") (class "Default")
      (node (ref "HL16") (pin "A") (pinfunction "A_A") (pintype "passive"))
      (node (ref "R59") (pin "2") (pinfunction "2_2") (pintype "passive"))
    )
    (net (code "168") (name "Net-(HL17-PadA)") (class "Default")
      (node (ref "HL17") (pin "A") (pinfunction "A_A") (pintype "passive"))
      (node (ref "R64") (pin "2") (pinfunction "2_2") (pintype "passive"))
    )
    (net (code "169") (name "Net-(K1-Pad1)") (class "Default")
      (node (ref "K1") (pin "1") (pinfunction "1_1") (pintype "passive"))
      (node (ref "XT1") (pin "2") (pinfunction "2_2") (pintype "passive"))
    )
    (net (code "170") (name "Net-(K1-Pad3)") (class "Default")
      (node (ref "K1") (pin "3") (pinfunction "3_3") (pintype "passive"))
      (node (ref "XT1") (pin "3") (pinfunction "3_3") (pintype "passive"))
    )
    (net (code "171") (name "Net-(K1-Pad4)") (class "Default")
      (node (ref "K1") (pin "4") (pinfunction "4_4") (pintype "passive"))
      (node (ref "XT1") (pin "1") (pinfunction "1_1") (pintype "passive"))
    )
    (net (code "172") (name "Net-(R1-Pad2)") (class "Default")
      (node (ref "R1") (pin "2") (pinfunction "2_2") (pintype "passive"))
      (node (ref "XS3") (pin "3") (pinfunction "3_3") (pintype "passive"))
    )
    (net (code "173") (name "Net-(R18-Pad1)") (class "Default")
      (node (ref "R18") (pin "1") (pinfunction "1_1") (pintype "passive"))
      (node (ref "R21") (pin "1") (pinfunction "1_1") (pintype "passive"))
      (node (ref "X14") (pin "1") (pinfunction "1_1") (pintype "passive"))
    )
    (net (code "174") (name "Net-(R22-Pad1)") (class "Default")
      (node (ref "R22") (pin "1") (pinfunction "1_1") (pintype "passive"))
      (node (ref "XP9") (pin "3") (pinfunction "3_3") (pintype "passive"))
    )
    (net (code "175") (name "Net-(R54-Pad1)") (class "Default")
      (node (ref "R54") (pin "1") (pinfunction "1_1") (pintype "passive"))
      (node (ref "XT2") (pin "2") (pinfunction "2_2") (pintype "passive"))
    )
    (net (code "176") (name "Net-(R55-Pad1)") (class "Default")
      (node (ref "R55") (pin "1") (pinfunction "1_1") (pintype "passive"))
      (node (ref "XT3") (pin "2") (pinfunction "2_2") (pintype "passive"))
    )
    (net (code "177") (name "Net-(R56-Pad2)") (class "Default")
      (node (ref "R56") (pin "2") (pinfunction "2_2") (pintype "passive"))
      (node (ref "X68") (pin "1") (pinfunction "1_1") (pintype "passive"))
    )
    (net (code "178") (name "Net-(R61-Pad2)") (class "Default")
      (node (ref "R61") (pin "2") (pinfunction "2_2") (pintype "passive"))
      (node (ref "R62") (pin "1") (pinfunction "1_1") (pintype "passive"))
    )
    (net (code "179") (name "Net-(R67-Pad1)") (class "Default")
      (node (ref "R67") (pin "1") (pinfunction "1_1") (pintype "passive"))
      (node (ref "XT") (pin "2") (pinfunction "2_2") (pintype "passive"))
    )
    (net (code "180") (name "Net-(R69-Pad1)") (class "Default")
      (node (ref "R69") (pin "1") (pinfunction "1_1") (pintype "passive"))
      (node (ref "XP10") (pin "1") (pinfunction "1_1") (pintype "passive"))
    )
    (net (code "181") (name "Net-(R70-Pad1)") (class "Default")
      (node (ref "R70") (pin "1") (pinfunction "1_1") (pintype "passive"))
      (node (ref "XP41") (pin "1") (pinfunction "1_1") (pintype "passive"))
    )
    (net (code "182") (name "Net-(RP1-BOT)") (class "Default")
      (node (ref "R8") (pin "1") (pinfunction "1_1") (pintype "passive"))
      (node (ref "R9") (pin "2") (pinfunction "2_2") (pintype "passive"))
      (node (ref "RP1") (pin "1") (pinfunction "TOP_1") (pintype "passive"))
      (node (ref "RP1") (pin "2") (pinfunction "BOT_2") (pintype "passive"))
    )
    (net (code "183") (name "Net-(RP2-BOT)") (class "Default")
      (node (ref "R11") (pin "1") (pinfunction "1_1") (pintype "passive"))
      (node (ref "R12") (pin "2") (pinfunction "2_2") (pintype "passive"))
      (node (ref "RP2") (pin "1") (pinfunction "TOP_1") (pintype "passive"))
      (node (ref "RP2") (pin "2") (pinfunction "BOT_2") (pintype "passive"))
    )
    (net (code "184") (name "Net-(RP3-BOT)") (class "Default")
      (node (ref "R29") (pin "2") (pinfunction "2_2") (pintype "passive"))
      (node (ref "RP3") (pin "2") (pinfunction "BOT_2") (pintype "passive"))
      (node (ref "RP3") (pin "3") (pinfunction "TAP_3") (pintype "passive"))
    )
    (net (code "185") (name "Net-(RP3-TOP)") (class "Default")
      (node (ref "R28") (pin "1") (pinfunction "1_1") (pintype "passive"))
      (node (ref "RP3") (pin "1") (pinfunction "TOP_1") (pintype "passive"))
    )
    (net (code "186") (name "Net-(RP4-BOT)") (class "Default")
      (node (ref "R32") (pin "2") (pinfunction "2_2") (pintype "passive"))
      (node (ref "RP4") (pin "2") (pinfunction "BOT_2") (pintype "passive"))
      (node (ref "RP4") (pin "3") (pinfunction "TAP_3") (pintype "passive"))
    )
    (net (code "187") (name "Net-(RP5-BOT)") (class "Default")
      (node (ref "R60") (pin "1") (pinfunction "1_1") (pintype "passive"))
      (node (ref "R62") (pin "2") (pinfunction "2_2") (pintype "passive"))
      (node (ref "RP5") (pin "1") (pinfunction "TOP_1") (pintype "passive"))
      (node (ref "RP5") (pin "2") (pinfunction "BOT_2") (pintype "passive"))
    )
    (net (code "188") (name "Net-(SB2-COMMON)") (class "Default")
      (node (ref "R16") (pin "1") (pinfunction "1_1") (pintype "passive"))
      (node (ref "SB2") (pin "1") (pinfunction "COMMON_1") (pintype "passive"))
    )
    (net (code "189") (name "Net-(TP1-Pad1)") (class "Default")
      (node (ref "TP1") (pin "1") (pinfunction "1_1") (pintype "passive"))
      (node (ref "XS1") (pin "4") (pinfunction "4_4") (pintype "passive"))
    )
    (net (code "190") (name "Net-(VD3-A)") (class "Default")
      (node (ref "K1") (pin "2") (pinfunction "2_2") (pintype "passive"))
      (node (ref "VD3") (pin "2") (pinfunction "A_2") (pintype "passive"))
      (node (ref "VT4") (pin "3") (pinfunction "C_3") (pintype "passive"))
    )
    (net (code "191") (name "Net-(VD4-A)") (class "Default")
      (node (ref "VD4") (pin "2") (pinfunction "A_2") (pintype "passive"))
      (node (ref "VT5") (pin "3") (pinfunction "D_3") (pintype "passive"))
      (node (ref "XT4") (pin "2") (pinfunction "2_2") (pintype "passive"))
    )
    (net (code "192") (name "Net-(VD5-C)") (class "Default")
      (node (ref "VD5") (pin "1") (pinfunction "C_1") (pintype "passive"))
      (node (ref "VT6") (pin "3") (pinfunction "D_3") (pintype "passive"))
      (node (ref "XT5") (pin "1") (pinfunction "1_1") (pintype "passive"))
    )
    (net (code "193") (name "Net-(VT3-B)") (class "Default")
      (node (ref "R56") (pin "1") (pinfunction "1_1") (pintype "passive"))
      (node (ref "R57") (pin "1") (pinfunction "1_1") (pintype "passive"))
      (node (ref "VT3") (pin "1") (pinfunction "B_1") (pintype "passive"))
    )
    (net (code "194") (name "Net-(VT4-B)") (class "Default")
      (node (ref "R52") (pin "2") (pinfunction "2_2") (pintype "passive"))
      (node (ref "R53") (pin "2") (pinfunction "2_2") (pintype "passive"))
      (node (ref "VT4") (pin "1") (pinfunction "B_1") (pintype "passive"))
    )
    (net (code "195") (name "Net-(VT5-G)") (class "Default")
      (node (ref "DA9") (pin "3") (pinfunction "3_3") (pintype "passive"))
      (node (ref "R65") (pin "2") (pinfunction "2_2") (pintype "passive"))
      (node (ref "VT5") (pin "1") (pinfunction "G_1") (pintype "passive"))
    )
    (net (code "196") (name "Net-(VT6-G)") (class "Default")
      (node (ref "DA11") (pin "4") (pinfunction "4_4") (pintype "passive"))
      (node (ref "R66") (pin "1") (pinfunction "1_1") (pintype "passive"))
      (node (ref "VT6") (pin "1") (pinfunction "G_1") (pintype "passive"))
    )
    (net (code "197") (name "Net-(X1-Pad1)") (class "Default")
      (node (ref "X1") (pin "1") (pinfunction "1_1") (pintype "passive"))
      (node (ref "XP4") (pin "1") (pinfunction "1_1") (pintype "passive"))
    )
    (net (code "198") (name "Net-(X9-Pad1)") (class "Default")
      (node (ref "X9") (pin "1") (pinfunction "1_1") (pintype "passive"))
      (node (ref "XP4") (pin "3") (pinfunction "3_3") (pintype "passive"))
      (node (ref "XS1") (pin "1") (pinfunction "1_1") (pintype "passive"))
    )
    (net (code "199") (name "V_bat") (class "Default")
      (node (ref "DA4") (pin "3") (pinfunction "VBAT_3") (pintype "passive"))
      (node (ref "VT2") (pin "2") (pinfunction "D_2") (pintype "passive"))
      (node (ref "XP23") (pin "1") (pinfunction "1_1") (pintype "passive"))
      (node (ref "XP35") (pin "1") (pinfunction "1_1") (pintype "passive"))
    )
    (net (code "200") (name "Vcc") (class "Default")
      (node (ref "C67") (pin "2") (pinfunction "2_2") (pintype "passive"))
      (node (ref "C68") (pin "2") (pinfunction "2_2") (pintype "passive"))
      (node (ref "DA10") (pin "5") (pinfunction "VCC_5") (pintype "passive"))
      (node (ref "DA12") (pin "4") (pinfunction "4_4") (pintype "passive"))
      (node (ref "DA9") (pin "4") (pinfunction "4_4") (pintype "passive"))
      (node (ref "K1") (pin "5") (pinfunction "5_5") (pintype "passive"))
      (node (ref "R58") (pin "1") (pinfunction "1_1") (pintype "passive"))
      (node (ref "R63") (pin "1") (pinfunction "1_1") (pintype "passive"))
      (node (ref "R66") (pin "2") (pinfunction "2_2") (pintype "passive"))
      (node (ref "VD3") (pin "1") (pinfunction "C_1") (pintype "passive"))
      (node (ref "VD4") (pin "1") (pinfunction "C_1") (pintype "passive"))
      (node (ref "VT6") (pin "2") (pinfunction "S_2") (pintype "passive"))
      (node (ref "X66") (pin "1") (pinfunction "1_1") (pintype "passive"))
      (node (ref "XT") (pin "3") (pinfunction "3_3") (pintype "passive"))
      (node (ref "XT2") (pin "3") (pinfunction "3_3") (pintype "passive"))
      (node (ref "XT3") (pin "3") (pinfunction "3_3") (pintype "passive"))
      (node (ref "XT4") (pin "1") (pinfunction "1_1") (pintype "passive"))
    )
    (net (code "201") (name "unconnected-(DA1-NC-Pad4)") (class "Default")
      (node (ref "DA1") (pin "4") (pinfunction "NC_4") (pintype "passive+no_connect"))
    )
    (net (code "202") (name "unconnected-(DA2-NC-Pad2)") (class "Default")
      (node (ref "DA2") (pin "2") (pinfunction "NC_2") (pintype "passive+no_connect"))
    )
    (net (code "203") (name "unconnected-(DA5-NC-Pad4)") (class "Default")
      (node (ref "DA5") (pin "4") (pinfunction "NC_4") (pintype "passive+no_connect"))
    )
    (net (code "204") (name "unconnected-(DD3-P2-Pad22)") (class "Default")
      (node (ref "DD3") (pin "22") (pinfunction "P2_22") (pintype "passive"))
    )
    (net (code "205") (name "unconnected-(DD3-P13{slash}P28-Pad29)") (class "Default")
      (node (ref "DD3") (pin "29") (pinfunction "P13/P28_29") (pintype "passive"))
    )
    (net (code "206") (name "unconnected-(DD3-P14{slash}P38-Pad30)") (class "Default")
      (node (ref "DD3") (pin "30") (pinfunction "P14/P38_30") (pintype "passive"))
    )
    (net (code "207") (name "unconnected-(DD3-P15-Pad31)") (class "Default")
      (node (ref "DD3") (pin "31") (pinfunction "P15_31") (pintype "passive"))
    )
    (net (code "208") (name "unconnected-(DD3-P24-Pad27)") (class "Default")
      (node (ref "DD3") (pin "27") (pinfunction "P24_27") (pintype "passive"))
    )
    (net (code "209") (name "unconnected-(DD3-P25-Pad26)") (class "Default")
      (node (ref "DD3") (pin "26") (pinfunction "P25_26") (pintype "passive"))
    )
    (net (code "210") (name "unconnected-(DD5-RESET#{slash}SIO3-Pad7)") (class "Default")
      (node (ref "DD5") (pin "7") (pinfunction "RESET#/SIO3_7") (pintype "passive+no_connect"))
    )
    (net (code "211") (name "unconnected-(DD5-WP#{slash}SIO2-Pad3)") (class "Default")
      (node (ref "DD5") (pin "3") (pinfunction "WP#/SIO2_3") (pintype "passive+no_connect"))
    )
    (net (code "212") (name "unconnected-(DD6-CBUS0-Pad12)") (class "Default")
      (node (ref "DD6") (pin "12") (pinfunction "CBUS0_12") (pintype "bidirectional+no_connect"))
    )
    (net (code "213") (name "unconnected-(DD6-CBUS1-Pad11)") (class "Default")
      (node (ref "DD6") (pin "11") (pinfunction "CBUS1_11") (pintype "bidirectional+no_connect"))
    )
    (net (code "214") (name "unconnected-(DD6-CBUS2-Pad5)") (class "Default")
      (node (ref "DD6") (pin "5") (pinfunction "CBUS2_5") (pintype "bidirectional+no_connect"))
    )
    (net (code "215") (name "unconnected-(DD6-CBUS3-Pad14)") (class "Default")
      (node (ref "DD6") (pin "14") (pinfunction "CBUS3_14") (pintype "bidirectional+no_connect"))
    )
    (net (code "216") (name "unconnected-(XP11-Pad3)") (class "Default")
      (node (ref "XP11") (pin "3") (pinfunction "3_3") (pintype "passive+no_connect"))
    )
    (net (code "217") (name "unconnected-(XP11-Pad4)") (class "Default")
      (node (ref "XP11") (pin "4") (pinfunction "4_4") (pintype "passive+no_connect"))
    )
    (net (code "218") (name "unconnected-(XP11-Pad5)") (class "Default")
      (node (ref "XP11") (pin "5") (pinfunction "5_5") (pintype "passive"))
    )
    (net (code "219") (name "unconnected-(XS3-Pad2)") (class "Default")
      (node (ref "XS3") (pin "2") (pinfunction "2_2") (pintype "passive"))
    )
    (net (code "220") (name "unconnected-(XS3-Pad4)") (class "Default")
      (node (ref "XS3") (pin "4") (pinfunction "4_4") (pintype "passive"))
    )
    (net (code "221") (name "unconnected-(XS5-Pad4)") (class "Default")
      (node (ref "XS5") (pin "4") (pinfunction "4_4") (pintype "passive"))
    )
  )
)
